# VNA.net
KiCad netlist of a schematic drawn in EAGLE
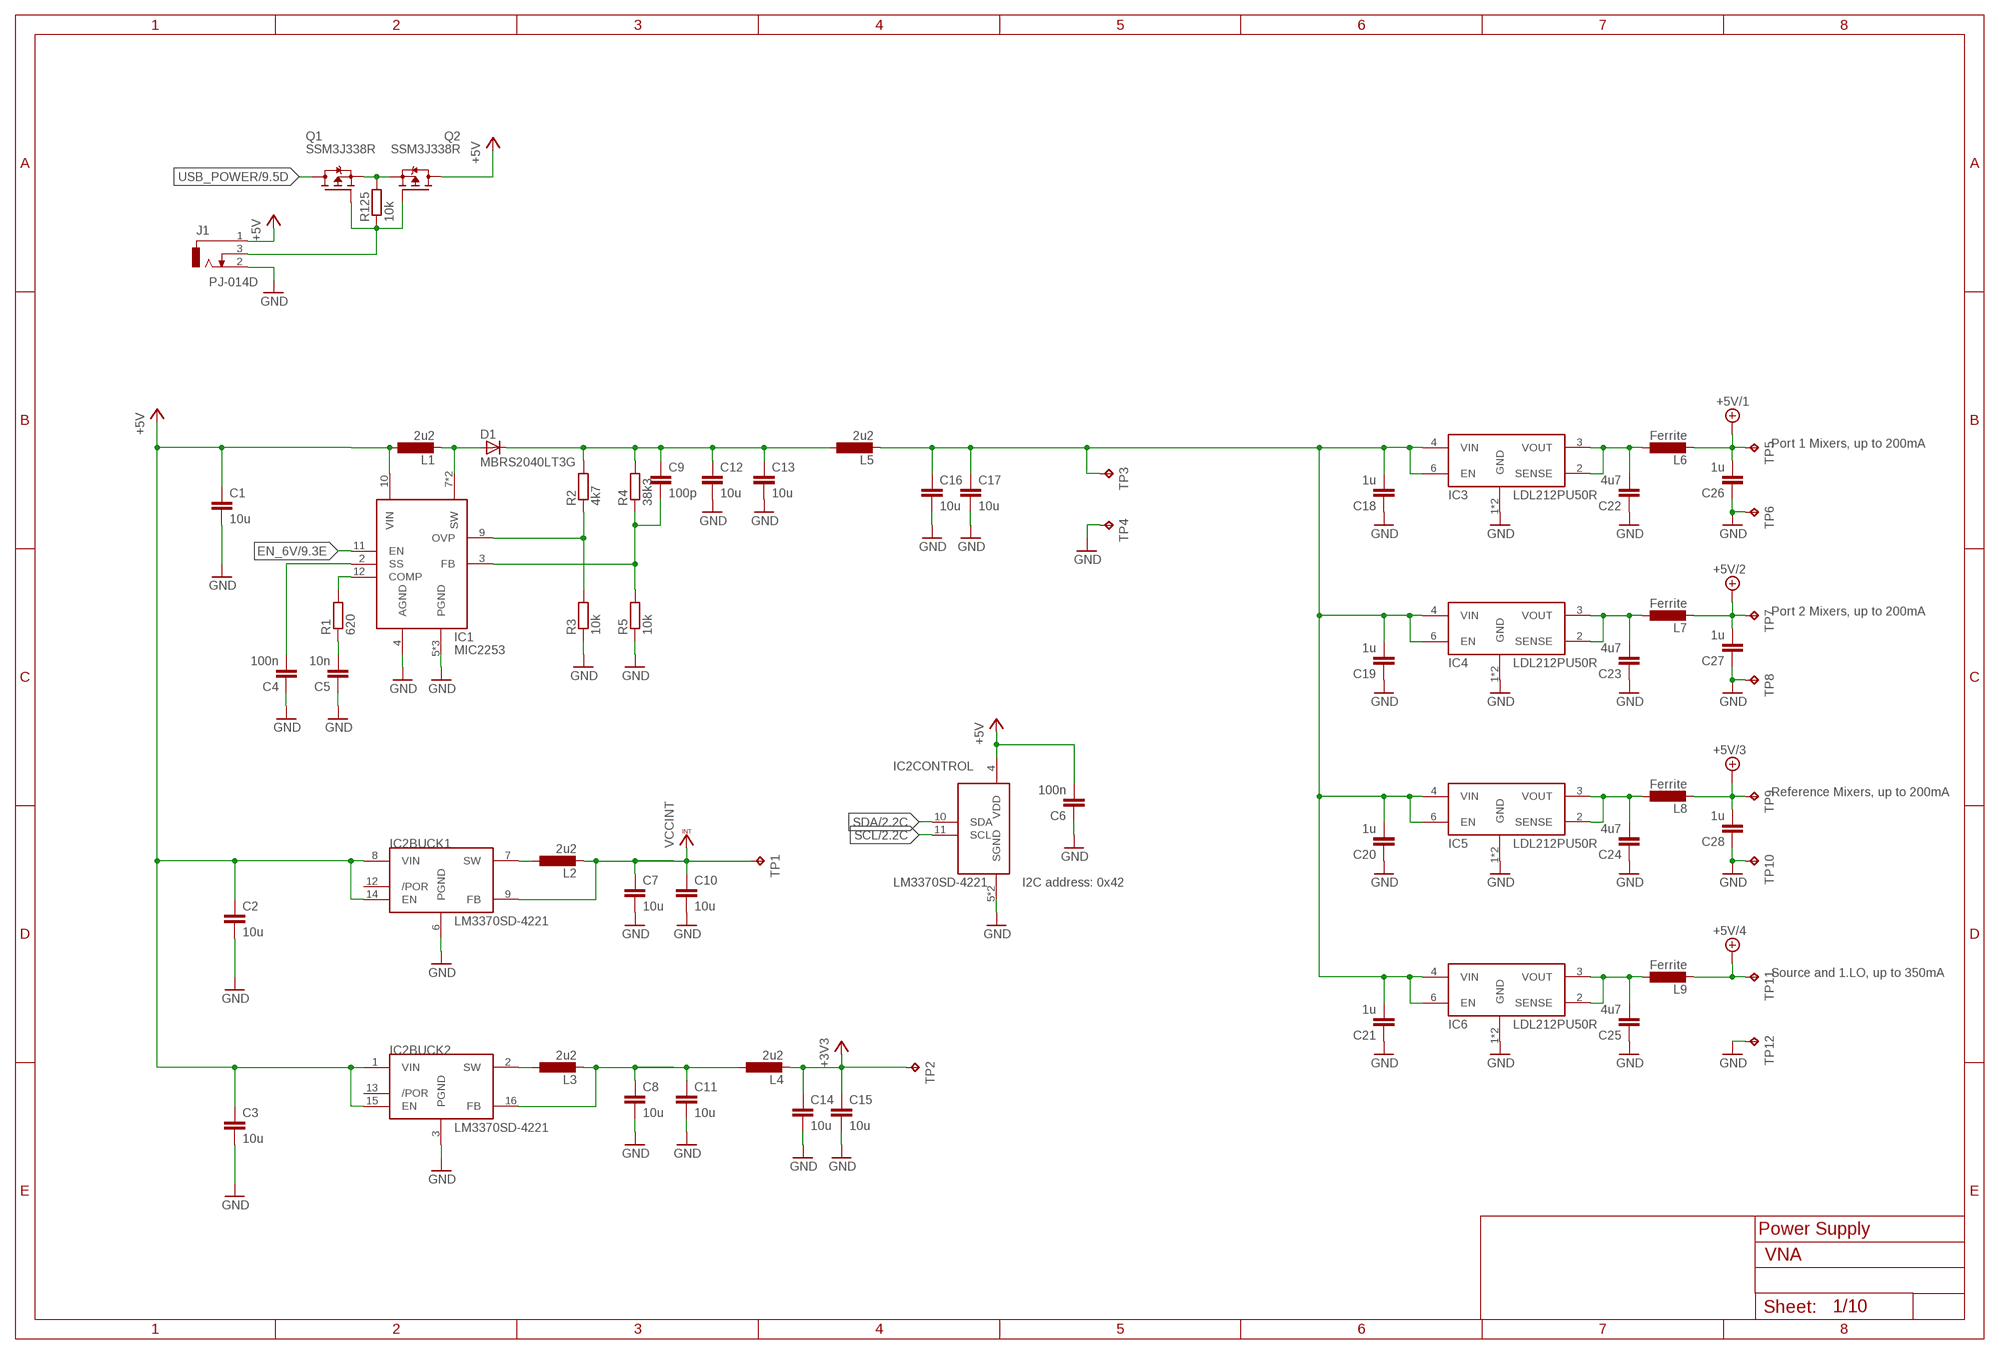
[diagram p0: schematic, sheet 1]
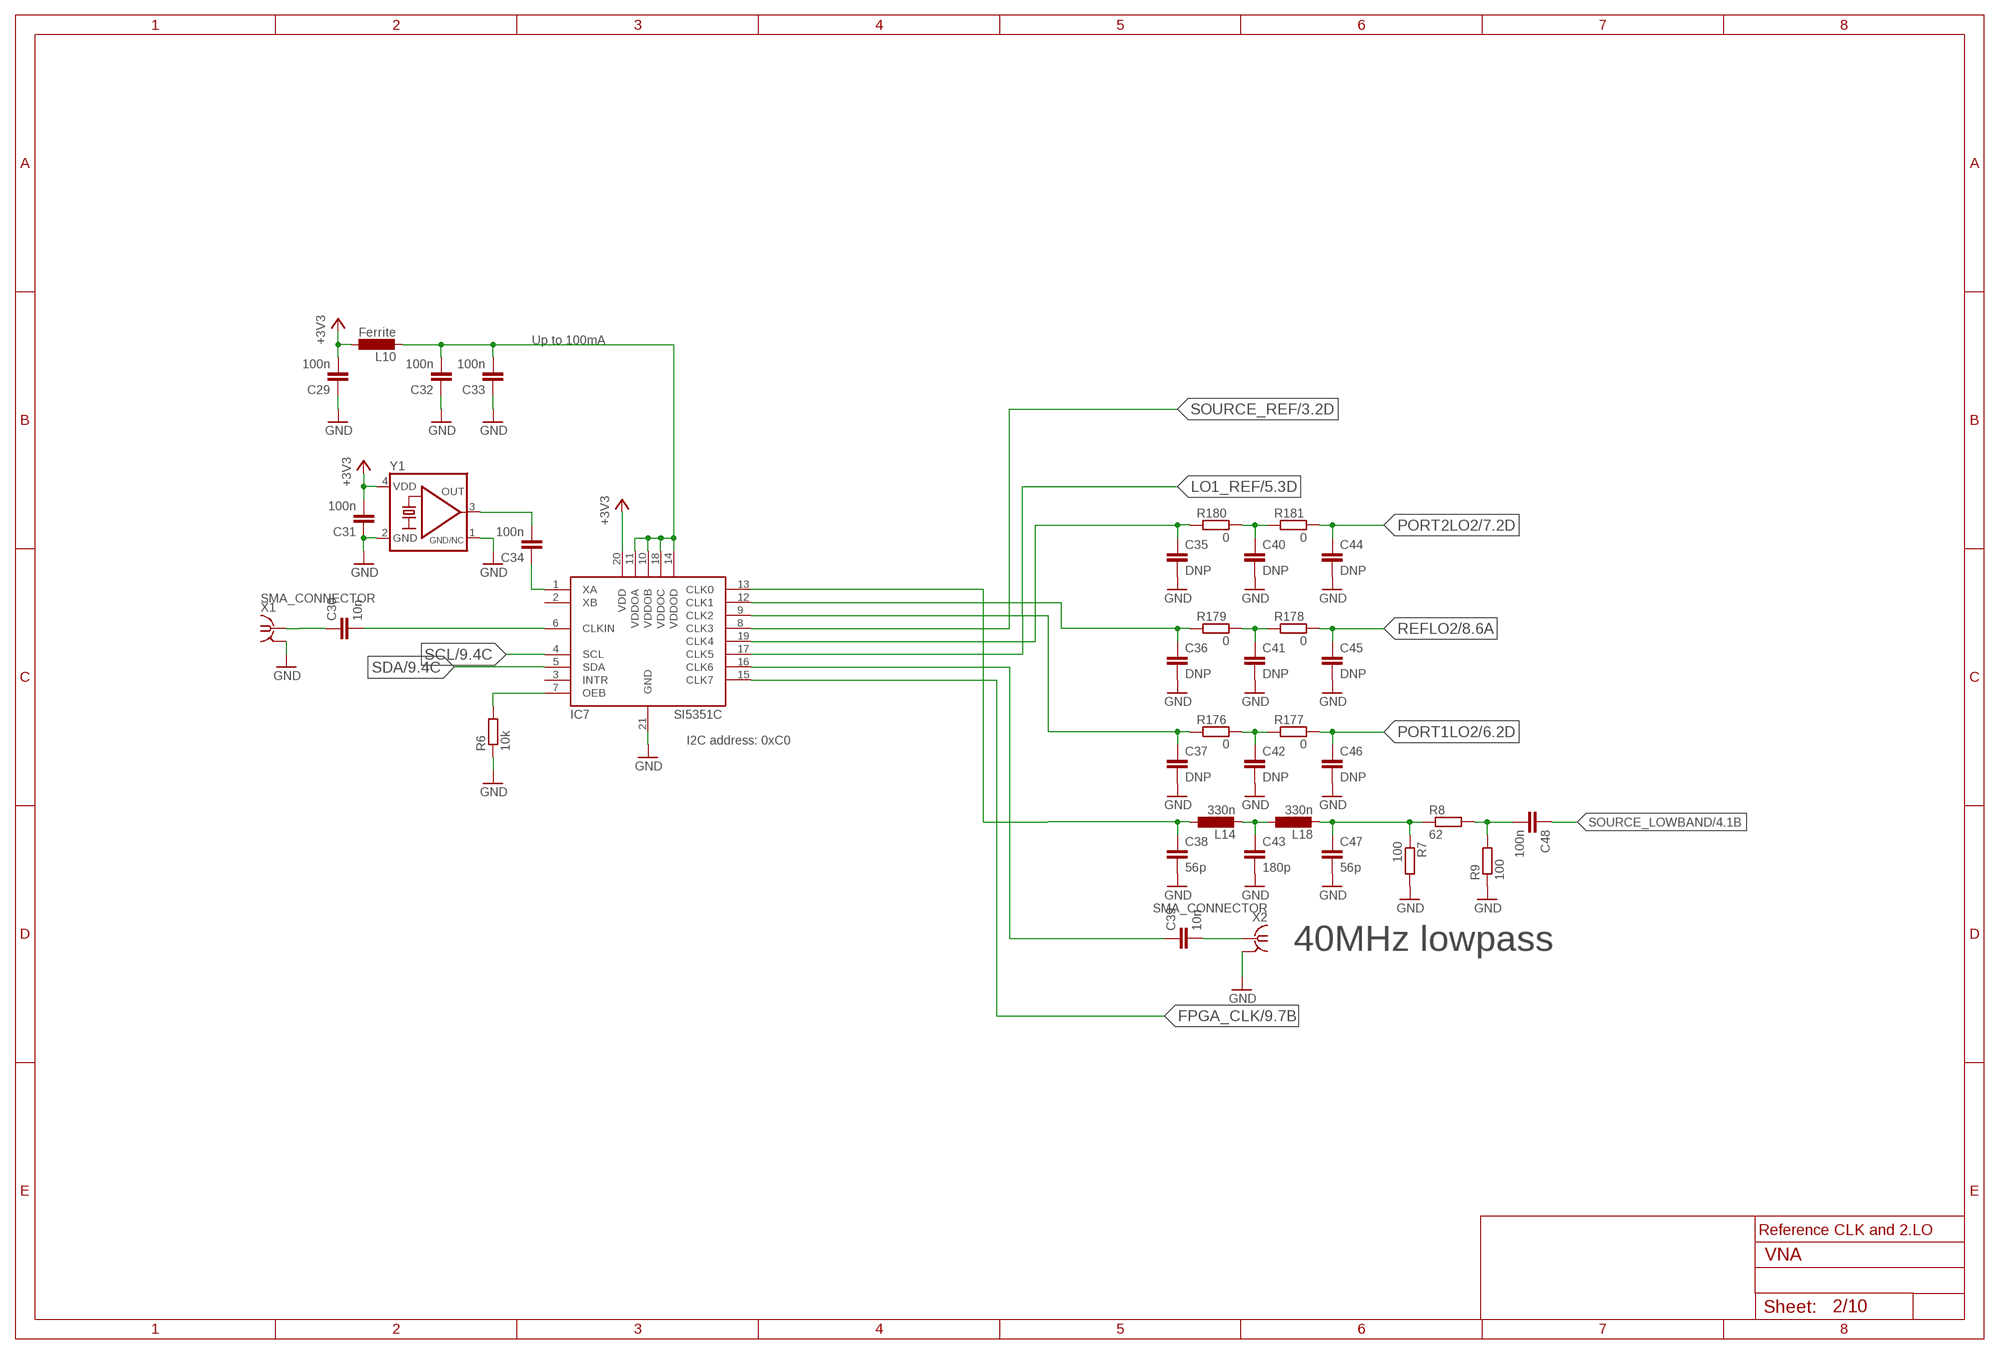
[diagram p1: schematic, sheet 2]
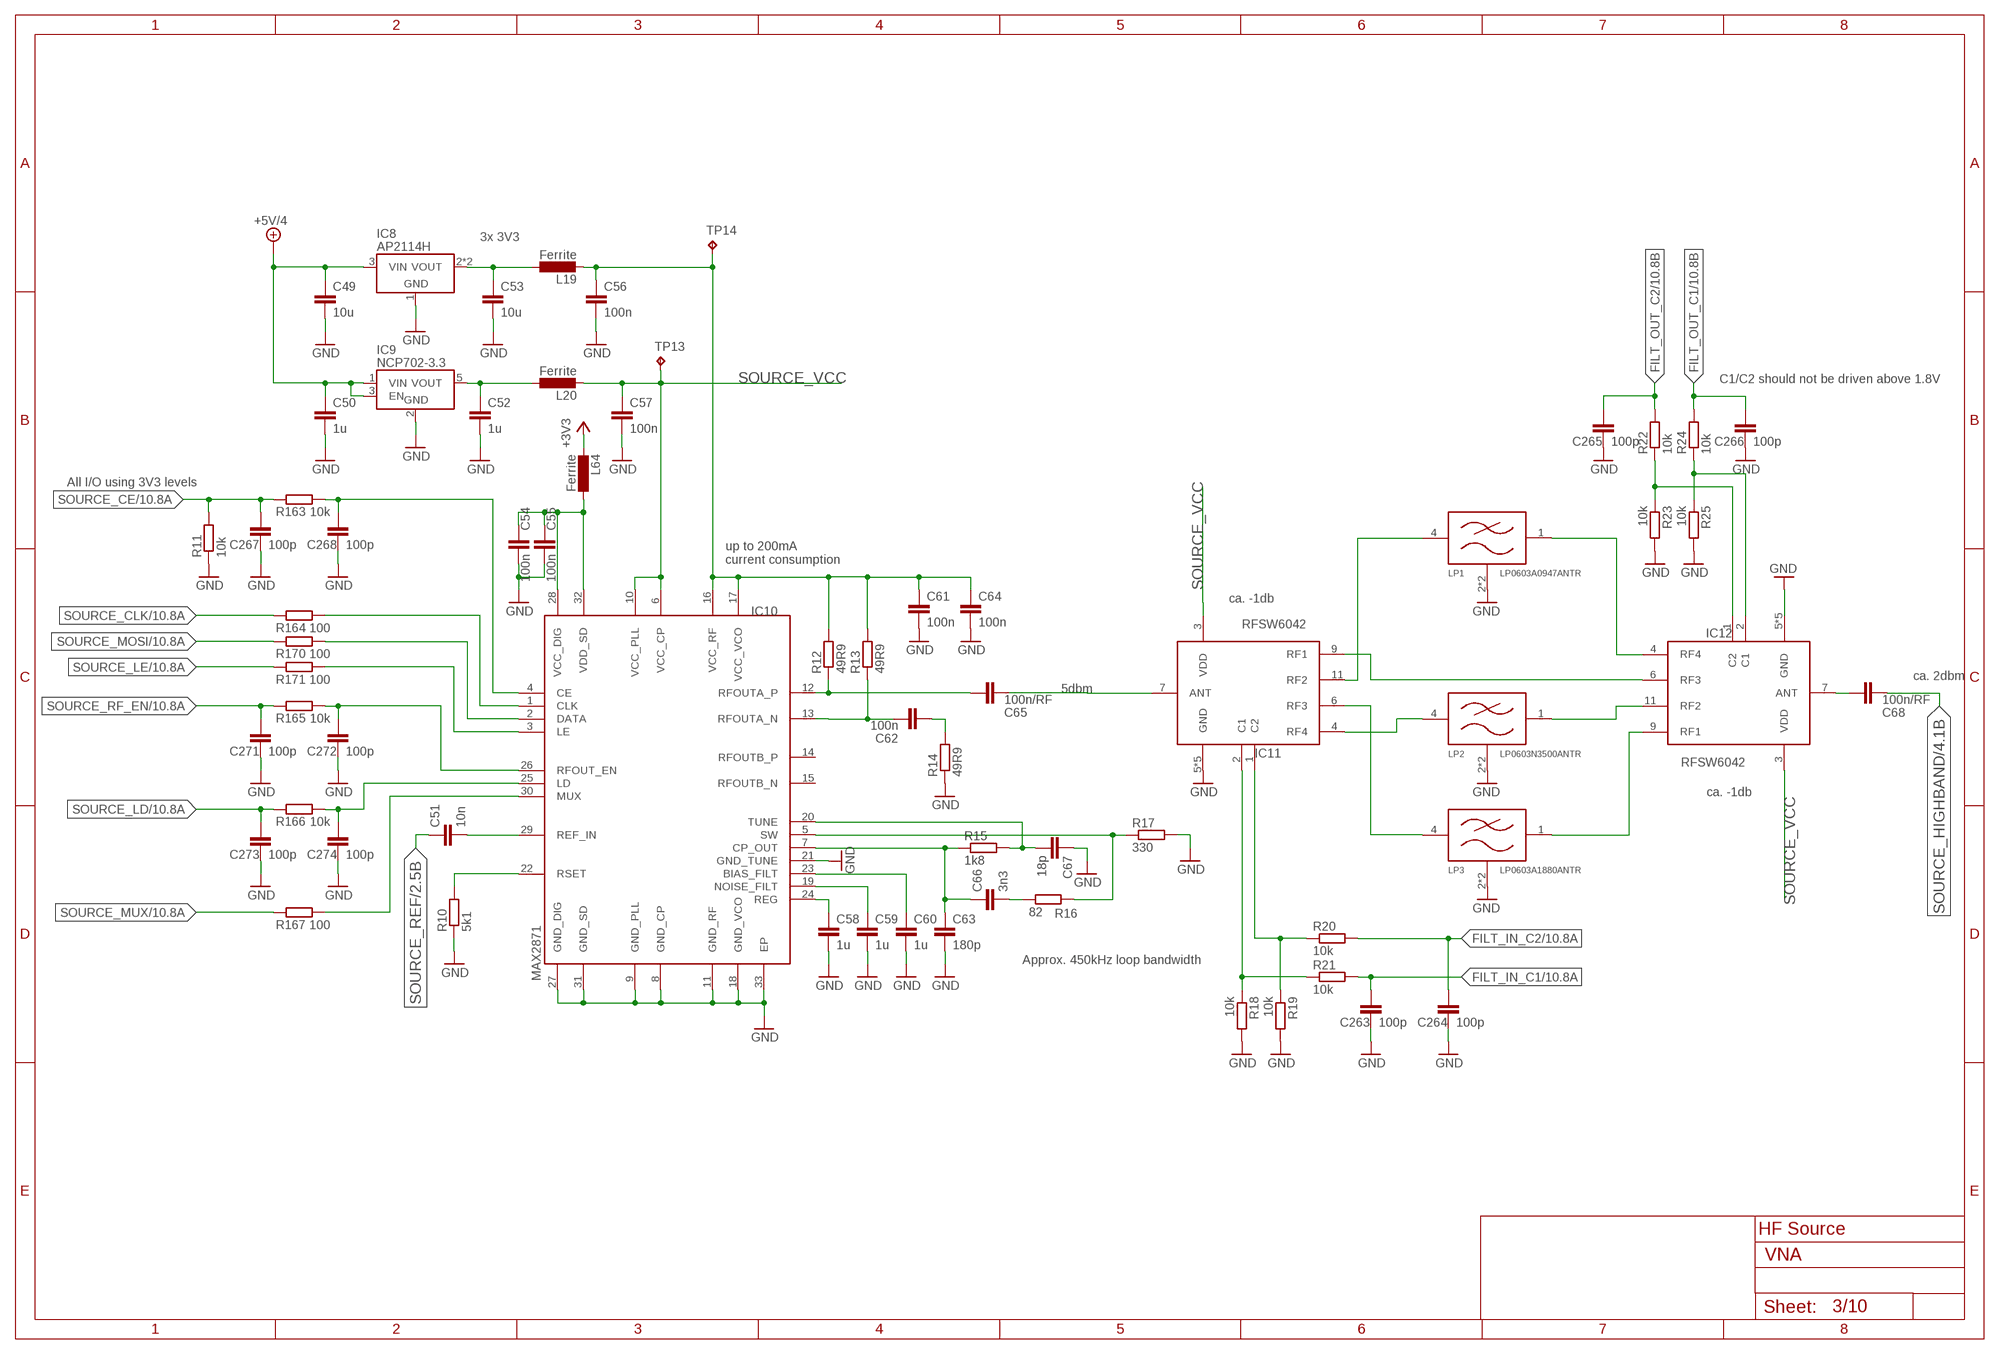
[diagram p2: schematic, sheet 3]
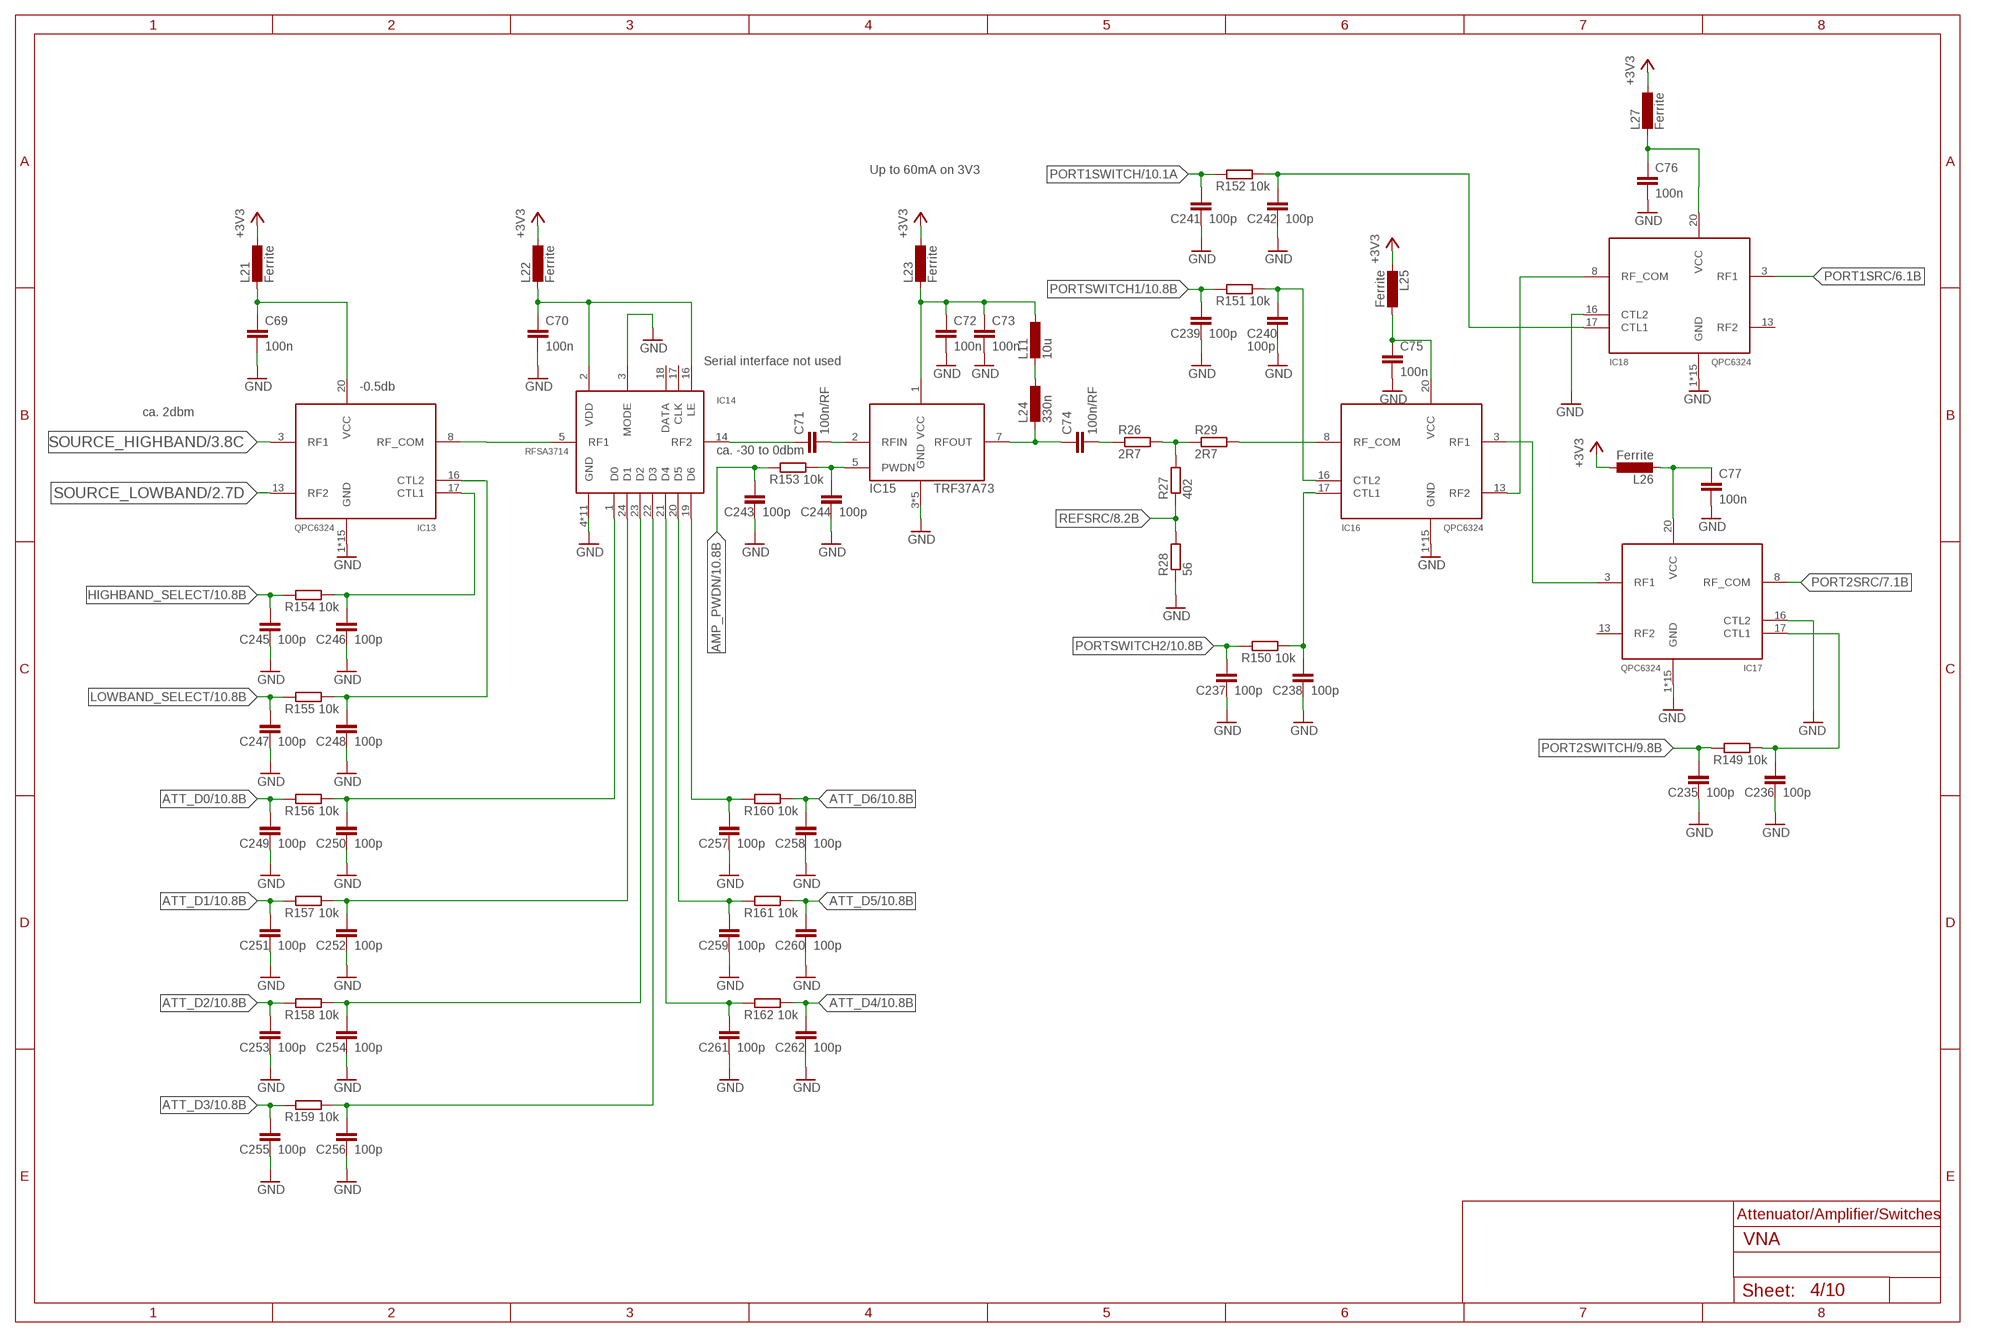
[diagram p3: schematic, sheet 4]
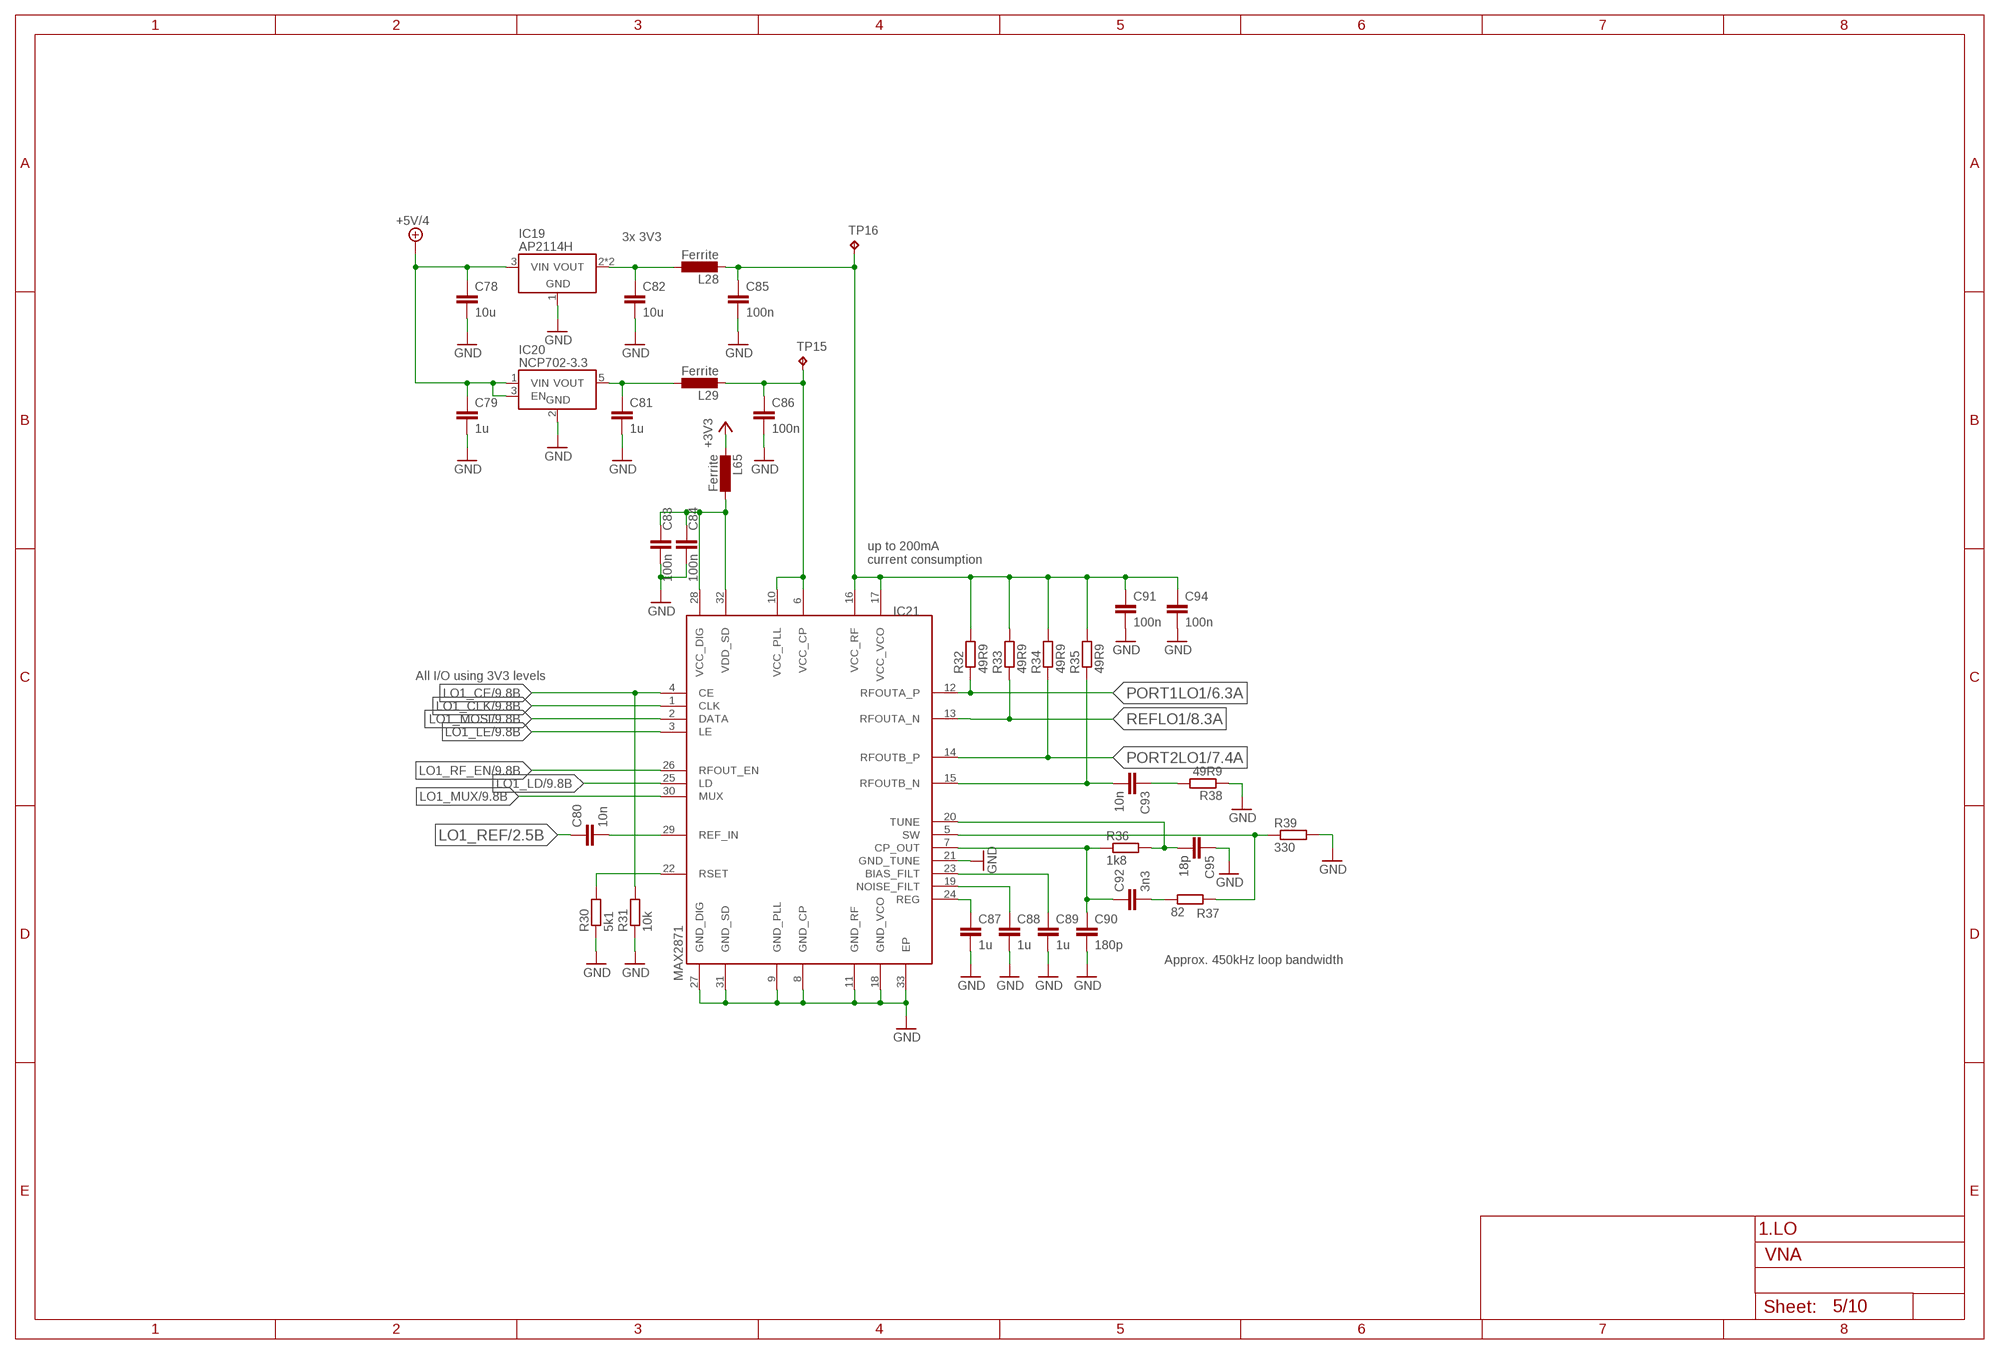
[diagram p4: schematic, sheet 5]
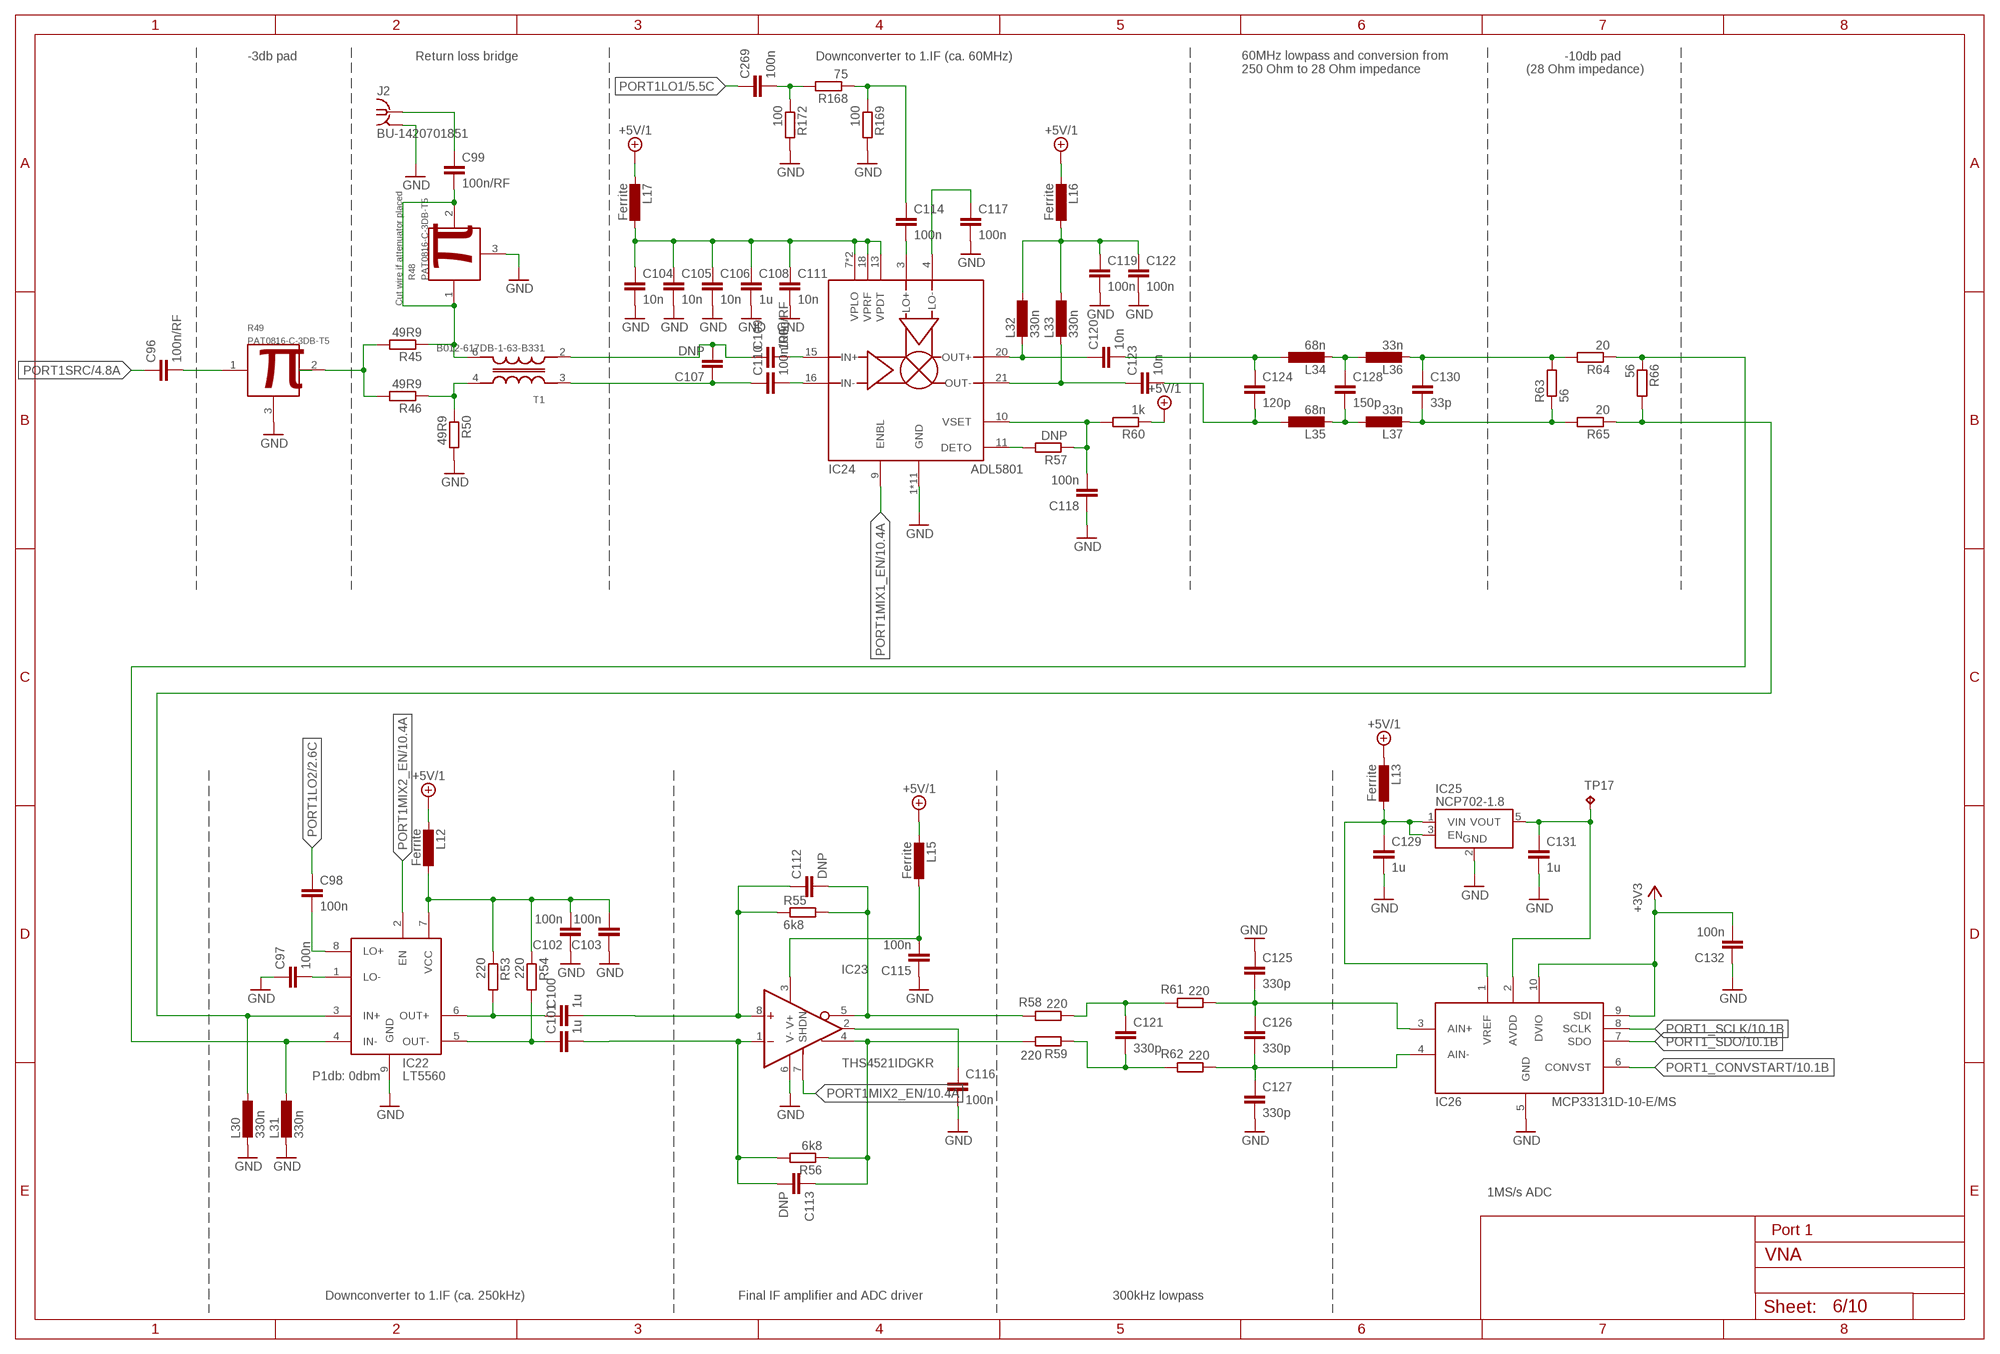
[diagram p5: schematic, sheet 6]
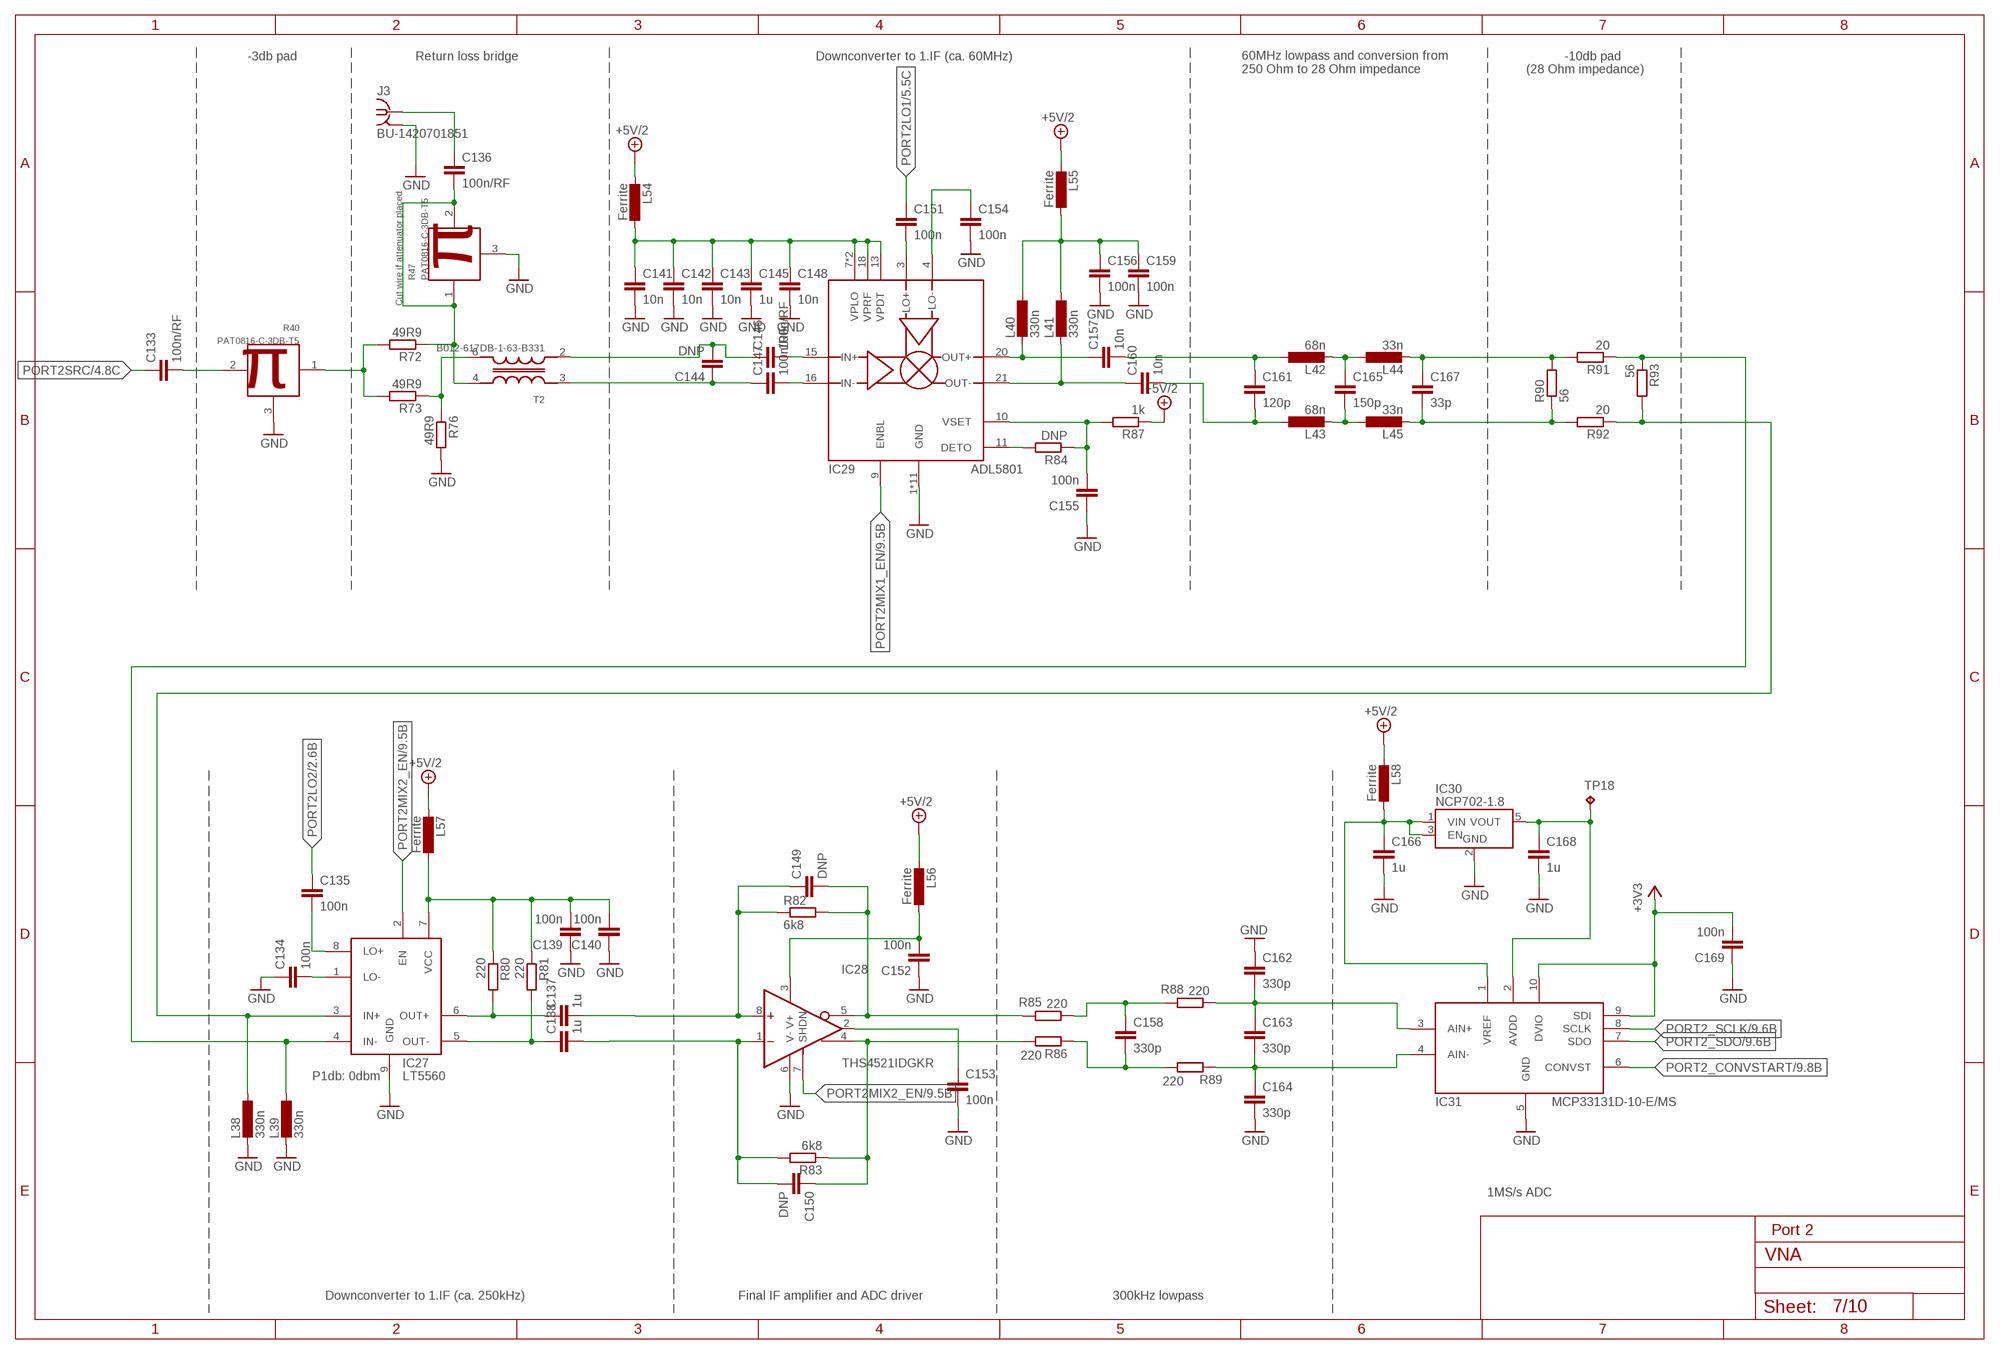
[diagram p6: schematic, sheet 7]
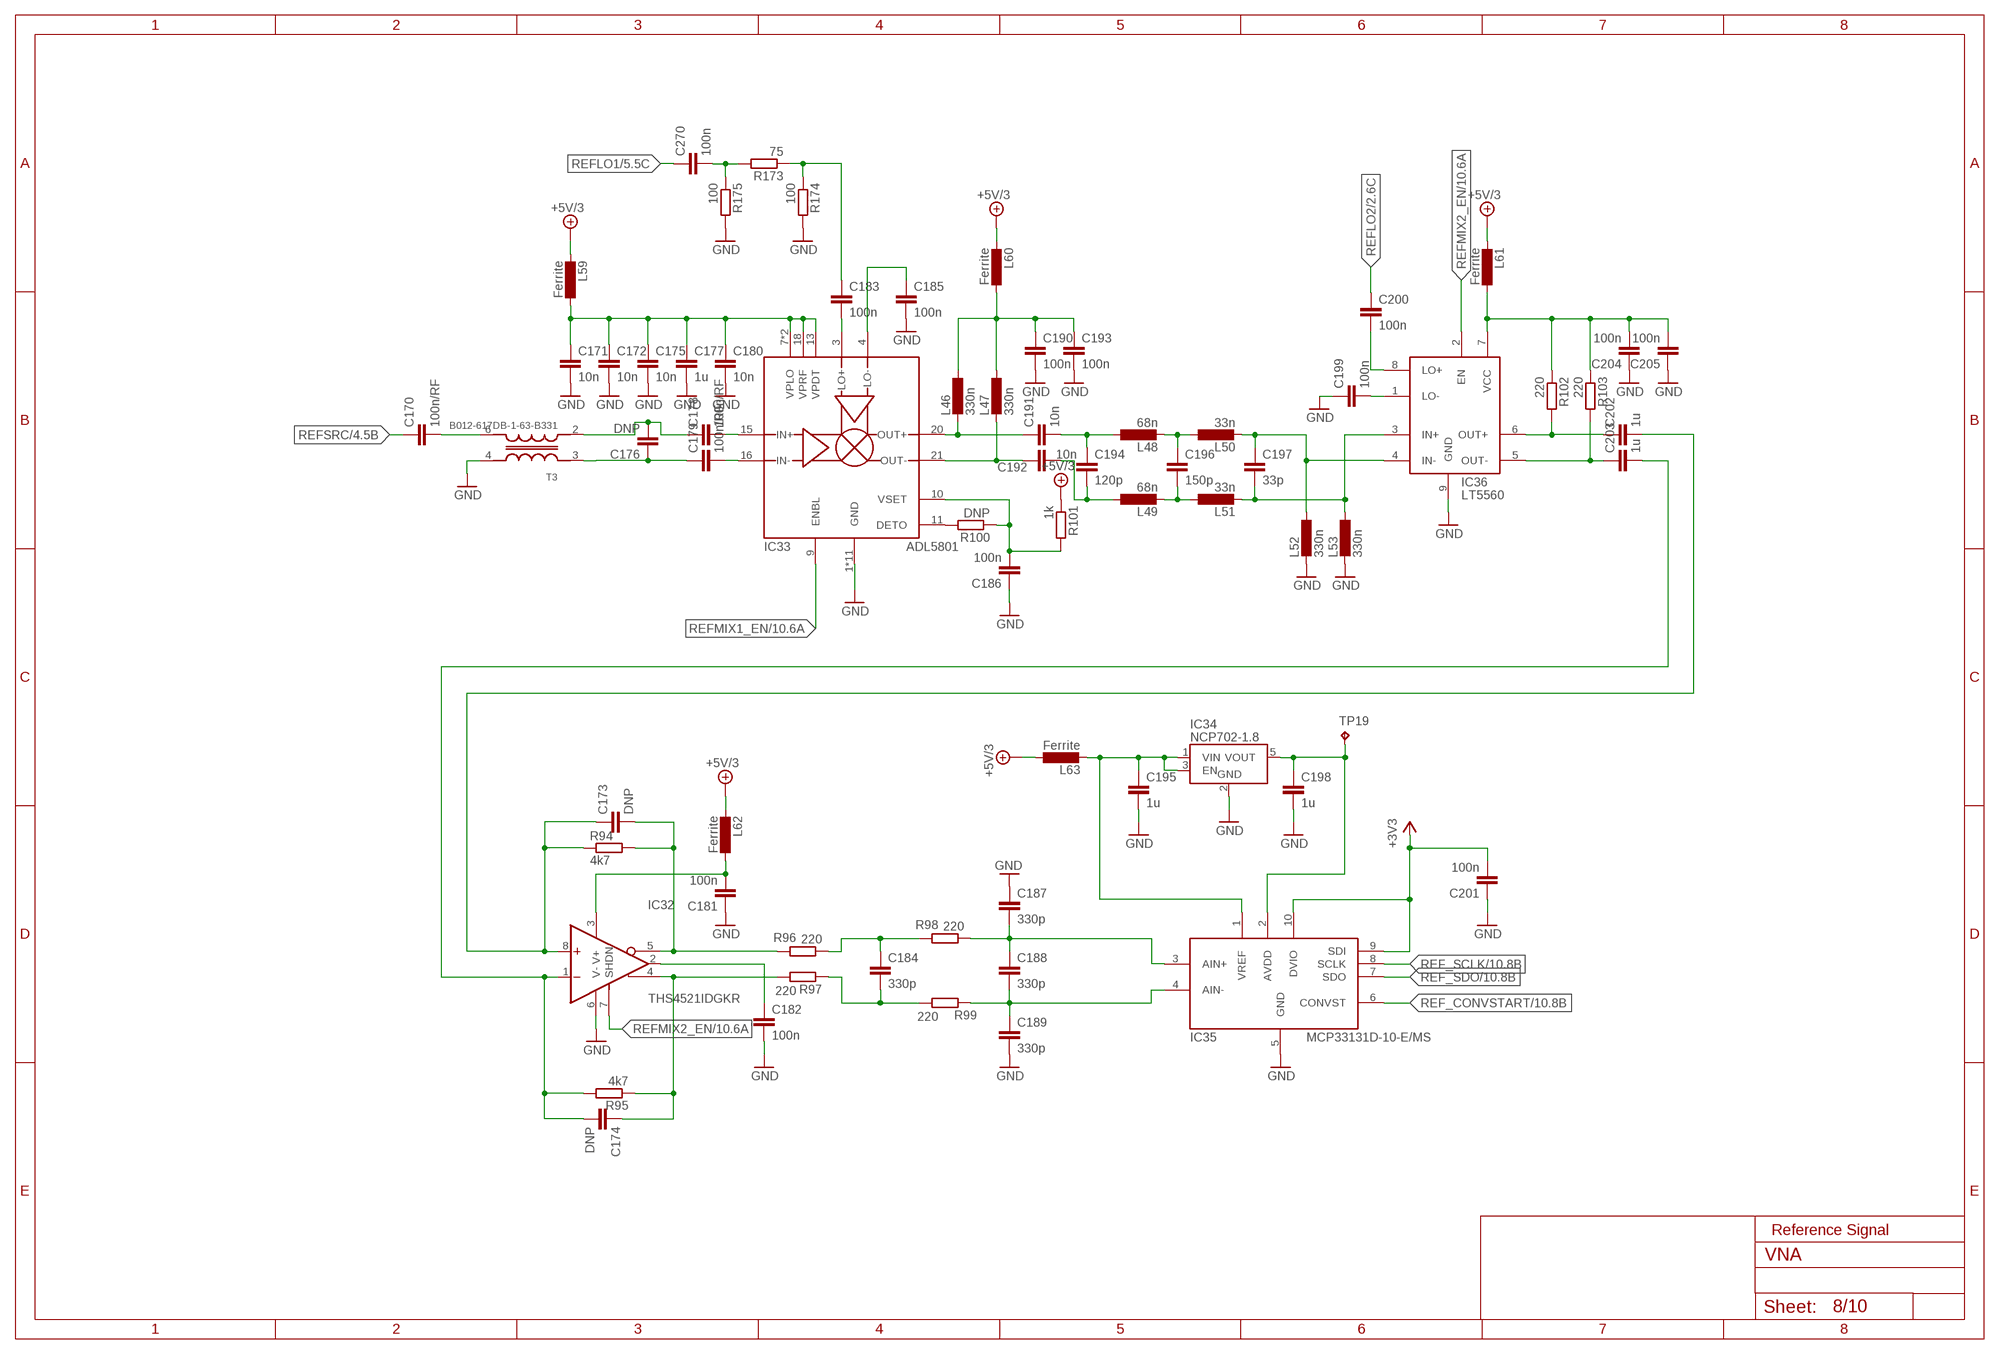
[diagram p7: schematic, sheet 8]
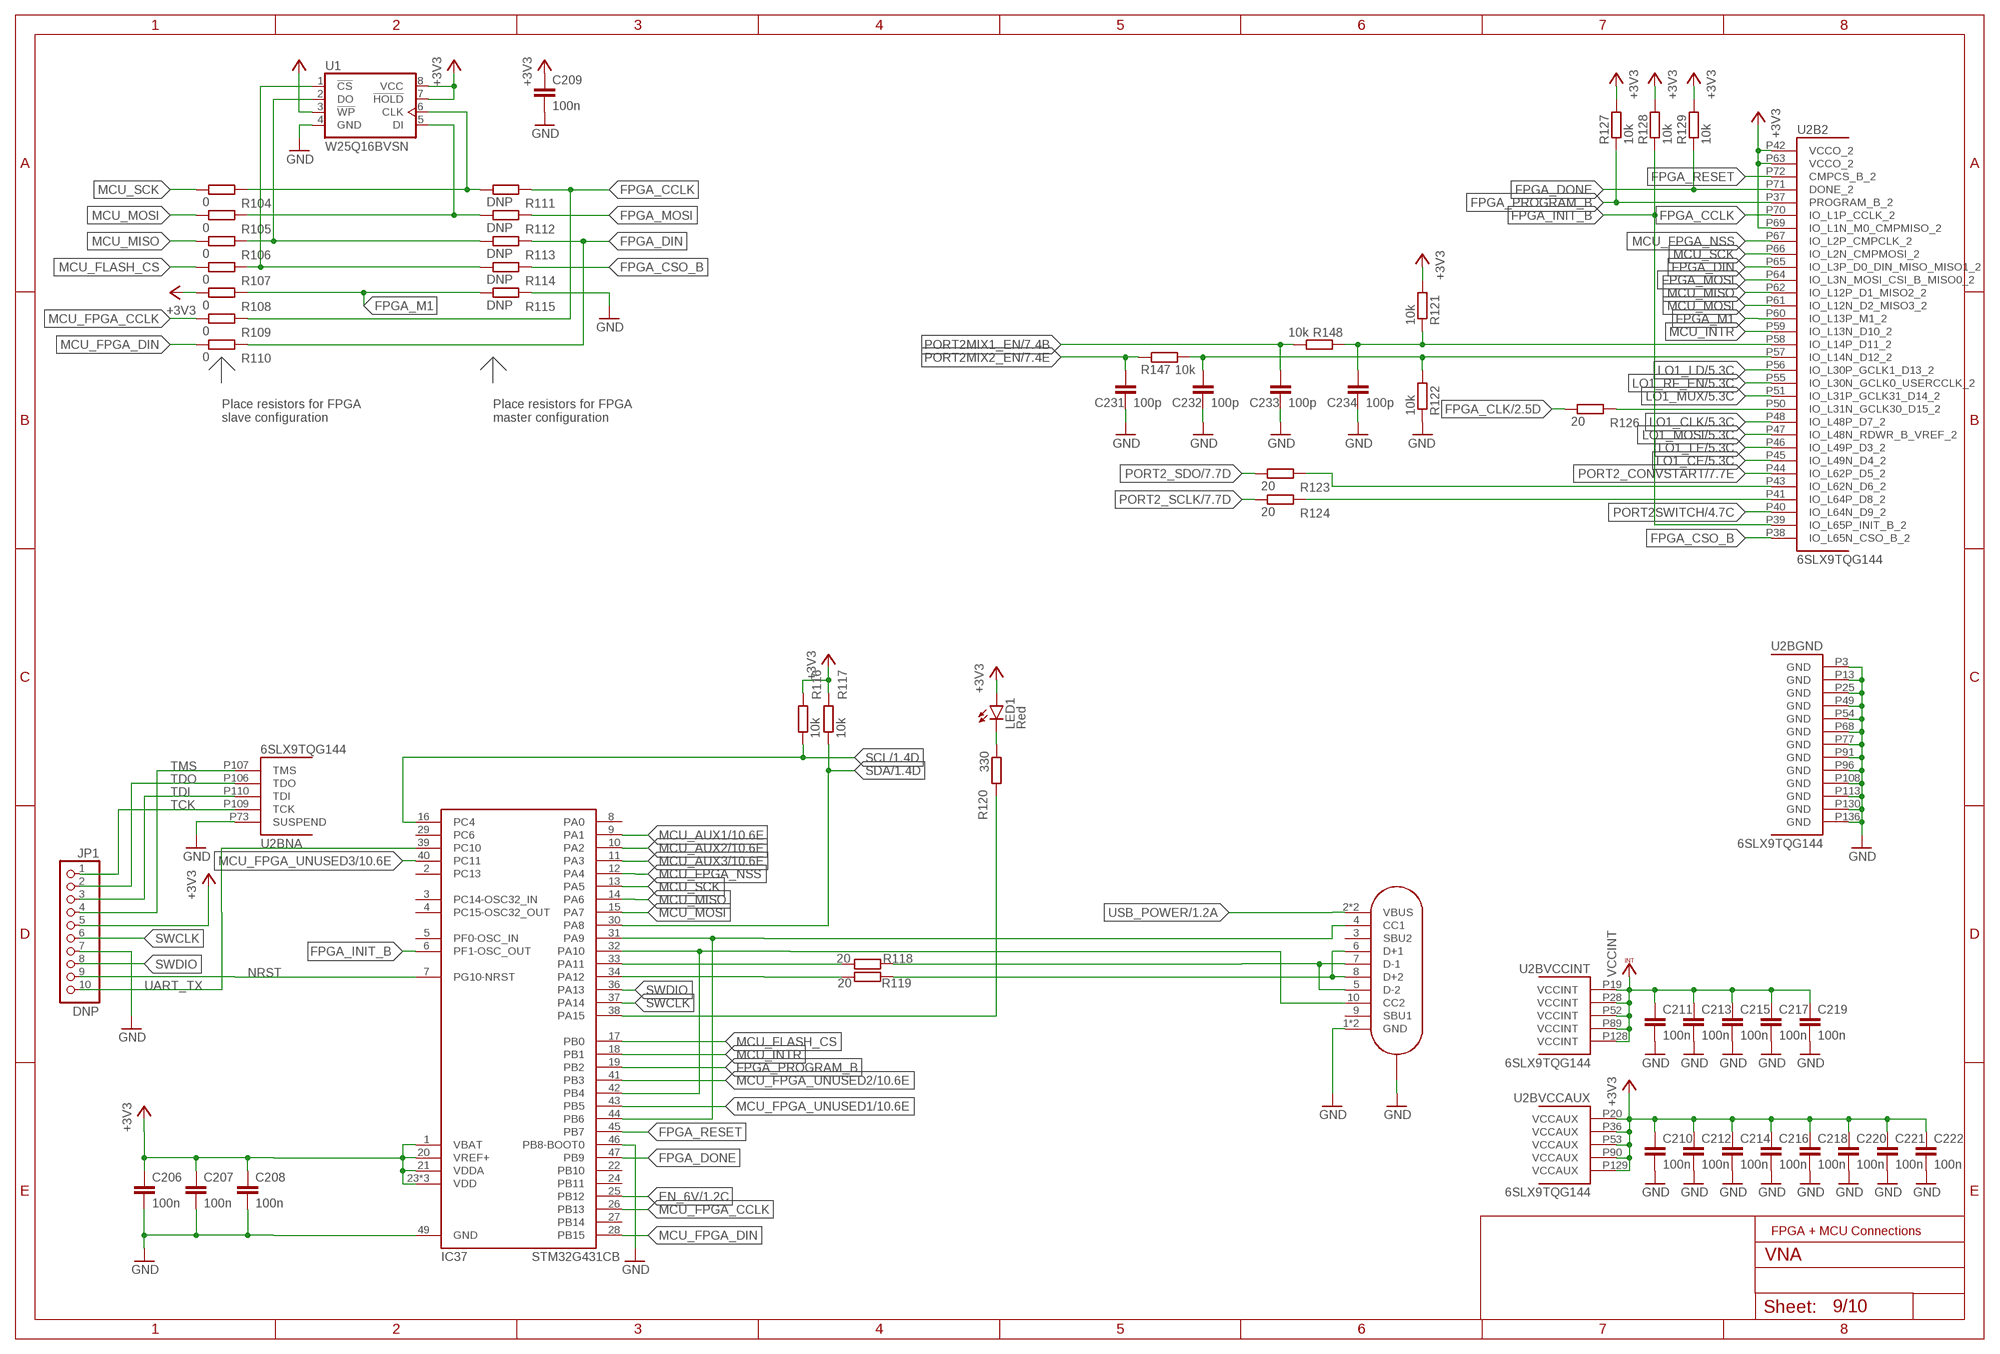
[diagram p8: schematic, sheet 9]
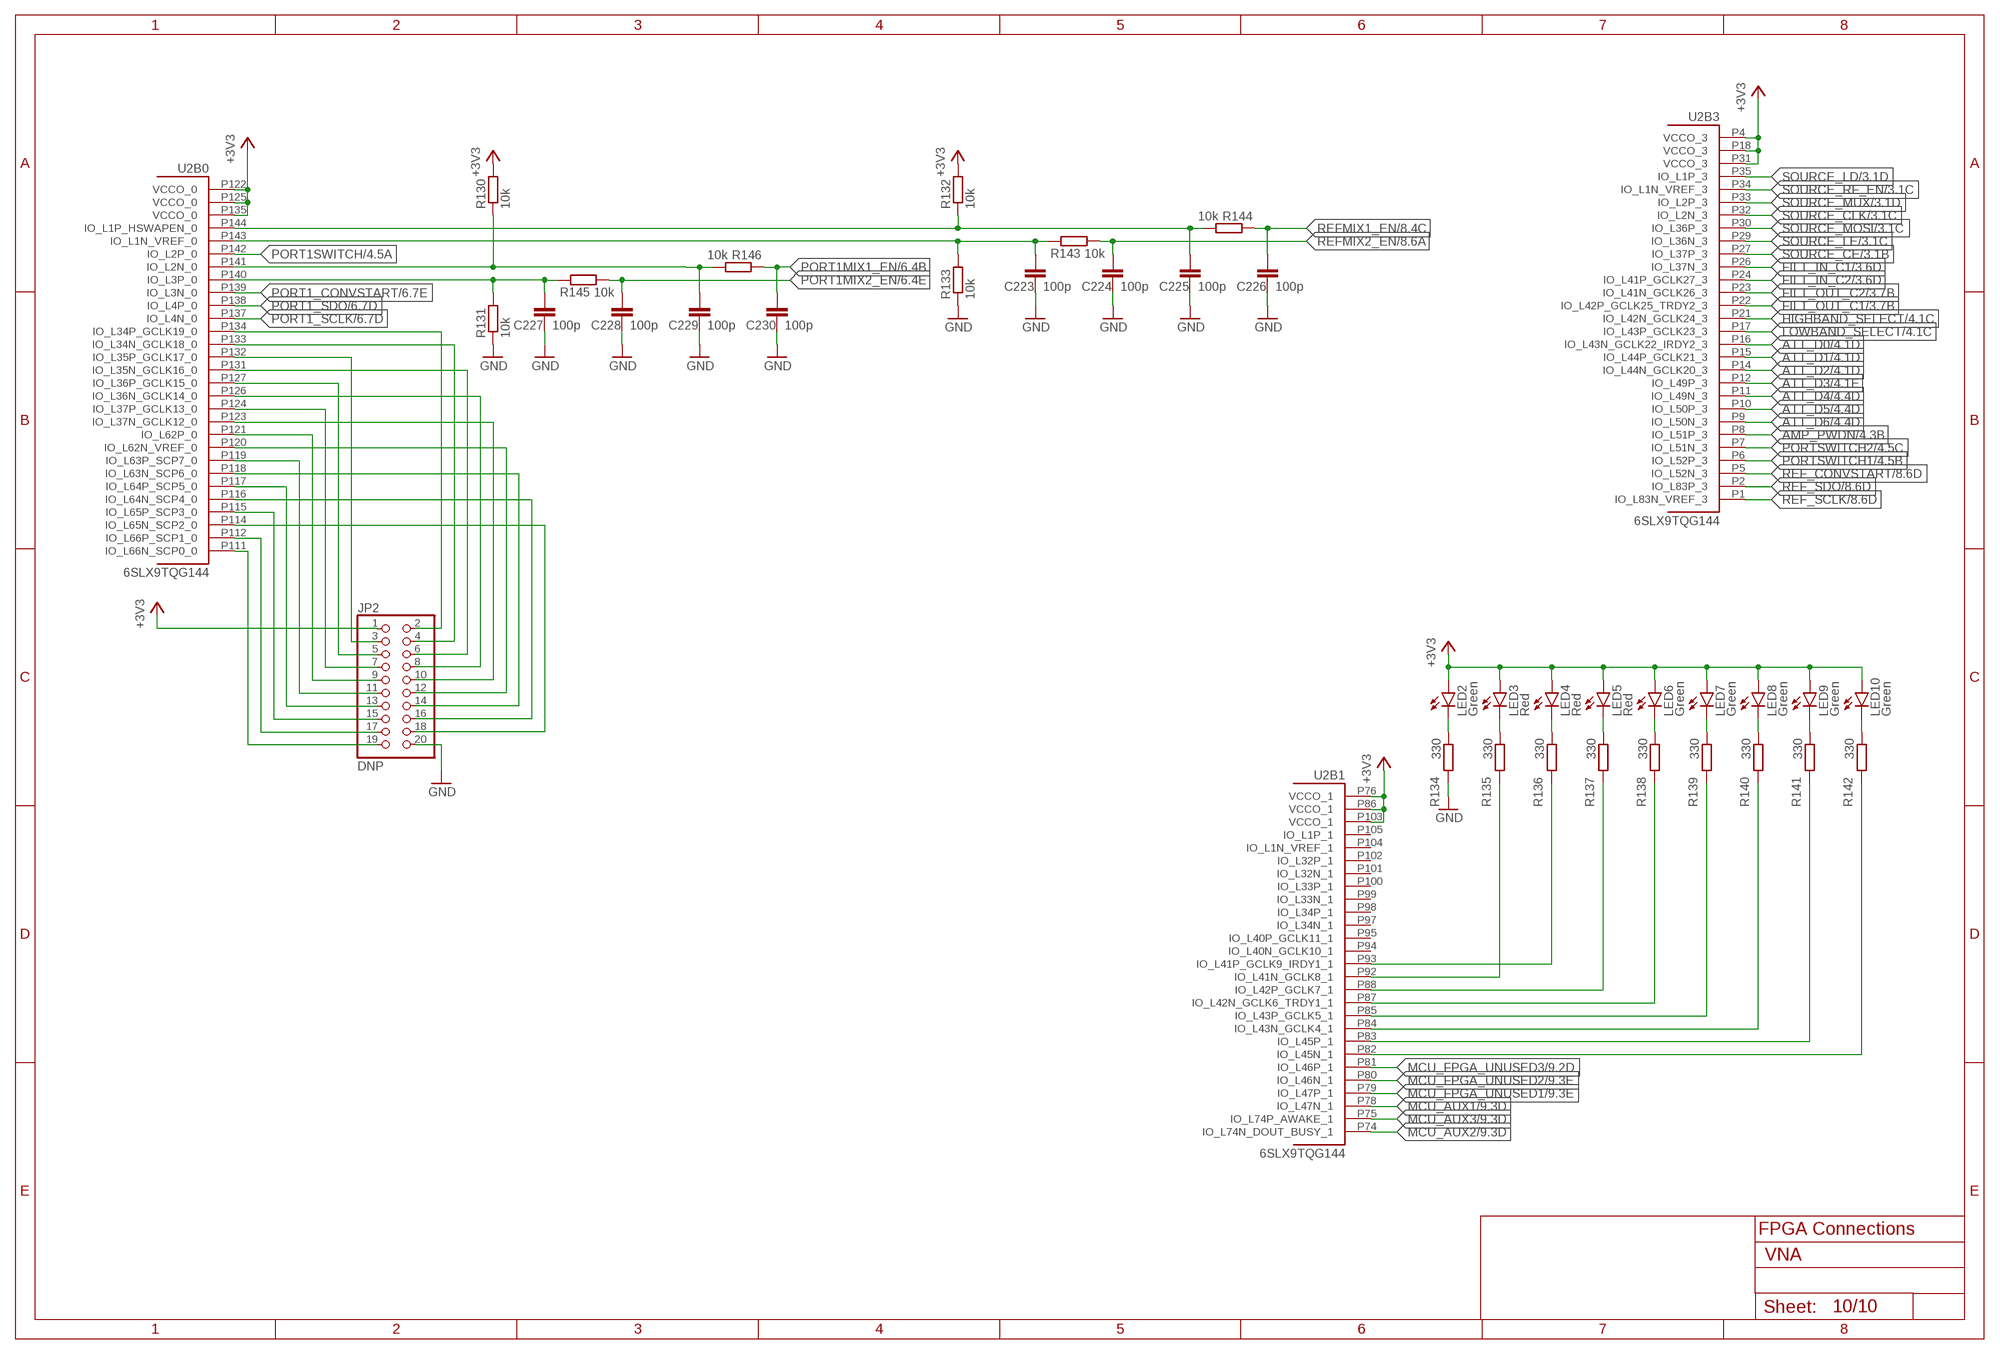
[diagram p9: schematic, sheet 10]

(export (version "E")
  (design (tool "Eeschema 10.0.6"))
  (components
    (comp (ref "C223")
      (value "100p")
      (footprint "eagle-import:C0402")
      (libsource (lib "eagle-import") (part "C-EU?{colon}2C0402"))
    )
    (comp (ref "C224")
      (value "100p")
      (footprint "eagle-import:C0402")
      (libsource (lib "eagle-import") (part "C-EU?{colon}2C0402"))
    )
    (comp (ref "C225")
      (value "100p")
      (footprint "eagle-import:C0402")
      (libsource (lib "eagle-import") (part "C-EU?{colon}2C0402"))
    )
    (comp (ref "C226")
      (value "100p")
      (footprint "eagle-import:C0402")
      (libsource (lib "eagle-import") (part "C-EU?{colon}2C0402"))
    )
    (comp (ref "C227")
      (value "100p")
      (footprint "eagle-import:C0402")
      (libsource (lib "eagle-import") (part "C-EU?{colon}2C0402"))
    )
    (comp (ref "C228")
      (value "100p")
      (footprint "eagle-import:C0402")
      (libsource (lib "eagle-import") (part "C-EU?{colon}2C0402"))
    )
    (comp (ref "C229")
      (value "100p")
      (footprint "eagle-import:C0402")
      (libsource (lib "eagle-import") (part "C-EU?{colon}2C0402"))
    )
    (comp (ref "C230")
      (value "100p")
      (footprint "eagle-import:C0402")
      (libsource (lib "eagle-import") (part "C-EU?{colon}2C0402"))
    )
    (comp (ref "JP2")
      (value "DNP")
      (footprint "eagle-import:2X10")
      (libsource (lib "eagle-import") (part "PINHD-2X10"))
    )
    (comp (ref "LED2")
      (value "Green")
      (footprint "eagle-import:CHIPLED_0603")
      (libsource (lib "eagle-import") (part "LEDCHIPLED_0603"))
    )
    (comp (ref "LED3")
      (value "Red")
      (footprint "eagle-import:CHIPLED_0603")
      (libsource (lib "eagle-import") (part "LEDCHIPLED_0603"))
    )
    (comp (ref "LED4")
      (value "Red")
      (footprint "eagle-import:CHIPLED_0603")
      (libsource (lib "eagle-import") (part "LEDCHIPLED_0603"))
    )
    (comp (ref "LED5")
      (value "Red")
      (footprint "eagle-import:CHIPLED_0603")
      (libsource (lib "eagle-import") (part "LEDCHIPLED_0603"))
    )
    (comp (ref "LED6")
      (value "Green")
      (footprint "eagle-import:CHIPLED_0603")
      (libsource (lib "eagle-import") (part "LEDCHIPLED_0603"))
    )
    (comp (ref "LED7")
      (value "Green")
      (footprint "eagle-import:CHIPLED_0603")
      (libsource (lib "eagle-import") (part "LEDCHIPLED_0603"))
    )
    (comp (ref "LED8")
      (value "Green")
      (footprint "eagle-import:CHIPLED_0603")
      (libsource (lib "eagle-import") (part "LEDCHIPLED_0603"))
    )
    (comp (ref "LED9")
      (value "Green")
      (footprint "eagle-import:CHIPLED_0603")
      (libsource (lib "eagle-import") (part "LEDCHIPLED_0603"))
    )
    (comp (ref "LED10")
      (value "Green")
      (footprint "eagle-import:CHIPLED_0603")
      (libsource (lib "eagle-import") (part "LEDCHIPLED_0603"))
    )
    (comp (ref "R130")
      (value "10k")
      (footprint "eagle-import:R0402")
      (libsource (lib "eagle-import") (part "R-EU_R0402"))
    )
    (comp (ref "R131")
      (value "10k")
      (footprint "eagle-import:R0402")
      (libsource (lib "eagle-import") (part "R-EU_R0402"))
    )
    (comp (ref "R132")
      (value "10k")
      (footprint "eagle-import:R0402")
      (libsource (lib "eagle-import") (part "R-EU_R0402"))
    )
    (comp (ref "R133")
      (value "10k")
      (footprint "eagle-import:R0402")
      (libsource (lib "eagle-import") (part "R-EU_R0402"))
    )
    (comp (ref "R134")
      (value "330")
      (footprint "eagle-import:R0402")
      (libsource (lib "eagle-import") (part "R-EU_R0402"))
    )
    (comp (ref "R135")
      (value "330")
      (footprint "eagle-import:R0402")
      (libsource (lib "eagle-import") (part "R-EU_R0402"))
    )
    (comp (ref "R136")
      (value "330")
      (footprint "eagle-import:R0402")
      (libsource (lib "eagle-import") (part "R-EU_R0402"))
    )
    (comp (ref "R137")
      (value "330")
      (footprint "eagle-import:R0402")
      (libsource (lib "eagle-import") (part "R-EU_R0402"))
    )
    (comp (ref "R138")
      (value "330")
      (footprint "eagle-import:R0402")
      (libsource (lib "eagle-import") (part "R-EU_R0402"))
    )
    (comp (ref "R139")
      (value "330")
      (footprint "eagle-import:R0402")
      (libsource (lib "eagle-import") (part "R-EU_R0402"))
    )
    (comp (ref "R140")
      (value "330")
      (footprint "eagle-import:R0402")
      (libsource (lib "eagle-import") (part "R-EU_R0402"))
    )
    (comp (ref "R141")
      (value "330")
      (footprint "eagle-import:R0402")
      (libsource (lib "eagle-import") (part "R-EU_R0402"))
    )
    (comp (ref "R142")
      (value "330")
      (footprint "eagle-import:R0402")
      (libsource (lib "eagle-import") (part "R-EU_R0402"))
    )
    (comp (ref "R143")
      (value "10k")
      (footprint "eagle-import:R0402")
      (libsource (lib "eagle-import") (part "R-EU_R0402"))
    )
    (comp (ref "R144")
      (value "10k")
      (footprint "eagle-import:R0402")
      (libsource (lib "eagle-import") (part "R-EU_R0402"))
    )
    (comp (ref "R145")
      (value "10k")
      (footprint "eagle-import:R0402")
      (libsource (lib "eagle-import") (part "R-EU_R0402"))
    )
    (comp (ref "R146")
      (value "10k")
      (footprint "eagle-import:R0402")
      (libsource (lib "eagle-import") (part "R-EU_R0402"))
    )
    (comp (ref "U2")
      (value "6SLX9TQG144")
      (footprint "eagle-import:TQ144")
      (libsource (lib "eagle-import") (part "6SLX9TQG144"))
    )
    (comp (ref "C170")
      (value "100n/RF")
      (footprint "eagle-import:C0402")
      (libsource (lib "eagle-import") (part "C-EU?{colon}2C0402"))
    )
    (comp (ref "C171")
      (value "10n")
      (footprint "eagle-import:C0402")
      (libsource (lib "eagle-import") (part "C-EU?{colon}2C0402"))
    )
    (comp (ref "C172")
      (value "10n")
      (footprint "eagle-import:C0402")
      (libsource (lib "eagle-import") (part "C-EU?{colon}2C0402"))
    )
    (comp (ref "C173")
      (value "DNP")
      (footprint "eagle-import:C0402")
      (libsource (lib "eagle-import") (part "C-EU?{colon}2C0402"))
    )
    (comp (ref "C174")
      (value "DNP")
      (footprint "eagle-import:C0402")
      (libsource (lib "eagle-import") (part "C-EU?{colon}2C0402"))
    )
    (comp (ref "C175")
      (value "10n")
      (footprint "eagle-import:C0402")
      (libsource (lib "eagle-import") (part "C-EU?{colon}2C0402"))
    )
    (comp (ref "C176")
      (value "DNP")
      (footprint "eagle-import:C0402")
      (libsource (lib "eagle-import") (part "C-EU?{colon}2C0402"))
    )
    (comp (ref "C177")
      (value "1u")
      (footprint "eagle-import:C0402")
      (libsource (lib "eagle-import") (part "C-EU?{colon}2C0402"))
    )
    (comp (ref "C178")
      (value "100n/RF")
      (footprint "eagle-import:C0402")
      (libsource (lib "eagle-import") (part "C-EU?{colon}2C0402"))
    )
    (comp (ref "C179")
      (value "100n/RF")
      (footprint "eagle-import:C0402")
      (libsource (lib "eagle-import") (part "C-EU?{colon}2C0402"))
    )
    (comp (ref "C180")
      (value "10n")
      (footprint "eagle-import:C0402")
      (libsource (lib "eagle-import") (part "C-EU?{colon}2C0402"))
    )
    (comp (ref "C181")
      (value "100n")
      (footprint "eagle-import:C0402")
      (libsource (lib "eagle-import") (part "C-EU?{colon}2C0402"))
    )
    (comp (ref "C182")
      (value "100n")
      (footprint "eagle-import:C0402")
      (libsource (lib "eagle-import") (part "C-EU?{colon}2C0402"))
    )
    (comp (ref "C183")
      (value "100n")
      (footprint "eagle-import:C0402")
      (libsource (lib "eagle-import") (part "C-EU?{colon}2C0402"))
    )
    (comp (ref "C184")
      (value "330p")
      (footprint "eagle-import:C0402")
      (libsource (lib "eagle-import") (part "C-EU?{colon}2C0402"))
    )
    (comp (ref "C185")
      (value "100n")
      (footprint "eagle-import:C0402")
      (libsource (lib "eagle-import") (part "C-EU?{colon}2C0402"))
    )
    (comp (ref "C186")
      (value "100n")
      (footprint "eagle-import:C0402")
      (libsource (lib "eagle-import") (part "C-EU?{colon}2C0402"))
    )
    (comp (ref "C187")
      (value "330p")
      (footprint "eagle-import:C0402")
      (libsource (lib "eagle-import") (part "C-EU?{colon}2C0402"))
    )
    (comp (ref "C188")
      (value "330p")
      (footprint "eagle-import:C0402")
      (libsource (lib "eagle-import") (part "C-EU?{colon}2C0402"))
    )
    (comp (ref "C189")
      (value "330p")
      (footprint "eagle-import:C0402")
      (libsource (lib "eagle-import") (part "C-EU?{colon}2C0402"))
    )
    (comp (ref "C190")
      (value "100n")
      (footprint "eagle-import:C0402")
      (libsource (lib "eagle-import") (part "C-EU?{colon}2C0402"))
    )
    (comp (ref "C191")
      (value "10n")
      (footprint "eagle-import:C0402")
      (libsource (lib "eagle-import") (part "C-EU?{colon}2C0402"))
    )
    (comp (ref "C192")
      (value "10n")
      (footprint "eagle-import:C0402")
      (libsource (lib "eagle-import") (part "C-EU?{colon}2C0402"))
    )
    (comp (ref "C193")
      (value "100n")
      (footprint "eagle-import:C0402")
      (libsource (lib "eagle-import") (part "C-EU?{colon}2C0402"))
    )
    (comp (ref "C194")
      (value "120p")
      (footprint "eagle-import:C0402")
      (libsource (lib "eagle-import") (part "C-EU?{colon}2C0402"))
    )
    (comp (ref "C195")
      (value "1u")
      (footprint "eagle-import:C0402")
      (libsource (lib "eagle-import") (part "C-EU?{colon}2C0402"))
    )
    (comp (ref "C196")
      (value "150p")
      (footprint "eagle-import:C0402")
      (libsource (lib "eagle-import") (part "C-EU?{colon}2C0402"))
    )
    (comp (ref "C197")
      (value "33p")
      (footprint "eagle-import:C0402")
      (libsource (lib "eagle-import") (part "C-EU?{colon}2C0402"))
    )
    (comp (ref "C198")
      (value "1u")
      (footprint "eagle-import:C0402")
      (libsource (lib "eagle-import") (part "C-EU?{colon}2C0402"))
    )
    (comp (ref "C199")
      (value "100n")
      (footprint "eagle-import:C0402")
      (libsource (lib "eagle-import") (part "C-EU?{colon}2C0402"))
    )
    (comp (ref "C200")
      (value "100n")
      (footprint "eagle-import:C0402")
      (libsource (lib "eagle-import") (part "C-EU?{colon}2C0402"))
    )
    (comp (ref "C201")
      (value "100n")
      (footprint "eagle-import:C0402")
      (libsource (lib "eagle-import") (part "C-EU?{colon}2C0402"))
    )
    (comp (ref "C202")
      (value "1u")
      (footprint "eagle-import:C0402")
      (libsource (lib "eagle-import") (part "C-EU?{colon}2C0402"))
    )
    (comp (ref "C203")
      (value "1u")
      (footprint "eagle-import:C0402")
      (libsource (lib "eagle-import") (part "C-EU?{colon}2C0402"))
    )
    (comp (ref "C204")
      (value "100n")
      (footprint "eagle-import:C0402")
      (libsource (lib "eagle-import") (part "C-EU?{colon}2C0402"))
    )
    (comp (ref "C205")
      (value "100n")
      (footprint "eagle-import:C0402")
      (libsource (lib "eagle-import") (part "C-EU?{colon}2C0402"))
    )
    (comp (ref "C270")
      (value "100n")
      (footprint "eagle-import:C0402")
      (libsource (lib "eagle-import") (part "C-EU?{colon}2C0402"))
    )
    (comp (ref "IC32")
      (value "THS4521IDGKR")
      (footprint "eagle-import:SOP65P490X110-8N")
      (libsource (lib "eagle-import") (part "THS4521IDGKR"))
    )
    (comp (ref "IC33")
      (value "ADL5801")
      (footprint "eagle-import:QFN50P400X400X100-25T250N")
      (libsource (lib "eagle-import") (part "ADL5801"))
    )
    (comp (ref "IC34")
      (value "NCP702-1.8")
      (footprint "eagle-import:SOT95P240X110-5")
      (libsource (lib "eagle-import") (part "NCP702"))
    )
    (comp (ref "IC35")
      (value "MCP33131D-10-E/MS")
      (footprint "eagle-import:SOP50P490X110-10N")
      (libsource (lib "eagle-import") (part "MCP33131D-10-E/MS"))
    )
    (comp (ref "IC36")
      (value "LT5560")
      (footprint "eagle-import:SON50P300X300X80-9T165X238")
      (libsource (lib "eagle-import") (part "LT5560"))
    )
    (comp (ref "L46")
      (value "330n")
      (footprint "eagle-import:L0402")
      (libsource (lib "eagle-import") (part "INDUCTOR0402"))
    )
    (comp (ref "L47")
      (value "330n")
      (footprint "eagle-import:L0402")
      (libsource (lib "eagle-import") (part "INDUCTOR0402"))
    )
    (comp (ref "L48")
      (value "68n")
      (footprint "eagle-import:L0402")
      (libsource (lib "eagle-import") (part "INDUCTOR0402"))
    )
    (comp (ref "L49")
      (value "68n")
      (footprint "eagle-import:L0402")
      (libsource (lib "eagle-import") (part "INDUCTOR0402"))
    )
    (comp (ref "L50")
      (value "33n")
      (footprint "eagle-import:L0402")
      (libsource (lib "eagle-import") (part "INDUCTOR0402"))
    )
    (comp (ref "L51")
      (value "33n")
      (footprint "eagle-import:L0402")
      (libsource (lib "eagle-import") (part "INDUCTOR0402"))
    )
    (comp (ref "L52")
      (value "330n")
      (footprint "eagle-import:L0402")
      (libsource (lib "eagle-import") (part "INDUCTOR0402"))
    )
    (comp (ref "L53")
      (value "330n")
      (footprint "eagle-import:L0402")
      (libsource (lib "eagle-import") (part "INDUCTOR0402"))
    )
    (comp (ref "L59")
      (value "Ferrite")
      (footprint "eagle-import:R0402")
      (libsource (lib "eagle-import") (part "FERRITE"))
    )
    (comp (ref "L60")
      (value "Ferrite")
      (footprint "eagle-import:R0402")
      (libsource (lib "eagle-import") (part "FERRITE"))
    )
    (comp (ref "L61")
      (value "Ferrite")
      (footprint "eagle-import:R0402")
      (libsource (lib "eagle-import") (part "FERRITE"))
    )
    (comp (ref "L62")
      (value "Ferrite")
      (footprint "eagle-import:R0402")
      (libsource (lib "eagle-import") (part "FERRITE"))
    )
    (comp (ref "L63")
      (value "Ferrite")
      (footprint "eagle-import:R0402")
      (libsource (lib "eagle-import") (part "FERRITE"))
    )
    (comp (ref "R94")
      (value "4k7")
      (footprint "eagle-import:R0402")
      (libsource (lib "eagle-import") (part "R-EU_R0402"))
    )
    (comp (ref "R95")
      (value "4k7")
      (footprint "eagle-import:R0402")
      (libsource (lib "eagle-import") (part "R-EU_R0402"))
    )
    (comp (ref "R96")
      (value "220")
      (footprint "eagle-import:R0402")
      (libsource (lib "eagle-import") (part "R-EU_R0402"))
    )
    (comp (ref "R97")
      (value "220")
      (footprint "eagle-import:R0402")
      (libsource (lib "eagle-import") (part "R-EU_R0402"))
    )
    (comp (ref "R98")
      (value "220")
      (footprint "eagle-import:R0402")
      (libsource (lib "eagle-import") (part "R-EU_R0402"))
    )
    (comp (ref "R99")
      (value "220")
      (footprint "eagle-import:R0402")
      (libsource (lib "eagle-import") (part "R-EU_R0402"))
    )
    (comp (ref "R100")
      (value "DNP")
      (footprint "eagle-import:R0402")
      (libsource (lib "eagle-import") (part "R-EU_R0402"))
    )
    (comp (ref "R101")
      (value "1k")
      (footprint "eagle-import:R0402")
      (libsource (lib "eagle-import") (part "R-EU_R0402"))
    )
    (comp (ref "R102")
      (value "220")
      (footprint "eagle-import:R0402")
      (libsource (lib "eagle-import") (part "R-EU_R0402"))
    )
    (comp (ref "R103")
      (value "220")
      (footprint "eagle-import:R0402")
      (libsource (lib "eagle-import") (part "R-EU_R0402"))
    )
    (comp (ref "R173")
      (value "75")
      (footprint "eagle-import:R0402")
      (libsource (lib "eagle-import") (part "R-EU_R0402"))
    )
    (comp (ref "R174")
      (value "100")
      (footprint "eagle-import:R0402")
      (libsource (lib "eagle-import") (part "R-EU_R0402"))
    )
    (comp (ref "R175")
      (value "100")
      (footprint "eagle-import:R0402")
      (libsource (lib "eagle-import") (part "R-EU_R0402"))
    )
    (comp (ref "T3")
      (value "B012-617DB-1-63-B331")
      (footprint "eagle-import:EASTEVER_BALUN")
      (libsource (lib "eagle-import") (part "B012-617DB-1-63-B331"))
    )
    (comp (ref "TP19")
      (value "TPB1,27")
      (footprint "eagle-import:B1,27")
      (libsource (lib "eagle-import") (part "TPB1,27"))
    )
    (comp (ref "C78")
      (value "10u")
      (footprint "eagle-import:C1206")
      (libsource (lib "eagle-import") (part "C-EUC1206"))
    )
    (comp (ref "C79")
      (value "1u")
      (footprint "eagle-import:C0603")
      (libsource (lib "eagle-import") (part "C-EU?{colon}1C0603"))
    )
    (comp (ref "C80")
      (value "10n")
      (footprint "eagle-import:C0402")
      (libsource (lib "eagle-import") (part "C-EU?{colon}2C0402"))
    )
    (comp (ref "C81")
      (value "1u")
      (footprint "eagle-import:C0603")
      (libsource (lib "eagle-import") (part "C-EU?{colon}1C0603"))
    )
    (comp (ref "C82")
      (value "10u")
      (footprint "eagle-import:C1206")
      (libsource (lib "eagle-import") (part "C-EUC1206"))
    )
    (comp (ref "C83")
      (value "100n")
      (footprint "eagle-import:C0402")
      (libsource (lib "eagle-import") (part "C-EU?{colon}2C0402"))
    )
    (comp (ref "C84")
      (value "100n")
      (footprint "eagle-import:C0402")
      (libsource (lib "eagle-import") (part "C-EU?{colon}2C0402"))
    )
    (comp (ref "C85")
      (value "100n")
      (footprint "eagle-import:C0402")
      (libsource (lib "eagle-import") (part "C-EU?{colon}2C0402"))
    )
    (comp (ref "C86")
      (value "100n")
      (footprint "eagle-import:C0402")
      (libsource (lib "eagle-import") (part "C-EU?{colon}2C0402"))
    )
    (comp (ref "C87")
      (value "1u")
      (footprint "eagle-import:C0402")
      (libsource (lib "eagle-import") (part "C-EU?{colon}2C0402"))
    )
    (comp (ref "C88")
      (value "1u")
      (footprint "eagle-import:C0402")
      (libsource (lib "eagle-import") (part "C-EU?{colon}2C0402"))
    )
    (comp (ref "C89")
      (value "1u")
      (footprint "eagle-import:C0402")
      (libsource (lib "eagle-import") (part "C-EU?{colon}2C0402"))
    )
    (comp (ref "C90")
      (value "180p")
      (footprint "eagle-import:C0402")
      (libsource (lib "eagle-import") (part "C-EU?{colon}2C0402"))
    )
    (comp (ref "C91")
      (value "100n")
      (footprint "eagle-import:C0402")
      (libsource (lib "eagle-import") (part "C-EU?{colon}2C0402"))
    )
    (comp (ref "C92")
      (value "3n3")
      (footprint "eagle-import:C0402")
      (libsource (lib "eagle-import") (part "C-EU?{colon}2C0402"))
    )
    (comp (ref "C93")
      (value "10n")
      (footprint "eagle-import:C0402")
      (libsource (lib "eagle-import") (part "C-EU?{colon}2C0402"))
    )
    (comp (ref "C94")
      (value "100n")
      (footprint "eagle-import:C0402")
      (libsource (lib "eagle-import") (part "C-EU?{colon}2C0402"))
    )
    (comp (ref "C95")
      (value "18p")
      (footprint "eagle-import:C0402")
      (libsource (lib "eagle-import") (part "C-EU?{colon}2C0402"))
    )
    (comp (ref "IC19")
      (value "AP2114H")
      (footprint "eagle-import:SOT230P700X180-4")
      (libsource (lib "eagle-import") (part "AP2114H"))
    )
    (comp (ref "IC20")
      (value "NCP702-3.3")
      (footprint "eagle-import:SOT95P240X110-5")
      (libsource (lib "eagle-import") (part "NCP702"))
    )
    (comp (ref "IC21")
      (value "MAX2871")
      (footprint "eagle-import:QFN50P500X500X80-33T310")
      (libsource (lib "eagle-import") (part "MAX2871"))
    )
    (comp (ref "L28")
      (value "Ferrite")
      (footprint "eagle-import:R0402")
      (libsource (lib "eagle-import") (part "FERRITE"))
    )
    (comp (ref "L29")
      (value "Ferrite")
      (footprint "eagle-import:R0402")
      (libsource (lib "eagle-import") (part "FERRITE"))
    )
    (comp (ref "L65")
      (value "Ferrite")
      (footprint "eagle-import:R0402")
      (libsource (lib "eagle-import") (part "FERRITE"))
    )
    (comp (ref "R30")
      (value "5k1")
      (footprint "eagle-import:R0402")
      (libsource (lib "eagle-import") (part "R-EU_R0402"))
    )
    (comp (ref "R31")
      (value "10k")
      (footprint "eagle-import:R0402")
      (libsource (lib "eagle-import") (part "R-EU_R0402"))
    )
    (comp (ref "R32")
      (value "49R9")
      (footprint "eagle-import:R0402")
      (libsource (lib "eagle-import") (part "R-EU_R0402"))
    )
    (comp (ref "R33")
      (value "49R9")
      (footprint "eagle-import:R0402")
      (libsource (lib "eagle-import") (part "R-EU_R0402"))
    )
    (comp (ref "R34")
      (value "49R9")
      (footprint "eagle-import:R0402")
      (libsource (lib "eagle-import") (part "R-EU_R0402"))
    )
    (comp (ref "R35")
      (value "49R9")
      (footprint "eagle-import:R0402")
      (libsource (lib "eagle-import") (part "R-EU_R0402"))
    )
    (comp (ref "R36")
      (value "1k8")
      (footprint "eagle-import:R0402")
      (libsource (lib "eagle-import") (part "R-EU_R0402"))
    )
    (comp (ref "R37")
      (value "82")
      (footprint "eagle-import:R0402")
      (libsource (lib "eagle-import") (part "R-EU_R0402"))
    )
    (comp (ref "R38")
      (value "49R9")
      (footprint "eagle-import:R0402")
      (libsource (lib "eagle-import") (part "R-EU_R0402"))
    )
    (comp (ref "R39")
      (value "330")
      (footprint "eagle-import:R0402")
      (libsource (lib "eagle-import") (part "R-EU_R0402"))
    )
    (comp (ref "TP15")
      (value "TPB1,27")
      (footprint "eagle-import:B1,27")
      (libsource (lib "eagle-import") (part "TPB1,27"))
    )
    (comp (ref "TP16")
      (value "TPB1,27")
      (footprint "eagle-import:B1,27")
      (libsource (lib "eagle-import") (part "TPB1,27"))
    )
    (comp (ref "C49")
      (value "10u")
      (footprint "eagle-import:C1206")
      (libsource (lib "eagle-import") (part "C-EUC1206"))
    )
    (comp (ref "C50")
      (value "1u")
      (footprint "eagle-import:C0603")
      (libsource (lib "eagle-import") (part "C-EU?{colon}1C0603"))
    )
    (comp (ref "C51")
      (value "10n")
      (footprint "eagle-import:C0402")
      (libsource (lib "eagle-import") (part "C-EU?{colon}2C0402"))
    )
    (comp (ref "C52")
      (value "1u")
      (footprint "eagle-import:C0603")
      (libsource (lib "eagle-import") (part "C-EU?{colon}1C0603"))
    )
    (comp (ref "C53")
      (value "10u")
      (footprint "eagle-import:C1206")
      (libsource (lib "eagle-import") (part "C-EUC1206"))
    )
    (comp (ref "C54")
      (value "100n")
      (footprint "eagle-import:C0402")
      (libsource (lib "eagle-import") (part "C-EU?{colon}2C0402"))
    )
    (comp (ref "C55")
      (value "100n")
      (footprint "eagle-import:C0402")
      (libsource (lib "eagle-import") (part "C-EU?{colon}2C0402"))
    )
    (comp (ref "C56")
      (value "100n")
      (footprint "eagle-import:C0402")
      (libsource (lib "eagle-import") (part "C-EU?{colon}2C0402"))
    )
    (comp (ref "C57")
      (value "100n")
      (footprint "eagle-import:C0402")
      (libsource (lib "eagle-import") (part "C-EU?{colon}2C0402"))
    )
    (comp (ref "C58")
      (value "1u")
      (footprint "eagle-import:C0402")
      (libsource (lib "eagle-import") (part "C-EU?{colon}2C0402"))
    )
    (comp (ref "C59")
      (value "1u")
      (footprint "eagle-import:C0402")
      (libsource (lib "eagle-import") (part "C-EU?{colon}2C0402"))
    )
    (comp (ref "C60")
      (value "1u")
      (footprint "eagle-import:C0402")
      (libsource (lib "eagle-import") (part "C-EU?{colon}2C0402"))
    )
    (comp (ref "C61")
      (value "100n")
      (footprint "eagle-import:C0402")
      (libsource (lib "eagle-import") (part "C-EU?{colon}2C0402"))
    )
    (comp (ref "C62")
      (value "100n")
      (footprint "eagle-import:C0402")
      (libsource (lib "eagle-import") (part "C-EU?{colon}2C0402"))
    )
    (comp (ref "C63")
      (value "180p")
      (footprint "eagle-import:C0402")
      (libsource (lib "eagle-import") (part "C-EU?{colon}2C0402"))
    )
    (comp (ref "C64")
      (value "100n")
      (footprint "eagle-import:C0402")
      (libsource (lib "eagle-import") (part "C-EU?{colon}2C0402"))
    )
    (comp (ref "C65")
      (value "100n/RF")
      (footprint "eagle-import:C0402")
      (libsource (lib "eagle-import") (part "C-EU?{colon}2C0402"))
    )
    (comp (ref "C66")
      (value "3n3")
      (footprint "eagle-import:C0402")
      (libsource (lib "eagle-import") (part "C-EU?{colon}2C0402"))
    )
    (comp (ref "C67")
      (value "18p")
      (footprint "eagle-import:C0402")
      (libsource (lib "eagle-import") (part "C-EU?{colon}2C0402"))
    )
    (comp (ref "C68")
      (value "100n/RF")
      (footprint "eagle-import:C0402")
      (libsource (lib "eagle-import") (part "C-EU?{colon}2C0402"))
    )
    (comp (ref "C263")
      (value "100p")
      (footprint "eagle-import:C0402")
      (libsource (lib "eagle-import") (part "C-EU?{colon}2C0402"))
    )
    (comp (ref "C264")
      (value "100p")
      (footprint "eagle-import:C0402")
      (libsource (lib "eagle-import") (part "C-EU?{colon}2C0402"))
    )
    (comp (ref "C265")
      (value "100p")
      (footprint "eagle-import:C0402")
      (libsource (lib "eagle-import") (part "C-EU?{colon}2C0402"))
    )
    (comp (ref "C266")
      (value "100p")
      (footprint "eagle-import:C0402")
      (libsource (lib "eagle-import") (part "C-EU?{colon}2C0402"))
    )
    (comp (ref "C267")
      (value "100p")
      (footprint "eagle-import:C0402")
      (libsource (lib "eagle-import") (part "C-EU?{colon}2C0402"))
    )
    (comp (ref "C268")
      (value "100p")
      (footprint "eagle-import:C0402")
      (libsource (lib "eagle-import") (part "C-EU?{colon}2C0402"))
    )
    (comp (ref "C271")
      (value "100p")
      (footprint "eagle-import:C0402")
      (libsource (lib "eagle-import") (part "C-EU?{colon}2C0402"))
    )
    (comp (ref "C272")
      (value "100p")
      (footprint "eagle-import:C0402")
      (libsource (lib "eagle-import") (part "C-EU?{colon}2C0402"))
    )
    (comp (ref "C273")
      (value "100p")
      (footprint "eagle-import:C0402")
      (libsource (lib "eagle-import") (part "C-EU?{colon}2C0402"))
    )
    (comp (ref "C274")
      (value "100p")
      (footprint "eagle-import:C0402")
      (libsource (lib "eagle-import") (part "C-EU?{colon}2C0402"))
    )
    (comp (ref "IC8")
      (value "AP2114H")
      (footprint "eagle-import:SOT230P700X180-4")
      (libsource (lib "eagle-import") (part "AP2114H"))
    )
    (comp (ref "IC9")
      (value "NCP702-3.3")
      (footprint "eagle-import:SOT95P240X110-5")
      (libsource (lib "eagle-import") (part "NCP702"))
    )
    (comp (ref "IC10")
      (value "MAX2871")
      (footprint "eagle-import:QFN50P500X500X80-33T310")
      (libsource (lib "eagle-import") (part "MAX2871"))
    )
    (comp (ref "IC11")
      (value "RFSW6042")
      (footprint "eagle-import:QFN40P180X180X55-13T76N")
      (libsource (lib "eagle-import") (part "RFSW6042"))
    )
    (comp (ref "IC12")
      (value "RFSW6042")
      (footprint "eagle-import:QFN40P180X180X55-13T76N")
      (libsource (lib "eagle-import") (part "RFSW6042"))
    )
    (comp (ref "L19")
      (value "Ferrite")
      (footprint "eagle-import:R0402")
      (libsource (lib "eagle-import") (part "FERRITE"))
    )
    (comp (ref "L20")
      (value "Ferrite")
      (footprint "eagle-import:R0402")
      (libsource (lib "eagle-import") (part "FERRITE"))
    )
    (comp (ref "L64")
      (value "Ferrite")
      (footprint "eagle-import:R0402")
      (libsource (lib "eagle-import") (part "FERRITE"))
    )
    (comp (ref "LP1")
      (value "LP0603A0947ANTR")
      (footprint "eagle-import:FILTRDFN160X84X70-4N")
      (libsource (lib "eagle-import") (part "LP0603A"))
    )
    (comp (ref "LP2")
      (value "LP0603N3500ANTR")
      (footprint "eagle-import:FILTRDFN160X84X70-4N")
      (libsource (lib "eagle-import") (part "LP0603A"))
    )
    (comp (ref "LP3")
      (value "LP0603A1880ANTR")
      (footprint "eagle-import:FILTRDFN160X84X70-4N")
      (libsource (lib "eagle-import") (part "LP0603A"))
    )
    (comp (ref "R10")
      (value "5k1")
      (footprint "eagle-import:R0402")
      (libsource (lib "eagle-import") (part "R-EU_R0402"))
    )
    (comp (ref "R11")
      (value "10k")
      (footprint "eagle-import:R0402")
      (libsource (lib "eagle-import") (part "R-EU_R0402"))
    )
    (comp (ref "R12")
      (value "49R9")
      (footprint "eagle-import:R0402")
      (libsource (lib "eagle-import") (part "R-EU_R0402"))
    )
    (comp (ref "R13")
      (value "49R9")
      (footprint "eagle-import:R0402")
      (libsource (lib "eagle-import") (part "R-EU_R0402"))
    )
    (comp (ref "R14")
      (value "49R9")
      (footprint "eagle-import:R0402")
      (libsource (lib "eagle-import") (part "R-EU_R0402"))
    )
    (comp (ref "R15")
      (value "1k8")
      (footprint "eagle-import:R0402")
      (libsource (lib "eagle-import") (part "R-EU_R0402"))
    )
    (comp (ref "R16")
      (value "82")
      (footprint "eagle-import:R0402")
      (libsource (lib "eagle-import") (part "R-EU_R0402"))
    )
    (comp (ref "R17")
      (value "330")
      (footprint "eagle-import:R0402")
      (libsource (lib "eagle-import") (part "R-EU_R0402"))
    )
    (comp (ref "R18")
      (value "10k")
      (footprint "eagle-import:R0402")
      (libsource (lib "eagle-import") (part "R-EU_R0402"))
    )
    (comp (ref "R19")
      (value "10k")
      (footprint "eagle-import:R0402")
      (libsource (lib "eagle-import") (part "R-EU_R0402"))
    )
    (comp (ref "R20")
      (value "10k")
      (footprint "eagle-import:R0402")
      (libsource (lib "eagle-import") (part "R-EU_R0402"))
    )
    (comp (ref "R21")
      (value "10k")
      (footprint "eagle-import:R0402")
      (libsource (lib "eagle-import") (part "R-EU_R0402"))
    )
    (comp (ref "R22")
      (value "10k")
      (footprint "eagle-import:R0402")
      (libsource (lib "eagle-import") (part "R-EU_R0402"))
    )
    (comp (ref "R23")
      (value "10k")
      (footprint "eagle-import:R0402")
      (libsource (lib "eagle-import") (part "R-EU_R0402"))
    )
    (comp (ref "R24")
      (value "10k")
      (footprint "eagle-import:R0402")
      (libsource (lib "eagle-import") (part "R-EU_R0402"))
    )
    (comp (ref "R25")
      (value "10k")
      (footprint "eagle-import:R0402")
      (libsource (lib "eagle-import") (part "R-EU_R0402"))
    )
    (comp (ref "R163")
      (value "10k")
      (footprint "eagle-import:R0402")
      (libsource (lib "eagle-import") (part "R-EU_R0402"))
    )
    (comp (ref "R164")
      (value "100")
      (footprint "eagle-import:R0402")
      (libsource (lib "eagle-import") (part "R-EU_R0402"))
    )
    (comp (ref "R165")
      (value "10k")
      (footprint "eagle-import:R0402")
      (libsource (lib "eagle-import") (part "R-EU_R0402"))
    )
    (comp (ref "R166")
      (value "10k")
      (footprint "eagle-import:R0402")
      (libsource (lib "eagle-import") (part "R-EU_R0402"))
    )
    (comp (ref "R167")
      (value "100")
      (footprint "eagle-import:R0402")
      (libsource (lib "eagle-import") (part "R-EU_R0402"))
    )
    (comp (ref "R170")
      (value "100")
      (footprint "eagle-import:R0402")
      (libsource (lib "eagle-import") (part "R-EU_R0402"))
    )
    (comp (ref "R171")
      (value "100")
      (footprint "eagle-import:R0402")
      (libsource (lib "eagle-import") (part "R-EU_R0402"))
    )
    (comp (ref "TP13")
      (value "TPB1,27")
      (footprint "eagle-import:B1,27")
      (libsource (lib "eagle-import") (part "TPB1,27"))
    )
    (comp (ref "TP14")
      (value "TPB1,27")
      (footprint "eagle-import:B1,27")
      (libsource (lib "eagle-import") (part "TPB1,27"))
    )
    (comp (ref "C96")
      (value "100n/RF")
      (footprint "eagle-import:C0402")
      (libsource (lib "eagle-import") (part "C-EU?{colon}2C0402"))
    )
    (comp (ref "C97")
      (value "100n")
      (footprint "eagle-import:C0402")
      (libsource (lib "eagle-import") (part "C-EU?{colon}2C0402"))
    )
    (comp (ref "C98")
      (value "100n")
      (footprint "eagle-import:C0402")
      (libsource (lib "eagle-import") (part "C-EU?{colon}2C0402"))
    )
    (comp (ref "C99")
      (value "100n/RF")
      (footprint "eagle-import:C0402")
      (libsource (lib "eagle-import") (part "C-EU?{colon}2C0402"))
    )
    (comp (ref "C100")
      (value "1u")
      (footprint "eagle-import:C0402")
      (libsource (lib "eagle-import") (part "C-EU?{colon}2C0402"))
    )
    (comp (ref "C101")
      (value "1u")
      (footprint "eagle-import:C0402")
      (libsource (lib "eagle-import") (part "C-EU?{colon}2C0402"))
    )
    (comp (ref "C102")
      (value "100n")
      (footprint "eagle-import:C0402")
      (libsource (lib "eagle-import") (part "C-EU?{colon}2C0402"))
    )
    (comp (ref "C103")
      (value "100n")
      (footprint "eagle-import:C0402")
      (libsource (lib "eagle-import") (part "C-EU?{colon}2C0402"))
    )
    (comp (ref "C104")
      (value "10n")
      (footprint "eagle-import:C0402")
      (libsource (lib "eagle-import") (part "C-EU?{colon}2C0402"))
    )
    (comp (ref "C105")
      (value "10n")
      (footprint "eagle-import:C0402")
      (libsource (lib "eagle-import") (part "C-EU?{colon}2C0402"))
    )
    (comp (ref "C106")
      (value "10n")
      (footprint "eagle-import:C0402")
      (libsource (lib "eagle-import") (part "C-EU?{colon}2C0402"))
    )
    (comp (ref "C107")
      (value "DNP")
      (footprint "eagle-import:C0402")
      (libsource (lib "eagle-import") (part "C-EU?{colon}2C0402"))
    )
    (comp (ref "C108")
      (value "1u")
      (footprint "eagle-import:C0402")
      (libsource (lib "eagle-import") (part "C-EU?{colon}2C0402"))
    )
    (comp (ref "C109")
      (value "100n/RF")
      (footprint "eagle-import:C0402")
      (libsource (lib "eagle-import") (part "C-EU?{colon}2C0402"))
    )
    (comp (ref "C110")
      (value "100n/RF")
      (footprint "eagle-import:C0402")
      (libsource (lib "eagle-import") (part "C-EU?{colon}2C0402"))
    )
    (comp (ref "C111")
      (value "10n")
      (footprint "eagle-import:C0402")
      (libsource (lib "eagle-import") (part "C-EU?{colon}2C0402"))
    )
    (comp (ref "C112")
      (value "DNP")
      (footprint "eagle-import:C0402")
      (libsource (lib "eagle-import") (part "C-EU?{colon}2C0402"))
    )
    (comp (ref "C113")
      (value "DNP")
      (footprint "eagle-import:C0402")
      (libsource (lib "eagle-import") (part "C-EU?{colon}2C0402"))
    )
    (comp (ref "C114")
      (value "100n")
      (footprint "eagle-import:C0402")
      (libsource (lib "eagle-import") (part "C-EU?{colon}2C0402"))
    )
    (comp (ref "C115")
      (value "100n")
      (footprint "eagle-import:C0402")
      (libsource (lib "eagle-import") (part "C-EU?{colon}2C0402"))
    )
    (comp (ref "C116")
      (value "100n")
      (footprint "eagle-import:C0402")
      (libsource (lib "eagle-import") (part "C-EU?{colon}2C0402"))
    )
    (comp (ref "C117")
      (value "100n")
      (footprint "eagle-import:C0402")
      (libsource (lib "eagle-import") (part "C-EU?{colon}2C0402"))
    )
    (comp (ref "C118")
      (value "100n")
      (footprint "eagle-import:C0402")
      (libsource (lib "eagle-import") (part "C-EU?{colon}2C0402"))
    )
    (comp (ref "C119")
      (value "100n")
      (footprint "eagle-import:C0402")
      (libsource (lib "eagle-import") (part "C-EU?{colon}2C0402"))
    )
    (comp (ref "C120")
      (value "10n")
      (footprint "eagle-import:C0402")
      (libsource (lib "eagle-import") (part "C-EU?{colon}2C0402"))
    )
    (comp (ref "C121")
      (value "330p")
      (footprint "eagle-import:C0402")
      (libsource (lib "eagle-import") (part "C-EU?{colon}2C0402"))
    )
    (comp (ref "C122")
      (value "100n")
      (footprint "eagle-import:C0402")
      (libsource (lib "eagle-import") (part "C-EU?{colon}2C0402"))
    )
    (comp (ref "C123")
      (value "10n")
      (footprint "eagle-import:C0402")
      (libsource (lib "eagle-import") (part "C-EU?{colon}2C0402"))
    )
    (comp (ref "C124")
      (value "120p")
      (footprint "eagle-import:C0402")
      (libsource (lib "eagle-import") (part "C-EU?{colon}2C0402"))
    )
    (comp (ref "C125")
      (value "330p")
      (footprint "eagle-import:C0402")
      (libsource (lib "eagle-import") (part "C-EU?{colon}2C0402"))
    )
    (comp (ref "C126")
      (value "330p")
      (footprint "eagle-import:C0402")
      (libsource (lib "eagle-import") (part "C-EU?{colon}2C0402"))
    )
    (comp (ref "C127")
      (value "330p")
      (footprint "eagle-import:C0402")
      (libsource (lib "eagle-import") (part "C-EU?{colon}2C0402"))
    )
    (comp (ref "C128")
      (value "150p")
      (footprint "eagle-import:C0402")
      (libsource (lib "eagle-import") (part "C-EU?{colon}2C0402"))
    )
    (comp (ref "C129")
      (value "1u")
      (footprint "eagle-import:C0402")
      (libsource (lib "eagle-import") (part "C-EU?{colon}2C0402"))
    )
    (comp (ref "C130")
      (value "33p")
      (footprint "eagle-import:C0402")
      (libsource (lib "eagle-import") (part "C-EU?{colon}2C0402"))
    )
    (comp (ref "C131")
      (value "1u")
      (footprint "eagle-import:C0402")
      (libsource (lib "eagle-import") (part "C-EU?{colon}2C0402"))
    )
    (comp (ref "C132")
      (value "100n")
      (footprint "eagle-import:C0402")
      (libsource (lib "eagle-import") (part "C-EU?{colon}2C0402"))
    )
    (comp (ref "C269")
      (value "100n")
      (footprint "eagle-import:C0402")
      (libsource (lib "eagle-import") (part "C-EU?{colon}2C0402"))
    )
    (comp (ref "IC22")
      (value "LT5560")
      (footprint "eagle-import:SON50P300X300X80-9T165X238")
      (libsource (lib "eagle-import") (part "LT5560"))
    )
    (comp (ref "IC23")
      (value "THS4521IDGKR")
      (footprint "eagle-import:SOP65P490X110-8N")
      (libsource (lib "eagle-import") (part "THS4521IDGKR"))
    )
    (comp (ref "IC24")
      (value "ADL5801")
      (footprint "eagle-import:QFN50P400X400X100-25T250N")
      (libsource (lib "eagle-import") (part "ADL5801"))
    )
    (comp (ref "IC25")
      (value "NCP702-1.8")
      (footprint "eagle-import:SOT95P240X110-5")
      (libsource (lib "eagle-import") (part "NCP702"))
    )
    (comp (ref "IC26")
      (value "MCP33131D-10-E/MS")
      (footprint "eagle-import:SOP50P490X110-10N")
      (libsource (lib "eagle-import") (part "MCP33131D-10-E/MS"))
    )
    (comp (ref "J2")
      (value "BU-1420701851")
      (footprint "eagle-import:BU-1420701851")
      (libsource (lib "eagle-import") (part "BU-1420701851"))
    )
    (comp (ref "L12")
      (value "Ferrite")
      (footprint "eagle-import:R0402")
      (libsource (lib "eagle-import") (part "FERRITE"))
    )
    (comp (ref "L13")
      (value "Ferrite")
      (footprint "eagle-import:R0402")
      (libsource (lib "eagle-import") (part "FERRITE"))
    )
    (comp (ref "L15")
      (value "Ferrite")
      (footprint "eagle-import:R0402")
      (libsource (lib "eagle-import") (part "FERRITE"))
    )
    (comp (ref "L16")
      (value "Ferrite")
      (footprint "eagle-import:R0402")
      (libsource (lib "eagle-import") (part "FERRITE"))
    )
    (comp (ref "L17")
      (value "Ferrite")
      (footprint "eagle-import:R0402")
      (libsource (lib "eagle-import") (part "FERRITE"))
    )
    (comp (ref "L30")
      (value "330n")
      (footprint "eagle-import:L0402")
      (libsource (lib "eagle-import") (part "INDUCTOR0402"))
    )
    (comp (ref "L31")
      (value "330n")
      (footprint "eagle-import:L0402")
      (libsource (lib "eagle-import") (part "INDUCTOR0402"))
    )
    (comp (ref "L32")
      (value "330n")
      (footprint "eagle-import:L0402")
      (libsource (lib "eagle-import") (part "INDUCTOR0402"))
    )
    (comp (ref "L33")
      (value "330n")
      (footprint "eagle-import:L0402")
      (libsource (lib "eagle-import") (part "INDUCTOR0402"))
    )
    (comp (ref "L34")
      (value "68n")
      (footprint "eagle-import:L0402")
      (libsource (lib "eagle-import") (part "INDUCTOR0402"))
    )
    (comp (ref "L35")
      (value "68n")
      (footprint "eagle-import:L0402")
      (libsource (lib "eagle-import") (part "INDUCTOR0402"))
    )
    (comp (ref "L36")
      (value "33n")
      (footprint "eagle-import:L0402")
      (libsource (lib "eagle-import") (part "INDUCTOR0402"))
    )
    (comp (ref "L37")
      (value "33n")
      (footprint "eagle-import:L0402")
      (libsource (lib "eagle-import") (part "INDUCTOR0402"))
    )
    (comp (ref "R45")
      (value "49R9")
      (footprint "eagle-import:R0402")
      (libsource (lib "eagle-import") (part "R-EU_R0402"))
    )
    (comp (ref "R46")
      (value "49R9")
      (footprint "eagle-import:R0402")
      (libsource (lib "eagle-import") (part "R-EU_R0402"))
    )
    (comp (ref "R48")
      (value "PAT0816-C-3DB-T5")
      (footprint "eagle-import:PAT0816")
      (libsource (lib "eagle-import") (part "PAT0816-C-3DB-T5"))
    )
    (comp (ref "R49")
      (value "PAT0816-C-3DB-T5")
      (footprint "eagle-import:PAT0816")
      (libsource (lib "eagle-import") (part "PAT0816-C-3DB-T5"))
    )
    (comp (ref "R50")
      (value "49R9")
      (footprint "eagle-import:R0402")
      (libsource (lib "eagle-import") (part "R-EU_R0402"))
    )
    (comp (ref "R53")
      (value "220")
      (footprint "eagle-import:R0402")
      (libsource (lib "eagle-import") (part "R-EU_R0402"))
    )
    (comp (ref "R54")
      (value "220")
      (footprint "eagle-import:R0402")
      (libsource (lib "eagle-import") (part "R-EU_R0402"))
    )
    (comp (ref "R55")
      (value "6k8")
      (footprint "eagle-import:R0402")
      (libsource (lib "eagle-import") (part "R-EU_R0402"))
    )
    (comp (ref "R56")
      (value "6k8")
      (footprint "eagle-import:R0402")
      (libsource (lib "eagle-import") (part "R-EU_R0402"))
    )
    (comp (ref "R57")
      (value "DNP")
      (footprint "eagle-import:R0402")
      (libsource (lib "eagle-import") (part "R-EU_R0402"))
    )
    (comp (ref "R58")
      (value "220")
      (footprint "eagle-import:R0402")
      (libsource (lib "eagle-import") (part "R-EU_R0402"))
    )
    (comp (ref "R59")
      (value "220")
      (footprint "eagle-import:R0402")
      (libsource (lib "eagle-import") (part "R-EU_R0402"))
    )
    (comp (ref "R60")
      (value "1k")
      (footprint "eagle-import:R0402")
      (libsource (lib "eagle-import") (part "R-EU_R0402"))
    )
    (comp (ref "R61")
      (value "220")
      (footprint "eagle-import:R0402")
      (libsource (lib "eagle-import") (part "R-EU_R0402"))
    )
    (comp (ref "R62")
      (value "220")
      (footprint "eagle-import:R0402")
      (libsource (lib "eagle-import") (part "R-EU_R0402"))
    )
    (comp (ref "R63")
      (value "56")
      (footprint "eagle-import:R0402")
      (libsource (lib "eagle-import") (part "R-EU_R0402"))
    )
    (comp (ref "R64")
      (value "20")
      (footprint "eagle-import:R0402")
      (libsource (lib "eagle-import") (part "R-EU_R0402"))
    )
    (comp (ref "R65")
      (value "20")
      (footprint "eagle-import:R0402")
      (libsource (lib "eagle-import") (part "R-EU_R0402"))
    )
    (comp (ref "R66")
      (value "56")
      (footprint "eagle-import:R0402")
      (libsource (lib "eagle-import") (part "R-EU_R0402"))
    )
    (comp (ref "R168")
      (value "75")
      (footprint "eagle-import:R0402")
      (libsource (lib "eagle-import") (part "R-EU_R0402"))
    )
    (comp (ref "R169")
      (value "100")
      (footprint "eagle-import:R0402")
      (libsource (lib "eagle-import") (part "R-EU_R0402"))
    )
    (comp (ref "R172")
      (value "100")
      (footprint "eagle-import:R0402")
      (libsource (lib "eagle-import") (part "R-EU_R0402"))
    )
    (comp (ref "T1")
      (value "B012-617DB-1-63-B331")
      (footprint "eagle-import:EASTEVER_BALUN")
      (libsource (lib "eagle-import") (part "B012-617DB-1-63-B331"))
    )
    (comp (ref "TP17")
      (value "TPB1,27")
      (footprint "eagle-import:B1,27")
      (libsource (lib "eagle-import") (part "TPB1,27"))
    )
    (comp (ref "C69")
      (value "100n")
      (footprint "eagle-import:C0402")
      (libsource (lib "eagle-import") (part "C-EU?{colon}2C0402"))
    )
    (comp (ref "C70")
      (value "100n")
      (footprint "eagle-import:C0402")
      (libsource (lib "eagle-import") (part "C-EU?{colon}2C0402"))
    )
    (comp (ref "C71")
      (value "100n/RF")
      (footprint "eagle-import:C0402")
      (libsource (lib "eagle-import") (part "C-EU?{colon}2C0402"))
    )
    (comp (ref "C72")
      (value "100n")
      (footprint "eagle-import:C0402")
      (libsource (lib "eagle-import") (part "C-EU?{colon}2C0402"))
    )
    (comp (ref "C73")
      (value "100n")
      (footprint "eagle-import:C0402")
      (libsource (lib "eagle-import") (part "C-EU?{colon}2C0402"))
    )
    (comp (ref "C74")
      (value "100n/RF")
      (footprint "eagle-import:C0402")
      (libsource (lib "eagle-import") (part "C-EU?{colon}2C0402"))
    )
    (comp (ref "C75")
      (value "100n")
      (footprint "eagle-import:C0402")
      (libsource (lib "eagle-import") (part "C-EU?{colon}2C0402"))
    )
    (comp (ref "C76")
      (value "100n")
      (footprint "eagle-import:C0402")
      (libsource (lib "eagle-import") (part "C-EU?{colon}2C0402"))
    )
    (comp (ref "C77")
      (value "100n")
      (footprint "eagle-import:C0402")
      (libsource (lib "eagle-import") (part "C-EU?{colon}2C0402"))
    )
    (comp (ref "C235")
      (value "100p")
      (footprint "eagle-import:C0402")
      (libsource (lib "eagle-import") (part "C-EU?{colon}2C0402"))
    )
    (comp (ref "C236")
      (value "100p")
      (footprint "eagle-import:C0402")
      (libsource (lib "eagle-import") (part "C-EU?{colon}2C0402"))
    )
    (comp (ref "C237")
      (value "100p")
      (footprint "eagle-import:C0402")
      (libsource (lib "eagle-import") (part "C-EU?{colon}2C0402"))
    )
    (comp (ref "C238")
      (value "100p")
      (footprint "eagle-import:C0402")
      (libsource (lib "eagle-import") (part "C-EU?{colon}2C0402"))
    )
    (comp (ref "C239")
      (value "100p")
      (footprint "eagle-import:C0402")
      (libsource (lib "eagle-import") (part "C-EU?{colon}2C0402"))
    )
    (comp (ref "C240")
      (value "100p")
      (footprint "eagle-import:C0402")
      (libsource (lib "eagle-import") (part "C-EU?{colon}2C0402"))
    )
    (comp (ref "C241")
      (value "100p")
      (footprint "eagle-import:C0402")
      (libsource (lib "eagle-import") (part "C-EU?{colon}2C0402"))
    )
    (comp (ref "C242")
      (value "100p")
      (footprint "eagle-import:C0402")
      (libsource (lib "eagle-import") (part "C-EU?{colon}2C0402"))
    )
    (comp (ref "C243")
      (value "100p")
      (footprint "eagle-import:C0402")
      (libsource (lib "eagle-import") (part "C-EU?{colon}2C0402"))
    )
    (comp (ref "C244")
      (value "100p")
      (footprint "eagle-import:C0402")
      (libsource (lib "eagle-import") (part "C-EU?{colon}2C0402"))
    )
    (comp (ref "C245")
      (value "100p")
      (footprint "eagle-import:C0402")
      (libsource (lib "eagle-import") (part "C-EU?{colon}2C0402"))
    )
    (comp (ref "C246")
      (value "100p")
      (footprint "eagle-import:C0402")
      (libsource (lib "eagle-import") (part "C-EU?{colon}2C0402"))
    )
    (comp (ref "C247")
      (value "100p")
      (footprint "eagle-import:C0402")
      (libsource (lib "eagle-import") (part "C-EU?{colon}2C0402"))
    )
    (comp (ref "C248")
      (value "100p")
      (footprint "eagle-import:C0402")
      (libsource (lib "eagle-import") (part "C-EU?{colon}2C0402"))
    )
    (comp (ref "C249")
      (value "100p")
      (footprint "eagle-import:C0402")
      (libsource (lib "eagle-import") (part "C-EU?{colon}2C0402"))
    )
    (comp (ref "C250")
      (value "100p")
      (footprint "eagle-import:C0402")
      (libsource (lib "eagle-import") (part "C-EU?{colon}2C0402"))
    )
    (comp (ref "C251")
      (value "100p")
      (footprint "eagle-import:C0402")
      (libsource (lib "eagle-import") (part "C-EU?{colon}2C0402"))
    )
    (comp (ref "C252")
      (value "100p")
      (footprint "eagle-import:C0402")
      (libsource (lib "eagle-import") (part "C-EU?{colon}2C0402"))
    )
    (comp (ref "C253")
      (value "100p")
      (footprint "eagle-import:C0402")
      (libsource (lib "eagle-import") (part "C-EU?{colon}2C0402"))
    )
    (comp (ref "C254")
      (value "100p")
      (footprint "eagle-import:C0402")
      (libsource (lib "eagle-import") (part "C-EU?{colon}2C0402"))
    )
    (comp (ref "C255")
      (value "100p")
      (footprint "eagle-import:C0402")
      (libsource (lib "eagle-import") (part "C-EU?{colon}2C0402"))
    )
    (comp (ref "C256")
      (value "100p")
      (footprint "eagle-import:C0402")
      (libsource (lib "eagle-import") (part "C-EU?{colon}2C0402"))
    )
    (comp (ref "C257")
      (value "100p")
      (footprint "eagle-import:C0402")
      (libsource (lib "eagle-import") (part "C-EU?{colon}2C0402"))
    )
    (comp (ref "C258")
      (value "100p")
      (footprint "eagle-import:C0402")
      (libsource (lib "eagle-import") (part "C-EU?{colon}2C0402"))
    )
    (comp (ref "C259")
      (value "100p")
      (footprint "eagle-import:C0402")
      (libsource (lib "eagle-import") (part "C-EU?{colon}2C0402"))
    )
    (comp (ref "C260")
      (value "100p")
      (footprint "eagle-import:C0402")
      (libsource (lib "eagle-import") (part "C-EU?{colon}2C0402"))
    )
    (comp (ref "C261")
      (value "100p")
      (footprint "eagle-import:C0402")
      (libsource (lib "eagle-import") (part "C-EU?{colon}2C0402"))
    )
    (comp (ref "C262")
      (value "100p")
      (footprint "eagle-import:C0402")
      (libsource (lib "eagle-import") (part "C-EU?{colon}2C0402"))
    )
    (comp (ref "IC13")
      (value "QPC6324")
      (footprint "eagle-import:QFN50P400X400X75-21T206")
      (libsource (lib "eagle-import") (part "QPC6324"))
    )
    (comp (ref "IC14")
      (value "RFSA3714")
      (footprint "eagle-import:QFN50P400X400X75-25T270")
      (libsource (lib "eagle-import") (part "RFSA3714"))
    )
    (comp (ref "IC15")
      (value "TRF37A73")
      (footprint "eagle-import:SON50P200X200X80-9T90X160N")
      (libsource (lib "eagle-import") (part "TRF37A73"))
    )
    (comp (ref "IC16")
      (value "QPC6324")
      (footprint "eagle-import:QFN50P400X400X75-21T206")
      (libsource (lib "eagle-import") (part "QPC6324"))
    )
    (comp (ref "IC17")
      (value "QPC6324")
      (footprint "eagle-import:QFN50P400X400X75-21T206")
      (libsource (lib "eagle-import") (part "QPC6324"))
    )
    (comp (ref "IC18")
      (value "QPC6324")
      (footprint "eagle-import:QFN50P400X400X75-21T206")
      (libsource (lib "eagle-import") (part "QPC6324"))
    )
    (comp (ref "L11")
      (value "10u")
      (footprint "eagle-import:INDC2012X100N")
      (libsource (lib "eagle-import") (part "INDUCTOR"))
    )
    (comp (ref "L21")
      (value "Ferrite")
      (footprint "eagle-import:R0402")
      (libsource (lib "eagle-import") (part "FERRITE"))
    )
    (comp (ref "L22")
      (value "Ferrite")
      (footprint "eagle-import:R0402")
      (libsource (lib "eagle-import") (part "FERRITE"))
    )
    (comp (ref "L23")
      (value "Ferrite")
      (footprint "eagle-import:R0402")
      (libsource (lib "eagle-import") (part "FERRITE"))
    )
    (comp (ref "L24")
      (value "330n")
      (footprint "eagle-import:L0402")
      (libsource (lib "eagle-import") (part "INDUCTOR0402"))
    )
    (comp (ref "L25")
      (value "Ferrite")
      (footprint "eagle-import:R0402")
      (libsource (lib "eagle-import") (part "FERRITE"))
    )
    (comp (ref "L26")
      (value "Ferrite")
      (footprint "eagle-import:R0402")
      (libsource (lib "eagle-import") (part "FERRITE"))
    )
    (comp (ref "L27")
      (value "Ferrite")
      (footprint "eagle-import:R0402")
      (libsource (lib "eagle-import") (part "FERRITE"))
    )
    (comp (ref "R26")
      (value "2R7")
      (footprint "eagle-import:R0402")
      (libsource (lib "eagle-import") (part "R-EU_R0402"))
    )
    (comp (ref "R27")
      (value "402")
      (footprint "eagle-import:R0402")
      (libsource (lib "eagle-import") (part "R-EU_R0402"))
    )
    (comp (ref "R28")
      (value "56")
      (footprint "eagle-import:R0402")
      (libsource (lib "eagle-import") (part "R-EU_R0402"))
    )
    (comp (ref "R29")
      (value "2R7")
      (footprint "eagle-import:R0402")
      (libsource (lib "eagle-import") (part "R-EU_R0402"))
    )
    (comp (ref "R149")
      (value "10k")
      (footprint "eagle-import:R0402")
      (libsource (lib "eagle-import") (part "R-EU_R0402"))
    )
    (comp (ref "R150")
      (value "10k")
      (footprint "eagle-import:R0402")
      (libsource (lib "eagle-import") (part "R-EU_R0402"))
    )
    (comp (ref "R151")
      (value "10k")
      (footprint "eagle-import:R0402")
      (libsource (lib "eagle-import") (part "R-EU_R0402"))
    )
    (comp (ref "R152")
      (value "10k")
      (footprint "eagle-import:R0402")
      (libsource (lib "eagle-import") (part "R-EU_R0402"))
    )
    (comp (ref "R153")
      (value "10k")
      (footprint "eagle-import:R0402")
      (libsource (lib "eagle-import") (part "R-EU_R0402"))
    )
    (comp (ref "R154")
      (value "10k")
      (footprint "eagle-import:R0402")
      (libsource (lib "eagle-import") (part "R-EU_R0402"))
    )
    (comp (ref "R155")
      (value "10k")
      (footprint "eagle-import:R0402")
      (libsource (lib "eagle-import") (part "R-EU_R0402"))
    )
    (comp (ref "R156")
      (value "10k")
      (footprint "eagle-import:R0402")
      (libsource (lib "eagle-import") (part "R-EU_R0402"))
    )
    (comp (ref "R157")
      (value "10k")
      (footprint "eagle-import:R0402")
      (libsource (lib "eagle-import") (part "R-EU_R0402"))
    )
    (comp (ref "R158")
      (value "10k")
      (footprint "eagle-import:R0402")
      (libsource (lib "eagle-import") (part "R-EU_R0402"))
    )
    (comp (ref "R159")
      (value "10k")
      (footprint "eagle-import:R0402")
      (libsource (lib "eagle-import") (part "R-EU_R0402"))
    )
    (comp (ref "R160")
      (value "10k")
      (footprint "eagle-import:R0402")
      (libsource (lib "eagle-import") (part "R-EU_R0402"))
    )
    (comp (ref "R161")
      (value "10k")
      (footprint "eagle-import:R0402")
      (libsource (lib "eagle-import") (part "R-EU_R0402"))
    )
    (comp (ref "R162")
      (value "10k")
      (footprint "eagle-import:R0402")
      (libsource (lib "eagle-import") (part "R-EU_R0402"))
    )
    (comp (ref "C29")
      (value "100n")
      (footprint "eagle-import:C0402")
      (libsource (lib "eagle-import") (part "C-EU?{colon}2C0402"))
    )
    (comp (ref "C30")
      (value "10n")
      (footprint "eagle-import:C0402")
      (libsource (lib "eagle-import") (part "C-EU?{colon}2C0402"))
    )
    (comp (ref "C31")
      (value "100n")
      (footprint "eagle-import:C0402")
      (libsource (lib "eagle-import") (part "C-EU?{colon}2C0402"))
    )
    (comp (ref "C32")
      (value "100n")
      (footprint "eagle-import:C0402")
      (libsource (lib "eagle-import") (part "C-EU?{colon}2C0402"))
    )
    (comp (ref "C33")
      (value "100n")
      (footprint "eagle-import:C0402")
      (libsource (lib "eagle-import") (part "C-EU?{colon}2C0402"))
    )
    (comp (ref "C34")
      (value "100n")
      (footprint "eagle-import:C0402")
      (libsource (lib "eagle-import") (part "C-EU?{colon}2C0402"))
    )
    (comp (ref "C35")
      (value "DNP")
      (footprint "eagle-import:C0402")
      (libsource (lib "eagle-import") (part "C-EU?{colon}2C0402"))
    )
    (comp (ref "C36")
      (value "DNP")
      (footprint "eagle-import:C0402")
      (libsource (lib "eagle-import") (part "C-EU?{colon}2C0402"))
    )
    (comp (ref "C37")
      (value "DNP")
      (footprint "eagle-import:C0402")
      (libsource (lib "eagle-import") (part "C-EU?{colon}2C0402"))
    )
    (comp (ref "C38")
      (value "56p")
      (footprint "eagle-import:C0402")
      (libsource (lib "eagle-import") (part "C-EU?{colon}2C0402"))
    )
    (comp (ref "C39")
      (value "10n")
      (footprint "eagle-import:C0402")
      (libsource (lib "eagle-import") (part "C-EU?{colon}2C0402"))
    )
    (comp (ref "C40")
      (value "DNP")
      (footprint "eagle-import:C0402")
      (libsource (lib "eagle-import") (part "C-EU?{colon}2C0402"))
    )
    (comp (ref "C41")
      (value "DNP")
      (footprint "eagle-import:C0402")
      (libsource (lib "eagle-import") (part "C-EU?{colon}2C0402"))
    )
    (comp (ref "C42")
      (value "DNP")
      (footprint "eagle-import:C0402")
      (libsource (lib "eagle-import") (part "C-EU?{colon}2C0402"))
    )
    (comp (ref "C43")
      (value "180p")
      (footprint "eagle-import:C0402")
      (libsource (lib "eagle-import") (part "C-EU?{colon}2C0402"))
    )
    (comp (ref "C44")
      (value "DNP")
      (footprint "eagle-import:C0402")
      (libsource (lib "eagle-import") (part "C-EU?{colon}2C0402"))
    )
    (comp (ref "C45")
      (value "DNP")
      (footprint "eagle-import:C0402")
      (libsource (lib "eagle-import") (part "C-EU?{colon}2C0402"))
    )
    (comp (ref "C46")
      (value "DNP")
      (footprint "eagle-import:C0402")
      (libsource (lib "eagle-import") (part "C-EU?{colon}2C0402"))
    )
    (comp (ref "C47")
      (value "56p")
      (footprint "eagle-import:C0402")
      (libsource (lib "eagle-import") (part "C-EU?{colon}2C0402"))
    )
    (comp (ref "C48")
      (value "100n")
      (footprint "eagle-import:C0402")
      (libsource (lib "eagle-import") (part "C-EU?{colon}2C0402"))
    )
    (comp (ref "IC7")
      (value "SI5351C")
      (footprint "eagle-import:QFN50P400X400X90-21T270N")
      (libsource (lib "eagle-import") (part "SI5351C"))
    )
    (comp (ref "L10")
      (value "Ferrite")
      (footprint "eagle-import:R0402")
      (libsource (lib "eagle-import") (part "FERRITE"))
    )
    (comp (ref "L14")
      (value "330n")
      (footprint "eagle-import:L0402")
      (libsource (lib "eagle-import") (part "INDUCTOR0402"))
    )
    (comp (ref "L18")
      (value "330n")
      (footprint "eagle-import:L0402")
      (libsource (lib "eagle-import") (part "INDUCTOR0402"))
    )
    (comp (ref "R6")
      (value "10k")
      (footprint "eagle-import:R0402")
      (libsource (lib "eagle-import") (part "R-EU_R0402"))
    )
    (comp (ref "R7")
      (value "100")
      (footprint "eagle-import:R0402")
      (libsource (lib "eagle-import") (part "R-EU_R0402"))
    )
    (comp (ref "R8")
      (value "62")
      (footprint "eagle-import:R0402")
      (libsource (lib "eagle-import") (part "R-EU_R0402"))
    )
    (comp (ref "R9")
      (value "100")
      (footprint "eagle-import:R0402")
      (libsource (lib "eagle-import") (part "R-EU_R0402"))
    )
    (comp (ref "R176")
      (value "0")
      (footprint "eagle-import:R0402")
      (libsource (lib "eagle-import") (part "R-EU_R0402"))
    )
    (comp (ref "R177")
      (value "0")
      (footprint "eagle-import:R0402")
      (libsource (lib "eagle-import") (part "R-EU_R0402"))
    )
    (comp (ref "R178")
      (value "0")
      (footprint "eagle-import:R0402")
      (libsource (lib "eagle-import") (part "R-EU_R0402"))
    )
    (comp (ref "R179")
      (value "0")
      (footprint "eagle-import:R0402")
      (libsource (lib "eagle-import") (part "R-EU_R0402"))
    )
    (comp (ref "R180")
      (value "0")
      (footprint "eagle-import:R0402")
      (libsource (lib "eagle-import") (part "R-EU_R0402"))
    )
    (comp (ref "R181")
      (value "0")
      (footprint "eagle-import:R0402")
      (libsource (lib "eagle-import") (part "R-EU_R0402"))
    )
    (comp (ref "X1")
      (value "SMA_CONNECTOR")
      (footprint "eagle-import:J502-ND-142-0711-821_826")
      (libsource (lib "eagle-import") (part "SMA_CONNECTOR"))
    )
    (comp (ref "X2")
      (value "SMA_CONNECTOR")
      (footprint "eagle-import:J502-ND-142-0711-821_826")
      (libsource (lib "eagle-import") (part "SMA_CONNECTOR"))
    )
    (comp (ref "Y1")
      (value "DSB221SDN/26MHz")
      (footprint "eagle-import:2.5X2.0_KXO-86-TCXO")
      (libsource (lib "eagle-import") (part "KXO-TCXO-CMOS-86"))
    )
    (comp (ref "C133")
      (value "100n/RF")
      (footprint "eagle-import:C0402")
      (libsource (lib "eagle-import") (part "C-EU?{colon}2C0402"))
    )
    (comp (ref "C134")
      (value "100n")
      (footprint "eagle-import:C0402")
      (libsource (lib "eagle-import") (part "C-EU?{colon}2C0402"))
    )
    (comp (ref "C135")
      (value "100n")
      (footprint "eagle-import:C0402")
      (libsource (lib "eagle-import") (part "C-EU?{colon}2C0402"))
    )
    (comp (ref "C136")
      (value "100n/RF")
      (footprint "eagle-import:C0402")
      (libsource (lib "eagle-import") (part "C-EU?{colon}2C0402"))
    )
    (comp (ref "C137")
      (value "1u")
      (footprint "eagle-import:C0402")
      (libsource (lib "eagle-import") (part "C-EU?{colon}2C0402"))
    )
    (comp (ref "C138")
      (value "1u")
      (footprint "eagle-import:C0402")
      (libsource (lib "eagle-import") (part "C-EU?{colon}2C0402"))
    )
    (comp (ref "C139")
      (value "100n")
      (footprint "eagle-import:C0402")
      (libsource (lib "eagle-import") (part "C-EU?{colon}2C0402"))
    )
    (comp (ref "C140")
      (value "100n")
      (footprint "eagle-import:C0402")
      (libsource (lib "eagle-import") (part "C-EU?{colon}2C0402"))
    )
    (comp (ref "C141")
      (value "10n")
      (footprint "eagle-import:C0402")
      (libsource (lib "eagle-import") (part "C-EU?{colon}2C0402"))
    )
    (comp (ref "C142")
      (value "10n")
      (footprint "eagle-import:C0402")
      (libsource (lib "eagle-import") (part "C-EU?{colon}2C0402"))
    )
    (comp (ref "C143")
      (value "10n")
      (footprint "eagle-import:C0402")
      (libsource (lib "eagle-import") (part "C-EU?{colon}2C0402"))
    )
    (comp (ref "C144")
      (value "DNP")
      (footprint "eagle-import:C0402")
      (libsource (lib "eagle-import") (part "C-EU?{colon}2C0402"))
    )
    (comp (ref "C145")
      (value "1u")
      (footprint "eagle-import:C0402")
      (libsource (lib "eagle-import") (part "C-EU?{colon}2C0402"))
    )
    (comp (ref "C146")
      (value "100n/RF")
      (footprint "eagle-import:C0402")
      (libsource (lib "eagle-import") (part "C-EU?{colon}2C0402"))
    )
    (comp (ref "C147")
      (value "100n/RF")
      (footprint "eagle-import:C0402")
      (libsource (lib "eagle-import") (part "C-EU?{colon}2C0402"))
    )
    (comp (ref "C148")
      (value "10n")
      (footprint "eagle-import:C0402")
      (libsource (lib "eagle-import") (part "C-EU?{colon}2C0402"))
    )
    (comp (ref "C149")
      (value "DNP")
      (footprint "eagle-import:C0402")
      (libsource (lib "eagle-import") (part "C-EU?{colon}2C0402"))
    )
    (comp (ref "C150")
      (value "DNP")
      (footprint "eagle-import:C0402")
      (libsource (lib "eagle-import") (part "C-EU?{colon}2C0402"))
    )
    (comp (ref "C151")
      (value "100n")
      (footprint "eagle-import:C0402")
      (libsource (lib "eagle-import") (part "C-EU?{colon}2C0402"))
    )
    (comp (ref "C152")
      (value "100n")
      (footprint "eagle-import:C0402")
      (libsource (lib "eagle-import") (part "C-EU?{colon}2C0402"))
    )
    (comp (ref "C153")
      (value "100n")
      (footprint "eagle-import:C0402")
      (libsource (lib "eagle-import") (part "C-EU?{colon}2C0402"))
    )
    (comp (ref "C154")
      (value "100n")
      (footprint "eagle-import:C0402")
      (libsource (lib "eagle-import") (part "C-EU?{colon}2C0402"))
    )
    (comp (ref "C155")
      (value "100n")
      (footprint "eagle-import:C0402")
      (libsource (lib "eagle-import") (part "C-EU?{colon}2C0402"))
    )
    (comp (ref "C156")
      (value "100n")
      (footprint "eagle-import:C0402")
      (libsource (lib "eagle-import") (part "C-EU?{colon}2C0402"))
    )
    (comp (ref "C157")
      (value "10n")
      (footprint "eagle-import:C0402")
      (libsource (lib "eagle-import") (part "C-EU?{colon}2C0402"))
    )
    (comp (ref "C158")
      (value "330p")
      (footprint "eagle-import:C0402")
      (libsource (lib "eagle-import") (part "C-EU?{colon}2C0402"))
    )
    (comp (ref "C159")
      (value "100n")
      (footprint "eagle-import:C0402")
      (libsource (lib "eagle-import") (part "C-EU?{colon}2C0402"))
    )
    (comp (ref "C160")
      (value "10n")
      (footprint "eagle-import:C0402")
      (libsource (lib "eagle-import") (part "C-EU?{colon}2C0402"))
    )
    (comp (ref "C161")
      (value "120p")
      (footprint "eagle-import:C0402")
      (libsource (lib "eagle-import") (part "C-EU?{colon}2C0402"))
    )
    (comp (ref "C162")
      (value "330p")
      (footprint "eagle-import:C0402")
      (libsource (lib "eagle-import") (part "C-EU?{colon}2C0402"))
    )
    (comp (ref "C163")
      (value "330p")
      (footprint "eagle-import:C0402")
      (libsource (lib "eagle-import") (part "C-EU?{colon}2C0402"))
    )
    (comp (ref "C164")
      (value "330p")
      (footprint "eagle-import:C0402")
      (libsource (lib "eagle-import") (part "C-EU?{colon}2C0402"))
    )
    (comp (ref "C165")
      (value "150p")
      (footprint "eagle-import:C0402")
      (libsource (lib "eagle-import") (part "C-EU?{colon}2C0402"))
    )
    (comp (ref "C166")
      (value "1u")
      (footprint "eagle-import:C0402")
      (libsource (lib "eagle-import") (part "C-EU?{colon}2C0402"))
    )
    (comp (ref "C167")
      (value "33p")
      (footprint "eagle-import:C0402")
      (libsource (lib "eagle-import") (part "C-EU?{colon}2C0402"))
    )
    (comp (ref "C168")
      (value "1u")
      (footprint "eagle-import:C0402")
      (libsource (lib "eagle-import") (part "C-EU?{colon}2C0402"))
    )
    (comp (ref "C169")
      (value "100n")
      (footprint "eagle-import:C0402")
      (libsource (lib "eagle-import") (part "C-EU?{colon}2C0402"))
    )
    (comp (ref "IC27")
      (value "LT5560")
      (footprint "eagle-import:SON50P300X300X80-9T165X238")
      (libsource (lib "eagle-import") (part "LT5560"))
    )
    (comp (ref "IC28")
      (value "THS4521IDGKR")
      (footprint "eagle-import:SOP65P490X110-8N")
      (libsource (lib "eagle-import") (part "THS4521IDGKR"))
    )
    (comp (ref "IC29")
      (value "ADL5801")
      (footprint "eagle-import:QFN50P400X400X100-25T250N")
      (libsource (lib "eagle-import") (part "ADL5801"))
    )
    (comp (ref "IC30")
      (value "NCP702-1.8")
      (footprint "eagle-import:SOT95P240X110-5")
      (libsource (lib "eagle-import") (part "NCP702"))
    )
    (comp (ref "IC31")
      (value "MCP33131D-10-E/MS")
      (footprint "eagle-import:SOP50P490X110-10N")
      (libsource (lib "eagle-import") (part "MCP33131D-10-E/MS"))
    )
    (comp (ref "J3")
      (value "BU-1420701851")
      (footprint "eagle-import:BU-1420701851")
      (libsource (lib "eagle-import") (part "BU-1420701851"))
    )
    (comp (ref "L38")
      (value "330n")
      (footprint "eagle-import:L0402")
      (libsource (lib "eagle-import") (part "INDUCTOR0402"))
    )
    (comp (ref "L39")
      (value "330n")
      (footprint "eagle-import:L0402")
      (libsource (lib "eagle-import") (part "INDUCTOR0402"))
    )
    (comp (ref "L40")
      (value "330n")
      (footprint "eagle-import:L0402")
      (libsource (lib "eagle-import") (part "INDUCTOR0402"))
    )
    (comp (ref "L41")
      (value "330n")
      (footprint "eagle-import:L0402")
      (libsource (lib "eagle-import") (part "INDUCTOR0402"))
    )
    (comp (ref "L42")
      (value "68n")
      (footprint "eagle-import:L0402")
      (libsource (lib "eagle-import") (part "INDUCTOR0402"))
    )
    (comp (ref "L43")
      (value "68n")
      (footprint "eagle-import:L0402")
      (libsource (lib "eagle-import") (part "INDUCTOR0402"))
    )
    (comp (ref "L44")
      (value "33n")
      (footprint "eagle-import:L0402")
      (libsource (lib "eagle-import") (part "INDUCTOR0402"))
    )
    (comp (ref "L45")
      (value "33n")
      (footprint "eagle-import:L0402")
      (libsource (lib "eagle-import") (part "INDUCTOR0402"))
    )
    (comp (ref "L54")
      (value "Ferrite")
      (footprint "eagle-import:R0402")
      (libsource (lib "eagle-import") (part "FERRITE"))
    )
    (comp (ref "L55")
      (value "Ferrite")
      (footprint "eagle-import:R0402")
      (libsource (lib "eagle-import") (part "FERRITE"))
    )
    (comp (ref "L56")
      (value "Ferrite")
      (footprint "eagle-import:R0402")
      (libsource (lib "eagle-import") (part "FERRITE"))
    )
    (comp (ref "L57")
      (value "Ferrite")
      (footprint "eagle-import:R0402")
      (libsource (lib "eagle-import") (part "FERRITE"))
    )
    (comp (ref "L58")
      (value "Ferrite")
      (footprint "eagle-import:R0402")
      (libsource (lib "eagle-import") (part "FERRITE"))
    )
    (comp (ref "R40")
      (value "PAT0816-C-3DB-T5")
      (footprint "eagle-import:PAT0816")
      (libsource (lib "eagle-import") (part "PAT0816-C-3DB-T5"))
    )
    (comp (ref "R47")
      (value "PAT0816-C-3DB-T5")
      (footprint "eagle-import:PAT0816")
      (libsource (lib "eagle-import") (part "PAT0816-C-3DB-T5"))
    )
    (comp (ref "R72")
      (value "49R9")
      (footprint "eagle-import:R0402")
      (libsource (lib "eagle-import") (part "R-EU_R0402"))
    )
    (comp (ref "R73")
      (value "49R9")
      (footprint "eagle-import:R0402")
      (libsource (lib "eagle-import") (part "R-EU_R0402"))
    )
    (comp (ref "R76")
      (value "49R9")
      (footprint "eagle-import:R0402")
      (libsource (lib "eagle-import") (part "R-EU_R0402"))
    )
    (comp (ref "R80")
      (value "220")
      (footprint "eagle-import:R0402")
      (libsource (lib "eagle-import") (part "R-EU_R0402"))
    )
    (comp (ref "R81")
      (value "220")
      (footprint "eagle-import:R0402")
      (libsource (lib "eagle-import") (part "R-EU_R0402"))
    )
    (comp (ref "R82")
      (value "6k8")
      (footprint "eagle-import:R0402")
      (libsource (lib "eagle-import") (part "R-EU_R0402"))
    )
    (comp (ref "R83")
      (value "6k8")
      (footprint "eagle-import:R0402")
      (libsource (lib "eagle-import") (part "R-EU_R0402"))
    )
    (comp (ref "R84")
      (value "DNP")
      (footprint "eagle-import:R0402")
      (libsource (lib "eagle-import") (part "R-EU_R0402"))
    )
    (comp (ref "R85")
      (value "220")
      (footprint "eagle-import:R0402")
      (libsource (lib "eagle-import") (part "R-EU_R0402"))
    )
    (comp (ref "R86")
      (value "220")
      (footprint "eagle-import:R0402")
      (libsource (lib "eagle-import") (part "R-EU_R0402"))
    )
    (comp (ref "R87")
      (value "1k")
      (footprint "eagle-import:R0402")
      (libsource (lib "eagle-import") (part "R-EU_R0402"))
    )
    (comp (ref "R88")
      (value "220")
      (footprint "eagle-import:R0402")
      (libsource (lib "eagle-import") (part "R-EU_R0402"))
    )
    (comp (ref "R89")
      (value "220")
      (footprint "eagle-import:R0402")
      (libsource (lib "eagle-import") (part "R-EU_R0402"))
    )
    (comp (ref "R90")
      (value "56")
      (footprint "eagle-import:R0402")
      (libsource (lib "eagle-import") (part "R-EU_R0402"))
    )
    (comp (ref "R91")
      (value "20")
      (footprint "eagle-import:R0402")
      (libsource (lib "eagle-import") (part "R-EU_R0402"))
    )
    (comp (ref "R92")
      (value "20")
      (footprint "eagle-import:R0402")
      (libsource (lib "eagle-import") (part "R-EU_R0402"))
    )
    (comp (ref "R93")
      (value "56")
      (footprint "eagle-import:R0402")
      (libsource (lib "eagle-import") (part "R-EU_R0402"))
    )
    (comp (ref "T2")
      (value "B012-617DB-1-63-B331")
      (footprint "eagle-import:EASTEVER_BALUN")
      (libsource (lib "eagle-import") (part "B012-617DB-1-63-B331"))
    )
    (comp (ref "TP18")
      (value "TPB1,27")
      (footprint "eagle-import:B1,27")
      (libsource (lib "eagle-import") (part "TPB1,27"))
    )
    (comp (ref "C206")
      (value "100n")
      (footprint "eagle-import:C0402")
      (libsource (lib "eagle-import") (part "C-EU?{colon}2C0402"))
    )
    (comp (ref "C207")
      (value "100n")
      (footprint "eagle-import:C0402")
      (libsource (lib "eagle-import") (part "C-EU?{colon}2C0402"))
    )
    (comp (ref "C208")
      (value "100n")
      (footprint "eagle-import:C0402")
      (libsource (lib "eagle-import") (part "C-EU?{colon}2C0402"))
    )
    (comp (ref "C209")
      (value "100n")
      (footprint "eagle-import:C0402")
      (libsource (lib "eagle-import") (part "C-EU?{colon}2C0402"))
    )
    (comp (ref "C210")
      (value "100n")
      (footprint "eagle-import:C0402")
      (libsource (lib "eagle-import") (part "C-EU?{colon}2C0402"))
    )
    (comp (ref "C211")
      (value "100n")
      (footprint "eagle-import:C0402")
      (libsource (lib "eagle-import") (part "C-EU?{colon}2C0402"))
    )
    (comp (ref "C212")
      (value "100n")
      (footprint "eagle-import:C0402")
      (libsource (lib "eagle-import") (part "C-EU?{colon}2C0402"))
    )
    (comp (ref "C213")
      (value "100n")
      (footprint "eagle-import:C0402")
      (libsource (lib "eagle-import") (part "C-EU?{colon}2C0402"))
    )
    (comp (ref "C214")
      (value "100n")
      (footprint "eagle-import:C0402")
      (libsource (lib "eagle-import") (part "C-EU?{colon}2C0402"))
    )
    (comp (ref "C215")
      (value "100n")
      (footprint "eagle-import:C0402")
      (libsource (lib "eagle-import") (part "C-EU?{colon}2C0402"))
    )
    (comp (ref "C216")
      (value "100n")
      (footprint "eagle-import:C0402")
      (libsource (lib "eagle-import") (part "C-EU?{colon}2C0402"))
    )
    (comp (ref "C217")
      (value "100n")
      (footprint "eagle-import:C0402")
      (libsource (lib "eagle-import") (part "C-EU?{colon}2C0402"))
    )
    (comp (ref "C218")
      (value "100n")
      (footprint "eagle-import:C0402")
      (libsource (lib "eagle-import") (part "C-EU?{colon}2C0402"))
    )
    (comp (ref "C219")
      (value "100n")
      (footprint "eagle-import:C0402")
      (libsource (lib "eagle-import") (part "C-EU?{colon}2C0402"))
    )
    (comp (ref "C220")
      (value "100n")
      (footprint "eagle-import:C0402")
      (libsource (lib "eagle-import") (part "C-EU?{colon}2C0402"))
    )
    (comp (ref "C221")
      (value "100n")
      (footprint "eagle-import:C0402")
      (libsource (lib "eagle-import") (part "C-EU?{colon}2C0402"))
    )
    (comp (ref "C222")
      (value "100n")
      (footprint "eagle-import:C0402")
      (libsource (lib "eagle-import") (part "C-EU?{colon}2C0402"))
    )
    (comp (ref "C231")
      (value "100p")
      (footprint "eagle-import:C0402")
      (libsource (lib "eagle-import") (part "C-EU?{colon}2C0402"))
    )
    (comp (ref "C232")
      (value "100p")
      (footprint "eagle-import:C0402")
      (libsource (lib "eagle-import") (part "C-EU?{colon}2C0402"))
    )
    (comp (ref "C233")
      (value "100p")
      (footprint "eagle-import:C0402")
      (libsource (lib "eagle-import") (part "C-EU?{colon}2C0402"))
    )
    (comp (ref "C234")
      (value "100p")
      (footprint "eagle-import:C0402")
      (libsource (lib "eagle-import") (part "C-EU?{colon}2C0402"))
    )
    (comp (ref "IC37")
      (value "STM32G431CB")
      (footprint "eagle-import:QFN50P700X700X60-49T560N")
      (libsource (lib "eagle-import") (part "STM32G431CB"))
    )
    (comp (ref "J4")
      (value "TYPE-C16P(073)")
      (footprint "eagle-import:TYPE-C16P")
      (libsource (lib "eagle-import") (part "TYPE-C16P(073)"))
    )
    (comp (ref "JP1")
      (value "DNP")
      (footprint "eagle-import:1X10_90")
      (libsource (lib "eagle-import") (part "PINHD-1X10/90"))
    )
    (comp (ref "LED1")
      (value "Red")
      (footprint "eagle-import:CHIPLED_0603")
      (libsource (lib "eagle-import") (part "LEDCHIPLED_0603"))
    )
    (comp (ref "R104")
      (value "0")
      (footprint "eagle-import:R0402")
      (libsource (lib "eagle-import") (part "R-EU_R0402"))
    )
    (comp (ref "R105")
      (value "0")
      (footprint "eagle-import:R0402")
      (libsource (lib "eagle-import") (part "R-EU_R0402"))
    )
    (comp (ref "R106")
      (value "0")
      (footprint "eagle-import:R0402")
      (libsource (lib "eagle-import") (part "R-EU_R0402"))
    )
    (comp (ref "R107")
      (value "0")
      (footprint "eagle-import:R0402")
      (libsource (lib "eagle-import") (part "R-EU_R0402"))
    )
    (comp (ref "R108")
      (value "0")
      (footprint "eagle-import:R0402")
      (libsource (lib "eagle-import") (part "R-EU_R0402"))
    )
    (comp (ref "R109")
      (value "0")
      (footprint "eagle-import:R0402")
      (libsource (lib "eagle-import") (part "R-EU_R0402"))
    )
    (comp (ref "R110")
      (value "0")
      (footprint "eagle-import:R0402")
      (libsource (lib "eagle-import") (part "R-EU_R0402"))
    )
    (comp (ref "R111")
      (value "DNP")
      (footprint "eagle-import:R0402")
      (libsource (lib "eagle-import") (part "R-EU_R0402"))
    )
    (comp (ref "R112")
      (value "DNP")
      (footprint "eagle-import:R0402")
      (libsource (lib "eagle-import") (part "R-EU_R0402"))
    )
    (comp (ref "R113")
      (value "DNP")
      (footprint "eagle-import:R0402")
      (libsource (lib "eagle-import") (part "R-EU_R0402"))
    )
    (comp (ref "R114")
      (value "DNP")
      (footprint "eagle-import:R0402")
      (libsource (lib "eagle-import") (part "R-EU_R0402"))
    )
    (comp (ref "R115")
      (value "DNP")
      (footprint "eagle-import:R0402")
      (libsource (lib "eagle-import") (part "R-EU_R0402"))
    )
    (comp (ref "R116")
      (value "10k")
      (footprint "eagle-import:R0402")
      (libsource (lib "eagle-import") (part "R-EU_R0402"))
    )
    (comp (ref "R117")
      (value "10k")
      (footprint "eagle-import:R0402")
      (libsource (lib "eagle-import") (part "R-EU_R0402"))
    )
    (comp (ref "R118")
      (value "20")
      (footprint "eagle-import:R0402")
      (libsource (lib "eagle-import") (part "R-EU_R0402"))
    )
    (comp (ref "R119")
      (value "20")
      (footprint "eagle-import:R0402")
      (libsource (lib "eagle-import") (part "R-EU_R0402"))
    )
    (comp (ref "R120")
      (value "330")
      (footprint "eagle-import:R0402")
      (libsource (lib "eagle-import") (part "R-EU_R0402"))
    )
    (comp (ref "R121")
      (value "10k")
      (footprint "eagle-import:R0402")
      (libsource (lib "eagle-import") (part "R-EU_R0402"))
    )
    (comp (ref "R122")
      (value "10k")
      (footprint "eagle-import:R0402")
      (libsource (lib "eagle-import") (part "R-EU_R0402"))
    )
    (comp (ref "R123")
      (value "20")
      (footprint "eagle-import:R0402")
      (libsource (lib "eagle-import") (part "R-EU_R0402"))
    )
    (comp (ref "R124")
      (value "20")
      (footprint "eagle-import:R0402")
      (libsource (lib "eagle-import") (part "R-EU_R0402"))
    )
    (comp (ref "R126")
      (value "20")
      (footprint "eagle-import:R0402")
      (libsource (lib "eagle-import") (part "R-EU_R0402"))
    )
    (comp (ref "R127")
      (value "10k")
      (footprint "eagle-import:R0402")
      (libsource (lib "eagle-import") (part "R-EU_R0402"))
    )
    (comp (ref "R128")
      (value "10k")
      (footprint "eagle-import:R0402")
      (libsource (lib "eagle-import") (part "R-EU_R0402"))
    )
    (comp (ref "R129")
      (value "10k")
      (footprint "eagle-import:R0402")
      (libsource (lib "eagle-import") (part "R-EU_R0402"))
    )
    (comp (ref "R147")
      (value "10k")
      (footprint "eagle-import:R0402")
      (libsource (lib "eagle-import") (part "R-EU_R0402"))
    )
    (comp (ref "R148")
      (value "10k")
      (footprint "eagle-import:R0402")
      (libsource (lib "eagle-import") (part "R-EU_R0402"))
    )
    (comp (ref "U1")
      (value "W25Q16BVSN")
      (footprint "eagle-import:SO08")
      (libsource (lib "eagle-import") (part "W25Q16BVSN"))
    )
    (comp (ref "C1")
      (value "10u")
      (footprint "eagle-import:C1206")
      (libsource (lib "eagle-import") (part "C-EUC1206"))
    )
    (comp (ref "C2")
      (value "10u")
      (footprint "eagle-import:C1206")
      (libsource (lib "eagle-import") (part "C-EUC1206"))
    )
    (comp (ref "C3")
      (value "10u")
      (footprint "eagle-import:C1206")
      (libsource (lib "eagle-import") (part "C-EUC1206"))
    )
    (comp (ref "C4")
      (value "100n")
      (footprint "eagle-import:C0402")
      (libsource (lib "eagle-import") (part "C-EU?{colon}2C0402"))
    )
    (comp (ref "C5")
      (value "10n")
      (footprint "eagle-import:C0402")
      (libsource (lib "eagle-import") (part "C-EU?{colon}2C0402"))
    )
    (comp (ref "C6")
      (value "100n")
      (footprint "eagle-import:C0402")
      (libsource (lib "eagle-import") (part "C-EU?{colon}2C0402"))
    )
    (comp (ref "C7")
      (value "10u")
      (footprint "eagle-import:C1206")
      (libsource (lib "eagle-import") (part "C-EUC1206"))
    )
    (comp (ref "C8")
      (value "10u")
      (footprint "eagle-import:C1206")
      (libsource (lib "eagle-import") (part "C-EUC1206"))
    )
    (comp (ref "C9")
      (value "100p")
      (footprint "eagle-import:C0402")
      (libsource (lib "eagle-import") (part "C-EU?{colon}2C0402"))
    )
    (comp (ref "C10")
      (value "10u")
      (footprint "eagle-import:C1206")
      (libsource (lib "eagle-import") (part "C-EUC1206"))
    )
    (comp (ref "C11")
      (value "10u")
      (footprint "eagle-import:C1206")
      (libsource (lib "eagle-import") (part "C-EUC1206"))
    )
    (comp (ref "C12")
      (value "10u")
      (footprint "eagle-import:C1206")
      (libsource (lib "eagle-import") (part "C-EUC1206"))
    )
    (comp (ref "C13")
      (value "10u")
      (footprint "eagle-import:C1206")
      (libsource (lib "eagle-import") (part "C-EUC1206"))
    )
    (comp (ref "C14")
      (value "10u")
      (footprint "eagle-import:C1206")
      (libsource (lib "eagle-import") (part "C-EUC1206"))
    )
    (comp (ref "C15")
      (value "10u")
      (footprint "eagle-import:C1206")
      (libsource (lib "eagle-import") (part "C-EUC1206"))
    )
    (comp (ref "C16")
      (value "10u")
      (footprint "eagle-import:C1206")
      (libsource (lib "eagle-import") (part "C-EUC1206"))
    )
    (comp (ref "C17")
      (value "10u")
      (footprint "eagle-import:C1206")
      (libsource (lib "eagle-import") (part "C-EUC1206"))
    )
    (comp (ref "C18")
      (value "1u")
      (footprint "eagle-import:C0603")
      (libsource (lib "eagle-import") (part "C-EU?{colon}1C0603"))
    )
    (comp (ref "C19")
      (value "1u")
      (footprint "eagle-import:C0603")
      (libsource (lib "eagle-import") (part "C-EU?{colon}1C0603"))
    )
    (comp (ref "C20")
      (value "1u")
      (footprint "eagle-import:C0603")
      (libsource (lib "eagle-import") (part "C-EU?{colon}1C0603"))
    )
    (comp (ref "C21")
      (value "1u")
      (footprint "eagle-import:C0603")
      (libsource (lib "eagle-import") (part "C-EU?{colon}1C0603"))
    )
    (comp (ref "C22")
      (value "4u7")
      (footprint "eagle-import:C0603")
      (libsource (lib "eagle-import") (part "C-EU?{colon}1C0603"))
    )
    (comp (ref "C23")
      (value "4u7")
      (footprint "eagle-import:C0603")
      (libsource (lib "eagle-import") (part "C-EU?{colon}1C0603"))
    )
    (comp (ref "C24")
      (value "4u7")
      (footprint "eagle-import:C0603")
      (libsource (lib "eagle-import") (part "C-EU?{colon}1C0603"))
    )
    (comp (ref "C25")
      (value "4u7")
      (footprint "eagle-import:C0603")
      (libsource (lib "eagle-import") (part "C-EU?{colon}1C0603"))
    )
    (comp (ref "C26")
      (value "1u")
      (footprint "eagle-import:C0603")
      (libsource (lib "eagle-import") (part "C-EU?{colon}1C0603"))
    )
    (comp (ref "C27")
      (value "1u")
      (footprint "eagle-import:C0603")
      (libsource (lib "eagle-import") (part "C-EU?{colon}1C0603"))
    )
    (comp (ref "C28")
      (value "1u")
      (footprint "eagle-import:C0603")
      (libsource (lib "eagle-import") (part "C-EU?{colon}1C0603"))
    )
    (comp (ref "D1")
      (value "MBRS2040LT3G")
      (footprint "eagle-import:SMB")
      (libsource (lib "eagle-import") (part "D-SMB"))
    )
    (comp (ref "IC1")
      (value "MIC2253")
      (footprint "eagle-import:SON50P300X300X90-13T170X240N")
      (libsource (lib "eagle-import") (part "MIC2253"))
    )
    (comp (ref "IC2")
      (value "LM3370SD-4221")
      (footprint "eagle-import:SON50P400X500X80-17T260X400N")
      (libsource (lib "eagle-import") (part "LM3370"))
    )
    (comp (ref "IC3")
      (value "LDL212PU50R")
      (footprint "eagle-import:SON95P300X300X100-7T170X240N")
      (libsource (lib "eagle-import") (part "LDL212PU50R"))
    )
    (comp (ref "IC4")
      (value "LDL212PU50R")
      (footprint "eagle-import:SON95P300X300X100-7T170X240N")
      (libsource (lib "eagle-import") (part "LDL212PU50R"))
    )
    (comp (ref "IC5")
      (value "LDL212PU50R")
      (footprint "eagle-import:SON95P300X300X100-7T170X240N")
      (libsource (lib "eagle-import") (part "LDL212PU50R"))
    )
    (comp (ref "IC6")
      (value "LDL212PU50R")
      (footprint "eagle-import:SON95P300X300X100-7T170X240N")
      (libsource (lib "eagle-import") (part "LDL212PU50R"))
    )
    (comp (ref "J1")
      (value "PJ-014D")
      (footprint "eagle-import:PJ-014D")
      (libsource (lib "eagle-import") (part "PJ-014D"))
    )
    (comp (ref "L1")
      (value "2u2")
      (footprint "eagle-import:SRN5040")
      (libsource (lib "eagle-import") (part "SRN5040"))
    )
    (comp (ref "L2")
      (value "2u2")
      (footprint "eagle-import:SRN5040")
      (libsource (lib "eagle-import") (part "SRN5040"))
    )
    (comp (ref "L3")
      (value "2u2")
      (footprint "eagle-import:SRN5040")
      (libsource (lib "eagle-import") (part "SRN5040"))
    )
    (comp (ref "L4")
      (value "2u2")
      (footprint "eagle-import:SRN5040")
      (libsource (lib "eagle-import") (part "SRN5040"))
    )
    (comp (ref "L5")
      (value "2u2")
      (footprint "eagle-import:SRN5040")
      (libsource (lib "eagle-import") (part "SRN5040"))
    )
    (comp (ref "L6")
      (value "Ferrite")
      (footprint "eagle-import:R0402")
      (libsource (lib "eagle-import") (part "FERRITE"))
    )
    (comp (ref "L7")
      (value "Ferrite")
      (footprint "eagle-import:R0402")
      (libsource (lib "eagle-import") (part "FERRITE"))
    )
    (comp (ref "L8")
      (value "Ferrite")
      (footprint "eagle-import:R0402")
      (libsource (lib "eagle-import") (part "FERRITE"))
    )
    (comp (ref "L9")
      (value "Ferrite")
      (footprint "eagle-import:R0402")
      (libsource (lib "eagle-import") (part "FERRITE"))
    )
    (comp (ref "Q1")
      (value "SSM3J338R")
      (footprint "eagle-import:SOTFL95P240X80-3N")
      (libsource (lib "eagle-import") (part "SSM3J338R"))
    )
    (comp (ref "Q2")
      (value "SSM3J338R")
      (footprint "eagle-import:SOTFL95P240X80-3N")
      (libsource (lib "eagle-import") (part "SSM3J338R"))
    )
    (comp (ref "R1")
      (value "620")
      (footprint "eagle-import:R0402")
      (libsource (lib "eagle-import") (part "R-EU_R0402"))
    )
    (comp (ref "R2")
      (value "4k7")
      (footprint "eagle-import:R0402")
      (libsource (lib "eagle-import") (part "R-EU_R0402"))
    )
    (comp (ref "R3")
      (value "10k")
      (footprint "eagle-import:R0402")
      (libsource (lib "eagle-import") (part "R-EU_R0402"))
    )
    (comp (ref "R4")
      (value "38k3")
      (footprint "eagle-import:R0402")
      (libsource (lib "eagle-import") (part "R-EU_R0402"))
    )
    (comp (ref "R5")
      (value "10k")
      (footprint "eagle-import:R0402")
      (libsource (lib "eagle-import") (part "R-EU_R0402"))
    )
    (comp (ref "R125")
      (value "10k")
      (footprint "eagle-import:R0402")
      (libsource (lib "eagle-import") (part "R-EU_R0402"))
    )
    (comp (ref "TP1")
      (value "TPB1,27")
      (footprint "eagle-import:B1,27")
      (libsource (lib "eagle-import") (part "TPB1,27"))
    )
    (comp (ref "TP2")
      (value "TPB1,27")
      (footprint "eagle-import:B1,27")
      (libsource (lib "eagle-import") (part "TPB1,27"))
    )
    (comp (ref "TP3")
      (value "TPB1,27")
      (footprint "eagle-import:B1,27")
      (libsource (lib "eagle-import") (part "TPB1,27"))
    )
    (comp (ref "TP4")
      (value "TPB1,27")
      (footprint "eagle-import:B1,27")
      (libsource (lib "eagle-import") (part "TPB1,27"))
    )
    (comp (ref "TP5")
      (value "TPB1,27")
      (footprint "eagle-import:B1,27")
      (libsource (lib "eagle-import") (part "TPB1,27"))
    )
    (comp (ref "TP6")
      (value "TPB1,27")
      (footprint "eagle-import:B1,27")
      (libsource (lib "eagle-import") (part "TPB1,27"))
    )
    (comp (ref "TP7")
      (value "TPB1,27")
      (footprint "eagle-import:B1,27")
      (libsource (lib "eagle-import") (part "TPB1,27"))
    )
    (comp (ref "TP8")
      (value "TPB1,27")
      (footprint "eagle-import:B1,27")
      (libsource (lib "eagle-import") (part "TPB1,27"))
    )
    (comp (ref "TP9")
      (value "TPB1,27")
      (footprint "eagle-import:B1,27")
      (libsource (lib "eagle-import") (part "TPB1,27"))
    )
    (comp (ref "TP10")
      (value "TPB1,27")
      (footprint "eagle-import:B1,27")
      (libsource (lib "eagle-import") (part "TPB1,27"))
    )
    (comp (ref "TP11")
      (value "TPB1,27")
      (footprint "eagle-import:B1,27")
      (libsource (lib "eagle-import") (part "TPB1,27"))
    )
    (comp (ref "TP12")
      (value "TPB1,27")
      (footprint "eagle-import:B1,27")
      (libsource (lib "eagle-import") (part "TPB1,27"))
    )
  )
  (nets
    (net (code "1") (name "+3V3") (class "Default")
      (node (ref "C132") (pin "2") (pinfunction "2_2") (pintype "passive"))
      (node (ref "C14") (pin "1") (pinfunction "1_1") (pintype "passive"))
      (node (ref "C15") (pin "1") (pinfunction "1_1") (pintype "passive"))
      (node (ref "C169") (pin "2") (pinfunction "2_2") (pintype "passive"))
      (node (ref "C201") (pin "2") (pinfunction "2_2") (pintype "passive"))
      (node (ref "C206") (pin "1") (pinfunction "1_1") (pintype "passive"))
      (node (ref "C207") (pin "1") (pinfunction "1_1") (pintype "passive"))
      (node (ref "C208") (pin "1") (pinfunction "1_1") (pintype "passive"))
      (node (ref "C209") (pin "1") (pinfunction "1_1") (pintype "passive"))
      (node (ref "C210") (pin "1") (pinfunction "1_1") (pintype "passive"))
      (node (ref "C212") (pin "1") (pinfunction "1_1") (pintype "passive"))
      (node (ref "C214") (pin "1") (pinfunction "1_1") (pintype "passive"))
      (node (ref "C216") (pin "1") (pinfunction "1_1") (pintype "passive"))
      (node (ref "C218") (pin "1") (pinfunction "1_1") (pintype "passive"))
      (node (ref "C220") (pin "1") (pinfunction "1_1") (pintype "passive"))
      (node (ref "C221") (pin "1") (pinfunction "1_1") (pintype "passive"))
      (node (ref "C222") (pin "1") (pinfunction "1_1") (pintype "passive"))
      (node (ref "C29") (pin "2") (pinfunction "2_2") (pintype "passive"))
      (node (ref "C31") (pin "2") (pinfunction "2_2") (pintype "passive"))
      (node (ref "IC26") (pin "10") (pinfunction "DVIO_10") (pintype "bidirectional"))
      (node (ref "IC26") (pin "9") (pinfunction "SDI_9") (pintype "bidirectional"))
      (node (ref "IC31") (pin "10") (pinfunction "DVIO_10") (pintype "bidirectional"))
      (node (ref "IC31") (pin "9") (pinfunction "SDI_9") (pintype "bidirectional"))
      (node (ref "IC35") (pin "10") (pinfunction "DVIO_10") (pintype "bidirectional"))
      (node (ref "IC35") (pin "9") (pinfunction "SDI_9") (pintype "bidirectional"))
      (node (ref "IC37") (pin "1") (pinfunction "VBAT_1") (pintype "bidirectional"))
      (node (ref "IC37") (pin "20") (pinfunction "VREF+_20") (pintype "bidirectional"))
      (node (ref "IC37") (pin "21") (pinfunction "VDDA_21") (pintype "bidirectional"))
      (node (ref "IC37") (pin "23") (pinfunction "VDD_23") (pintype "bidirectional"))
      (node (ref "IC37") (pin "35") (pinfunction "VDD_35") (pintype "bidirectional"))
      (node (ref "IC37") (pin "48") (pinfunction "VDD_48") (pintype "bidirectional"))
      (node (ref "IC7") (pin "20") (pinfunction "VDD_20") (pintype "bidirectional"))
      (node (ref "JP1") (pin "5") (pinfunction "5_5") (pintype "passive"))
      (node (ref "JP2") (pin "1") (pinfunction "1_1") (pintype "passive"))
      (node (ref "L10") (pin "1") (pinfunction "1_1") (pintype "passive"))
      (node (ref "L21") (pin "1") (pinfunction "1_1") (pintype "passive"))
      (node (ref "L22") (pin "1") (pinfunction "1_1") (pintype "passive"))
      (node (ref "L23") (pin "1") (pinfunction "1_1") (pintype "passive"))
      (node (ref "L25") (pin "2") (pinfunction "2_2") (pintype "passive"))
      (node (ref "L26") (pin "1") (pinfunction "1_1") (pintype "passive"))
      (node (ref "L27") (pin "1") (pinfunction "1_1") (pintype "passive"))
      (node (ref "L4") (pin "P$2") (pinfunction "2_P$2") (pintype "passive"))
      (node (ref "L64") (pin "2") (pinfunction "2_2") (pintype "passive"))
      (node (ref "L65") (pin "2") (pinfunction "2_2") (pintype "passive"))
      (node (ref "LED1") (pin "A") (pinfunction "A_A") (pintype "passive"))
      (node (ref "LED10") (pin "A") (pinfunction "A_A") (pintype "passive"))
      (node (ref "LED2") (pin "A") (pinfunction "A_A") (pintype "passive"))
      (node (ref "LED3") (pin "A") (pinfunction "A_A") (pintype "passive"))
      (node (ref "LED4") (pin "A") (pinfunction "A_A") (pintype "passive"))
      (node (ref "LED5") (pin "A") (pinfunction "A_A") (pintype "passive"))
      (node (ref "LED6") (pin "A") (pinfunction "A_A") (pintype "passive"))
      (node (ref "LED7") (pin "A") (pinfunction "A_A") (pintype "passive"))
      (node (ref "LED8") (pin "A") (pinfunction "A_A") (pintype "passive"))
      (node (ref "LED9") (pin "A") (pinfunction "A_A") (pintype "passive"))
      (node (ref "R108") (pin "1") (pinfunction "1_1") (pintype "passive"))
      (node (ref "R116") (pin "2") (pinfunction "2_2") (pintype "passive"))
      (node (ref "R117") (pin "2") (pinfunction "2_2") (pintype "passive"))
      (node (ref "R121") (pin "2") (pinfunction "2_2") (pintype "passive"))
      (node (ref "R127") (pin "2") (pinfunction "2_2") (pintype "passive"))
      (node (ref "R128") (pin "2") (pinfunction "2_2") (pintype "passive"))
      (node (ref "R129") (pin "2") (pinfunction "2_2") (pintype "passive"))
      (node (ref "R130") (pin "2") (pinfunction "2_2") (pintype "passive"))
      (node (ref "R132") (pin "2") (pinfunction "2_2") (pintype "passive"))
      (node (ref "TP2") (pin "TP") (pinfunction "TP_TP") (pintype "input"))
      (node (ref "U1") (pin "3") (pinfunction "~{WP}_3") (pintype "input"))
      (node (ref "U1") (pin "7") (pinfunction "~{HOLD}_7") (pintype "input"))
      (node (ref "U1") (pin "8") (pinfunction "VCC_8") (pintype "power_in"))
      (node (ref "U2") (pin "P103") (pinfunction "VCCO_1_P103") (pintype "input"))
      (node (ref "U2") (pin "P122") (pinfunction "VCCO_0_P122") (pintype "input"))
      (node (ref "U2") (pin "P125") (pinfunction "VCCO_0_P125") (pintype "input"))
      (node (ref "U2") (pin "P129") (pinfunction "VCCAUX_P129") (pintype "input"))
      (node (ref "U2") (pin "P135") (pinfunction "VCCO_0_P135") (pintype "input"))
      (node (ref "U2") (pin "P18") (pinfunction "VCCO_3_P18") (pintype "input"))
      (node (ref "U2") (pin "P20") (pinfunction "VCCAUX_P20") (pintype "input"))
      (node (ref "U2") (pin "P31") (pinfunction "VCCO_3_P31") (pintype "input"))
      (node (ref "U2") (pin "P36") (pinfunction "VCCAUX_P36") (pintype "input"))
      (node (ref "U2") (pin "P4") (pinfunction "VCCO_3_P4") (pintype "input"))
      (node (ref "U2") (pin "P42") (pinfunction "VCCO_2_P42") (pintype "input"))
      (node (ref "U2") (pin "P53") (pinfunction "VCCAUX_P53") (pintype "input"))
      (node (ref "U2") (pin "P63") (pinfunction "VCCO_2_P63") (pintype "input"))
      (node (ref "U2") (pin "P69") (pinfunction "IO_L1N_M0_CMPMISO_2_P69") (pintype "bidirectional"))
      (node (ref "U2") (pin "P76") (pinfunction "VCCO_1_P76") (pintype "input"))
      (node (ref "U2") (pin "P86") (pinfunction "VCCO_1_P86") (pintype "input"))
      (node (ref "U2") (pin "P90") (pinfunction "VCCAUX_P90") (pintype "input"))
      (node (ref "Y1") (pin "4") (pinfunction "VDD_4") (pintype "power_in"))
    )
    (net (code "2") (name "+5V") (class "Default")
      (node (ref "C1") (pin "1") (pinfunction "1_1") (pintype "passive"))
      (node (ref "C2") (pin "1") (pinfunction "1_1") (pintype "passive"))
      (node (ref "C3") (pin "1") (pinfunction "1_1") (pintype "passive"))
      (node (ref "C6") (pin "2") (pinfunction "2_2") (pintype "passive"))
      (node (ref "IC1") (pin "10") (pinfunction "VIN_10") (pintype "bidirectional"))
      (node (ref "IC2") (pin "1") (pinfunction "VIN_1") (pintype "bidirectional"))
      (node (ref "IC2") (pin "14") (pinfunction "EN_14") (pintype "bidirectional"))
      (node (ref "IC2") (pin "15") (pinfunction "EN_15") (pintype "bidirectional"))
      (node (ref "IC2") (pin "4") (pinfunction "VDD_4") (pintype "bidirectional"))
      (node (ref "IC2") (pin "8") (pinfunction "VIN_8") (pintype "bidirectional"))
      (node (ref "J1") (pin "1") (pinfunction "1_1") (pintype "passive"))
      (node (ref "L1") (pin "P$1") (pinfunction "1_P$1") (pintype "passive"))
      (node (ref "Q2") (pin "3") (pinfunction "D_3") (pintype "passive"))
    )
    (net (code "3") (name "+5V{slash}1") (class "Default")
      (node (ref "C26") (pin "2") (pinfunction "2_2") (pintype "passive"))
      (node (ref "L12") (pin "2") (pinfunction "2_2") (pintype "passive"))
      (node (ref "L13") (pin "2") (pinfunction "2_2") (pintype "passive"))
      (node (ref "L15") (pin "2") (pinfunction "2_2") (pintype "passive"))
      (node (ref "L16") (pin "2") (pinfunction "2_2") (pintype "passive"))
      (node (ref "L17") (pin "2") (pinfunction "2_2") (pintype "passive"))
      (node (ref "L6") (pin "2") (pinfunction "2_2") (pintype "passive"))
      (node (ref "R60") (pin "1") (pinfunction "1_1") (pintype "passive"))
      (node (ref "TP5") (pin "TP") (pinfunction "TP_TP") (pintype "input"))
    )
    (net (code "4") (name "+5V{slash}2") (class "Default")
      (node (ref "C27") (pin "2") (pinfunction "2_2") (pintype "passive"))
      (node (ref "L54") (pin "2") (pinfunction "2_2") (pintype "passive"))
      (node (ref "L55") (pin "2") (pinfunction "2_2") (pintype "passive"))
      (node (ref "L56") (pin "2") (pinfunction "2_2") (pintype "passive"))
      (node (ref "L57") (pin "2") (pinfunction "2_2") (pintype "passive"))
      (node (ref "L58") (pin "2") (pinfunction "2_2") (pintype "passive"))
      (node (ref "L7") (pin "2") (pinfunction "2_2") (pintype "passive"))
      (node (ref "R87") (pin "1") (pinfunction "1_1") (pintype "passive"))
      (node (ref "TP7") (pin "TP") (pinfunction "TP_TP") (pintype "input"))
    )
    (net (code "5") (name "+5V{slash}3") (class "Default")
      (node (ref "C28") (pin "2") (pinfunction "2_2") (pintype "passive"))
      (node (ref "L59") (pin "2") (pinfunction "2_2") (pintype "passive"))
      (node (ref "L60") (pin "2") (pinfunction "2_2") (pintype "passive"))
      (node (ref "L61") (pin "2") (pinfunction "2_2") (pintype "passive"))
      (node (ref "L62") (pin "2") (pinfunction "2_2") (pintype "passive"))
      (node (ref "L63") (pin "1") (pinfunction "1_1") (pintype "passive"))
      (node (ref "L8") (pin "2") (pinfunction "2_2") (pintype "passive"))
      (node (ref "R101") (pin "1") (pinfunction "1_1") (pintype "passive"))
      (node (ref "TP9") (pin "TP") (pinfunction "TP_TP") (pintype "input"))
    )
    (net (code "6") (name "+5V{slash}4") (class "Default")
      (node (ref "C49") (pin "1") (pinfunction "1_1") (pintype "passive"))
      (node (ref "C50") (pin "1") (pinfunction "1_1") (pintype "passive"))
      (node (ref "C78") (pin "1") (pinfunction "1_1") (pintype "passive"))
      (node (ref "C79") (pin "1") (pinfunction "1_1") (pintype "passive"))
      (node (ref "IC19") (pin "3") (pinfunction "VIN_3") (pintype "power_in"))
      (node (ref "IC20") (pin "1") (pinfunction "VIN_1") (pintype "power_in"))
      (node (ref "IC20") (pin "3") (pinfunction "EN_3") (pintype "input"))
      (node (ref "IC8") (pin "3") (pinfunction "VIN_3") (pintype "power_in"))
      (node (ref "IC9") (pin "1") (pinfunction "VIN_1") (pintype "power_in"))
      (node (ref "IC9") (pin "3") (pinfunction "EN_3") (pintype "input"))
      (node (ref "L9") (pin "2") (pinfunction "2_2") (pintype "passive"))
      (node (ref "TP11") (pin "TP") (pinfunction "TP_TP") (pintype "input"))
    )
    (net (code "7") (name "AMP_PWDN") (class "Default")
      (node (ref "C243") (pin "1") (pinfunction "1_1") (pintype "passive"))
      (node (ref "R153") (pin "2") (pinfunction "2_2") (pintype "passive"))
      (node (ref "U2") (pin "P8") (pinfunction "IO_L51P_3_P8") (pintype "bidirectional"))
    )
    (net (code "8") (name "ATT_D0") (class "Default")
      (node (ref "C249") (pin "1") (pinfunction "1_1") (pintype "passive"))
      (node (ref "R156") (pin "2") (pinfunction "2_2") (pintype "passive"))
      (node (ref "U2") (pin "P16") (pinfunction "IO_L43N_GCLK22_IRDY2_3_P16") (pintype "bidirectional"))
    )
    (net (code "9") (name "ATT_D1") (class "Default")
      (node (ref "C251") (pin "1") (pinfunction "1_1") (pintype "passive"))
      (node (ref "R157") (pin "2") (pinfunction "2_2") (pintype "passive"))
      (node (ref "U2") (pin "P15") (pinfunction "IO_L44P_GCLK21_3_P15") (pintype "bidirectional"))
    )
    (net (code "10") (name "ATT_D2") (class "Default")
      (node (ref "C253") (pin "1") (pinfunction "1_1") (pintype "passive"))
      (node (ref "R158") (pin "2") (pinfunction "2_2") (pintype "passive"))
      (node (ref "U2") (pin "P14") (pinfunction "IO_L44N_GCLK20_3_P14") (pintype "bidirectional"))
    )
    (net (code "11") (name "ATT_D3") (class "Default")
      (node (ref "C255") (pin "1") (pinfunction "1_1") (pintype "passive"))
      (node (ref "R159") (pin "2") (pinfunction "2_2") (pintype "passive"))
      (node (ref "U2") (pin "P12") (pinfunction "IO_L49P_3_P12") (pintype "bidirectional"))
    )
    (net (code "12") (name "ATT_D4") (class "Default")
      (node (ref "C262") (pin "1") (pinfunction "1_1") (pintype "passive"))
      (node (ref "R162") (pin "1") (pinfunction "1_1") (pintype "passive"))
      (node (ref "U2") (pin "P11") (pinfunction "IO_L49N_3_P11") (pintype "bidirectional"))
    )
    (net (code "13") (name "ATT_D5") (class "Default")
      (node (ref "C260") (pin "1") (pinfunction "1_1") (pintype "passive"))
      (node (ref "R161") (pin "1") (pinfunction "1_1") (pintype "passive"))
      (node (ref "U2") (pin "P10") (pinfunction "IO_L50P_3_P10") (pintype "bidirectional"))
    )
    (net (code "14") (name "ATT_D6") (class "Default")
      (node (ref "C258") (pin "1") (pinfunction "1_1") (pintype "passive"))
      (node (ref "R160") (pin "1") (pinfunction "1_1") (pintype "passive"))
      (node (ref "U2") (pin "P9") (pinfunction "IO_L50N_3_P9") (pintype "bidirectional"))
    )
    (net (code "15") (name "EN_6V") (class "Default")
      (node (ref "IC1") (pin "11") (pinfunction "EN_11") (pintype "bidirectional"))
      (node (ref "IC37") (pin "25") (pinfunction "PB12_25") (pintype "bidirectional"))
    )
    (net (code "16") (name "FILT_IN_C1") (class "Default")
      (node (ref "C263") (pin "1") (pinfunction "1_1") (pintype "passive"))
      (node (ref "R21") (pin "2") (pinfunction "2_2") (pintype "passive"))
      (node (ref "U2") (pin "P26") (pinfunction "IO_L37N_3_P26") (pintype "bidirectional"))
    )
    (net (code "17") (name "FILT_IN_C2") (class "Default")
      (node (ref "C264") (pin "1") (pinfunction "1_1") (pintype "passive"))
      (node (ref "R20") (pin "2") (pinfunction "2_2") (pintype "passive"))
      (node (ref "U2") (pin "P24") (pinfunction "IO_L41P_GCLK27_3_P24") (pintype "bidirectional"))
    )
    (net (code "18") (name "FILT_OUT_C1") (class "Default")
      (node (ref "C266") (pin "1") (pinfunction "1_1") (pintype "passive"))
      (node (ref "R24") (pin "2") (pinfunction "2_2") (pintype "passive"))
      (node (ref "U2") (pin "P22") (pinfunction "IO_L42P_GCLK25_TRDY2_3_P22") (pintype "bidirectional"))
    )
    (net (code "19") (name "FILT_OUT_C2") (class "Default")
      (node (ref "C265") (pin "1") (pinfunction "1_1") (pintype "passive"))
      (node (ref "R22") (pin "2") (pinfunction "2_2") (pintype "passive"))
      (node (ref "U2") (pin "P23") (pinfunction "IO_L41N_GCLK26_3_P23") (pintype "bidirectional"))
    )
    (net (code "20") (name "FPGA_CCLK") (class "Default")
      (node (ref "R109") (pin "2") (pinfunction "2_2") (pintype "passive"))
      (node (ref "R111") (pin "2") (pinfunction "2_2") (pintype "passive"))
      (node (ref "U2") (pin "P70") (pinfunction "IO_L1P_CCLK_2_P70") (pintype "bidirectional"))
    )
    (net (code "21") (name "FPGA_CLK") (class "Default")
      (node (ref "IC7") (pin "15") (pinfunction "CLK7_15") (pintype "bidirectional"))
      (node (ref "R126") (pin "1") (pinfunction "1_1") (pintype "passive"))
    )
    (net (code "22") (name "FPGA_CSO_B") (class "Default")
      (node (ref "R114") (pin "2") (pinfunction "2_2") (pintype "passive"))
      (node (ref "U2") (pin "P38") (pinfunction "IO_L65N_CSO_B_2_P38") (pintype "bidirectional"))
    )
    (net (code "23") (name "FPGA_DIN") (class "Default")
      (node (ref "R110") (pin "2") (pinfunction "2_2") (pintype "passive"))
      (node (ref "R113") (pin "2") (pinfunction "2_2") (pintype "passive"))
      (node (ref "U2") (pin "P65") (pinfunction "IO_L3P_D0_DIN_MISO_MISO1_2_P65") (pintype "bidirectional"))
    )
    (net (code "24") (name "FPGA_DONE") (class "Default")
      (node (ref "IC37") (pin "47") (pinfunction "PB9_47") (pintype "bidirectional"))
      (node (ref "R129") (pin "1") (pinfunction "1_1") (pintype "passive"))
      (node (ref "U2") (pin "P71") (pinfunction "DONE_2_P71") (pintype "bidirectional"))
    )
    (net (code "25") (name "FPGA_INIT_B") (class "Default")
      (node (ref "IC37") (pin "6") (pinfunction "PF1-OSC_OUT_6") (pintype "bidirectional"))
      (node (ref "R128") (pin "1") (pinfunction "1_1") (pintype "passive"))
      (node (ref "U2") (pin "P39") (pinfunction "IO_L65P_INIT_B_2_P39") (pintype "bidirectional"))
    )
    (net (code "26") (name "FPGA_M1") (class "Default")
      (node (ref "R108") (pin "2") (pinfunction "2_2") (pintype "passive"))
      (node (ref "R115") (pin "1") (pinfunction "1_1") (pintype "passive"))
      (node (ref "U2") (pin "P60") (pinfunction "IO_L13P_M1_2_P60") (pintype "bidirectional"))
    )
    (net (code "27") (name "FPGA_MOSI") (class "Default")
      (node (ref "R112") (pin "2") (pinfunction "2_2") (pintype "passive"))
      (node (ref "U2") (pin "P64") (pinfunction "IO_L3N_MOSI_CSI_B_MISO0_2_P64") (pintype "bidirectional"))
    )
    (net (code "28") (name "FPGA_PROGRAM_B") (class "Default")
      (node (ref "IC37") (pin "19") (pinfunction "PB2_19") (pintype "bidirectional"))
      (node (ref "R127") (pin "1") (pinfunction "1_1") (pintype "passive"))
      (node (ref "U2") (pin "P37") (pinfunction "PROGRAM_B_2_P37") (pintype "input"))
    )
    (net (code "29") (name "FPGA_RESET") (class "Default")
      (node (ref "IC37") (pin "45") (pinfunction "PB7_45") (pintype "bidirectional"))
      (node (ref "U2") (pin "P72") (pinfunction "CMPCS_B_2_P72") (pintype "bidirectional"))
    )
    (net (code "30") (name "GND") (class "Default")
      (node (ref "C1") (pin "2") (pinfunction "2_2") (pintype "passive"))
      (node (ref "C10") (pin "2") (pinfunction "2_2") (pintype "passive"))
      (node (ref "C102") (pin "1") (pinfunction "1_1") (pintype "passive"))
      (node (ref "C103") (pin "1") (pinfunction "1_1") (pintype "passive"))
      (node (ref "C104") (pin "2") (pinfunction "2_2") (pintype "passive"))
      (node (ref "C105") (pin "2") (pinfunction "2_2") (pintype "passive"))
      (node (ref "C106") (pin "2") (pinfunction "2_2") (pintype "passive"))
      (node (ref "C108") (pin "2") (pinfunction "2_2") (pintype "passive"))
      (node (ref "C11") (pin "2") (pinfunction "2_2") (pintype "passive"))
      (node (ref "C111") (pin "2") (pinfunction "2_2") (pintype "passive"))
      (node (ref "C115") (pin "1") (pinfunction "1_1") (pintype "passive"))
      (node (ref "C116") (pin "2") (pinfunction "2_2") (pintype "passive"))
      (node (ref "C117") (pin "2") (pinfunction "2_2") (pintype "passive"))
      (node (ref "C118") (pin "1") (pinfunction "1_1") (pintype "passive"))
      (node (ref "C119") (pin "2") (pinfunction "2_2") (pintype "passive"))
      (node (ref "C12") (pin "2") (pinfunction "2_2") (pintype "passive"))
      (node (ref "C122") (pin "2") (pinfunction "2_2") (pintype "passive"))
      (node (ref "C125") (pin "1") (pinfunction "1_1") (pintype "passive"))
      (node (ref "C127") (pin "2") (pinfunction "2_2") (pintype "passive"))
      (node (ref "C129") (pin "2") (pinfunction "2_2") (pintype "passive"))
      (node (ref "C13") (pin "2") (pinfunction "2_2") (pintype "passive"))
      (node (ref "C131") (pin "2") (pinfunction "2_2") (pintype "passive"))
      (node (ref "C132") (pin "1") (pinfunction "1_1") (pintype "passive"))
      (node (ref "C134") (pin "1") (pinfunction "1_1") (pintype "passive"))
      (node (ref "C139") (pin "1") (pinfunction "1_1") (pintype "passive"))
      (node (ref "C14") (pin "2") (pinfunction "2_2") (pintype "passive"))
      (node (ref "C140") (pin "1") (pinfunction "1_1") (pintype "passive"))
      (node (ref "C141") (pin "2") (pinfunction "2_2") (pintype "passive"))
      (node (ref "C142") (pin "2") (pinfunction "2_2") (pintype "passive"))
      (node (ref "C143") (pin "2") (pinfunction "2_2") (pintype "passive"))
      (node (ref "C145") (pin "2") (pinfunction "2_2") (pintype "passive"))
      (node (ref "C148") (pin "2") (pinfunction "2_2") (pintype "passive"))
      (node (ref "C15") (pin "2") (pinfunction "2_2") (pintype "passive"))
      (node (ref "C152") (pin "1") (pinfunction "1_1") (pintype "passive"))
      (node (ref "C153") (pin "2") (pinfunction "2_2") (pintype "passive"))
      (node (ref "C154") (pin "2") (pinfunction "2_2") (pintype "passive"))
      (node (ref "C155") (pin "1") (pinfunction "1_1") (pintype "passive"))
      (node (ref "C156") (pin "2") (pinfunction "2_2") (pintype "passive"))
      (node (ref "C159") (pin "2") (pinfunction "2_2") (pintype "passive"))
      (node (ref "C16") (pin "2") (pinfunction "2_2") (pintype "passive"))
      (node (ref "C162") (pin "1") (pinfunction "1_1") (pintype "passive"))
      (node (ref "C164") (pin "2") (pinfunction "2_2") (pintype "passive"))
      (node (ref "C166") (pin "2") (pinfunction "2_2") (pintype "passive"))
      (node (ref "C168") (pin "2") (pinfunction "2_2") (pintype "passive"))
      (node (ref "C169") (pin "1") (pinfunction "1_1") (pintype "passive"))
      (node (ref "C17") (pin "2") (pinfunction "2_2") (pintype "passive"))
      (node (ref "C171") (pin "2") (pinfunction "2_2") (pintype "passive"))
      (node (ref "C172") (pin "2") (pinfunction "2_2") (pintype "passive"))
      (node (ref "C175") (pin "2") (pinfunction "2_2") (pintype "passive"))
      (node (ref "C177") (pin "2") (pinfunction "2_2") (pintype "passive"))
      (node (ref "C18") (pin "1") (pinfunction "1_1") (pintype "passive"))
      (node (ref "C180") (pin "2") (pinfunction "2_2") (pintype "passive"))
      (node (ref "C181") (pin "1") (pinfunction "1_1") (pintype "passive"))
      (node (ref "C182") (pin "2") (pinfunction "2_2") (pintype "passive"))
      (node (ref "C185") (pin "2") (pinfunction "2_2") (pintype "passive"))
      (node (ref "C186") (pin "1") (pinfunction "1_1") (pintype "passive"))
      (node (ref "C187") (pin "1") (pinfunction "1_1") (pintype "passive"))
      (node (ref "C189") (pin "2") (pinfunction "2_2") (pintype "passive"))
      (node (ref "C19") (pin "1") (pinfunction "1_1") (pintype "passive"))
      (node (ref "C190") (pin "2") (pinfunction "2_2") (pintype "passive"))
      (node (ref "C193") (pin "2") (pinfunction "2_2") (pintype "passive"))
      (node (ref "C195") (pin "2") (pinfunction "2_2") (pintype "passive"))
      (node (ref "C198") (pin "2") (pinfunction "2_2") (pintype "passive"))
      (node (ref "C199") (pin "1") (pinfunction "1_1") (pintype "passive"))
      (node (ref "C2") (pin "2") (pinfunction "2_2") (pintype "passive"))
      (node (ref "C20") (pin "1") (pinfunction "1_1") (pintype "passive"))
      (node (ref "C201") (pin "1") (pinfunction "1_1") (pintype "passive"))
      (node (ref "C204") (pin "1") (pinfunction "1_1") (pintype "passive"))
      (node (ref "C205") (pin "1") (pinfunction "1_1") (pintype "passive"))
      (node (ref "C206") (pin "2") (pinfunction "2_2") (pintype "passive"))
      (node (ref "C207") (pin "2") (pinfunction "2_2") (pintype "passive"))
      (node (ref "C208") (pin "2") (pinfunction "2_2") (pintype "passive"))
      (node (ref "C209") (pin "2") (pinfunction "2_2") (pintype "passive"))
      (node (ref "C21") (pin "1") (pinfunction "1_1") (pintype "passive"))
      (node (ref "C210") (pin "2") (pinfunction "2_2") (pintype "passive"))
      (node (ref "C211") (pin "2") (pinfunction "2_2") (pintype "passive"))
      (node (ref "C212") (pin "2") (pinfunction "2_2") (pintype "passive"))
      (node (ref "C213") (pin "2") (pinfunction "2_2") (pintype "passive"))
      (node (ref "C214") (pin "2") (pinfunction "2_2") (pintype "passive"))
      (node (ref "C215") (pin "2") (pinfunction "2_2") (pintype "passive"))
      (node (ref "C216") (pin "2") (pinfunction "2_2") (pintype "passive"))
      (node (ref "C217") (pin "2") (pinfunction "2_2") (pintype "passive"))
      (node (ref "C218") (pin "2") (pinfunction "2_2") (pintype "passive"))
      (node (ref "C219") (pin "2") (pinfunction "2_2") (pintype "passive"))
      (node (ref "C22") (pin "1") (pinfunction "1_1") (pintype "passive"))
      (node (ref "C220") (pin "2") (pinfunction "2_2") (pintype "passive"))
      (node (ref "C221") (pin "2") (pinfunction "2_2") (pintype "passive"))
      (node (ref "C222") (pin "2") (pinfunction "2_2") (pintype "passive"))
      (node (ref "C223") (pin "2") (pinfunction "2_2") (pintype "passive"))
      (node (ref "C224") (pin "2") (pinfunction "2_2") (pintype "passive"))
      (node (ref "C225") (pin "2") (pinfunction "2_2") (pintype "passive"))
      (node (ref "C226") (pin "2") (pinfunction "2_2") (pintype "passive"))
      (node (ref "C227") (pin "2") (pinfunction "2_2") (pintype "passive"))
      (node (ref "C228") (pin "2") (pinfunction "2_2") (pintype "passive"))
      (node (ref "C229") (pin "2") (pinfunction "2_2") (pintype "passive"))
      (node (ref "C23") (pin "1") (pinfunction "1_1") (pintype "passive"))
      (node (ref "C230") (pin "2") (pinfunction "2_2") (pintype "passive"))
      (node (ref "C231") (pin "2") (pinfunction "2_2") (pintype "passive"))
      (node (ref "C232") (pin "2") (pinfunction "2_2") (pintype "passive"))
      (node (ref "C233") (pin "2") (pinfunction "2_2") (pintype "passive"))
      (node (ref "C234") (pin "2") (pinfunction "2_2") (pintype "passive"))
      (node (ref "C235") (pin "2") (pinfunction "2_2") (pintype "passive"))
      (node (ref "C236") (pin "2") (pinfunction "2_2") (pintype "passive"))
      (node (ref "C237") (pin "2") (pinfunction "2_2") (pintype "passive"))
      (node (ref "C238") (pin "2") (pinfunction "2_2") (pintype "passive"))
      (node (ref "C239") (pin "2") (pinfunction "2_2") (pintype "passive"))
      (node (ref "C24") (pin "1") (pinfunction "1_1") (pintype "passive"))
      (node (ref "C240") (pin "2") (pinfunction "2_2") (pintype "passive"))
      (node (ref "C241") (pin "2") (pinfunction "2_2") (pintype "passive"))
      (node (ref "C242") (pin "2") (pinfunction "2_2") (pintype "passive"))
      (node (ref "C243") (pin "2") (pinfunction "2_2") (pintype "passive"))
      (node (ref "C244") (pin "2") (pinfunction "2_2") (pintype "passive"))
      (node (ref "C245") (pin "2") (pinfunction "2_2") (pintype "passive"))
      (node (ref "C246") (pin "2") (pinfunction "2_2") (pintype "passive"))
      (node (ref "C247") (pin "2") (pinfunction "2_2") (pintype "passive"))
      (node (ref "C248") (pin "2") (pinfunction "2_2") (pintype "passive"))
      (node (ref "C249") (pin "2") (pinfunction "2_2") (pintype "passive"))
      (node (ref "C25") (pin "1") (pinfunction "1_1") (pintype "passive"))
      (node (ref "C250") (pin "2") (pinfunction "2_2") (pintype "passive"))
      (node (ref "C251") (pin "2") (pinfunction "2_2") (pintype "passive"))
      (node (ref "C252") (pin "2") (pinfunction "2_2") (pintype "passive"))
      (node (ref "C253") (pin "2") (pinfunction "2_2") (pintype "passive"))
      (node (ref "C254") (pin "2") (pinfunction "2_2") (pintype "passive"))
      (node (ref "C255") (pin "2") (pinfunction "2_2") (pintype "passive"))
      (node (ref "C256") (pin "2") (pinfunction "2_2") (pintype "passive"))
      (node (ref "C257") (pin "2") (pinfunction "2_2") (pintype "passive"))
      (node (ref "C258") (pin "2") (pinfunction "2_2") (pintype "passive"))
      (node (ref "C259") (pin "2") (pinfunction "2_2") (pintype "passive"))
      (node (ref "C26") (pin "1") (pinfunction "1_1") (pintype "passive"))
      (node (ref "C260") (pin "2") (pinfunction "2_2") (pintype "passive"))
      (node (ref "C261") (pin "2") (pinfunction "2_2") (pintype "passive"))
      (node (ref "C262") (pin "2") (pinfunction "2_2") (pintype "passive"))
      (node (ref "C263") (pin "2") (pinfunction "2_2") (pintype "passive"))
      (node (ref "C264") (pin "2") (pinfunction "2_2") (pintype "passive"))
      (node (ref "C265") (pin "2") (pinfunction "2_2") (pintype "passive"))
      (node (ref "C266") (pin "2") (pinfunction "2_2") (pintype "passive"))
      (node (ref "C267") (pin "2") (pinfunction "2_2") (pintype "passive"))
      (node (ref "C268") (pin "2") (pinfunction "2_2") (pintype "passive"))
      (node (ref "C27") (pin "1") (pinfunction "1_1") (pintype "passive"))
      (node (ref "C271") (pin "2") (pinfunction "2_2") (pintype "passive"))
      (node (ref "C272") (pin "2") (pinfunction "2_2") (pintype "passive"))
      (node (ref "C273") (pin "2") (pinfunction "2_2") (pintype "passive"))
      (node (ref "C274") (pin "2") (pinfunction "2_2") (pintype "passive"))
      (node (ref "C28") (pin "1") (pinfunction "1_1") (pintype "passive"))
      (node (ref "C29") (pin "1") (pinfunction "1_1") (pintype "passive"))
      (node (ref "C3") (pin "2") (pinfunction "2_2") (pintype "passive"))
      (node (ref "C31") (pin "1") (pinfunction "1_1") (pintype "passive"))
      (node (ref "C32") (pin "1") (pinfunction "1_1") (pintype "passive"))
      (node (ref "C33") (pin "1") (pinfunction "1_1") (pintype "passive"))
      (node (ref "C35") (pin "2") (pinfunction "2_2") (pintype "passive"))
      (node (ref "C36") (pin "2") (pinfunction "2_2") (pintype "passive"))
      (node (ref "C37") (pin "2") (pinfunction "2_2") (pintype "passive"))
      (node (ref "C38") (pin "2") (pinfunction "2_2") (pintype "passive"))
      (node (ref "C4") (pin "1") (pinfunction "1_1") (pintype "passive"))
      (node (ref "C40") (pin "2") (pinfunction "2_2") (pintype "passive"))
      (node (ref "C41") (pin "2") (pinfunction "2_2") (pintype "passive"))
      (node (ref "C42") (pin "2") (pinfunction "2_2") (pintype "passive"))
      (node (ref "C43") (pin "2") (pinfunction "2_2") (pintype "passive"))
      (node (ref "C44") (pin "2") (pinfunction "2_2") (pintype "passive"))
      (node (ref "C45") (pin "2") (pinfunction "2_2") (pintype "passive"))
      (node (ref "C46") (pin "2") (pinfunction "2_2") (pintype "passive"))
      (node (ref "C47") (pin "2") (pinfunction "2_2") (pintype "passive"))
      (node (ref "C49") (pin "2") (pinfunction "2_2") (pintype "passive"))
      (node (ref "C5") (pin "1") (pinfunction "1_1") (pintype "passive"))
      (node (ref "C50") (pin "2") (pinfunction "2_2") (pintype "passive"))
      (node (ref "C52") (pin "2") (pinfunction "2_2") (pintype "passive"))
      (node (ref "C53") (pin "2") (pinfunction "2_2") (pintype "passive"))
      (node (ref "C54") (pin "2") (pinfunction "2_2") (pintype "passive"))
      (node (ref "C55") (pin "2") (pinfunction "2_2") (pintype "passive"))
      (node (ref "C56") (pin "2") (pinfunction "2_2") (pintype "passive"))
      (node (ref "C57") (pin "2") (pinfunction "2_2") (pintype "passive"))
      (node (ref "C58") (pin "2") (pinfunction "2_2") (pintype "passive"))
      (node (ref "C59") (pin "2") (pinfunction "2_2") (pintype "passive"))
      (node (ref "C6") (pin "1") (pinfunction "1_1") (pintype "passive"))
      (node (ref "C60") (pin "2") (pinfunction "2_2") (pintype "passive"))
      (node (ref "C61") (pin "2") (pinfunction "2_2") (pintype "passive"))
      (node (ref "C63") (pin "2") (pinfunction "2_2") (pintype "passive"))
      (node (ref "C64") (pin "2") (pinfunction "2_2") (pintype "passive"))
      (node (ref "C67") (pin "1") (pinfunction "1_1") (pintype "passive"))
      (node (ref "C69") (pin "2") (pinfunction "2_2") (pintype "passive"))
      (node (ref "C7") (pin "2") (pinfunction "2_2") (pintype "passive"))
      (node (ref "C70") (pin "2") (pinfunction "2_2") (pintype "passive"))
      (node (ref "C72") (pin "2") (pinfunction "2_2") (pintype "passive"))
      (node (ref "C73") (pin "2") (pinfunction "2_2") (pintype "passive"))
      (node (ref "C75") (pin "2") (pinfunction "2_2") (pintype "passive"))
      (node (ref "C76") (pin "2") (pinfunction "2_2") (pintype "passive"))
      (node (ref "C77") (pin "2") (pinfunction "2_2") (pintype "passive"))
      (node (ref "C78") (pin "2") (pinfunction "2_2") (pintype "passive"))
      (node (ref "C79") (pin "2") (pinfunction "2_2") (pintype "passive"))
      (node (ref "C8") (pin "2") (pinfunction "2_2") (pintype "passive"))
      (node (ref "C81") (pin "2") (pinfunction "2_2") (pintype "passive"))
      (node (ref "C82") (pin "2") (pinfunction "2_2") (pintype "passive"))
      (node (ref "C83") (pin "2") (pinfunction "2_2") (pintype "passive"))
      (node (ref "C84") (pin "2") (pinfunction "2_2") (pintype "passive"))
      (node (ref "C85") (pin "2") (pinfunction "2_2") (pintype "passive"))
      (node (ref "C86") (pin "2") (pinfunction "2_2") (pintype "passive"))
      (node (ref "C87") (pin "2") (pinfunction "2_2") (pintype "passive"))
      (node (ref "C88") (pin "2") (pinfunction "2_2") (pintype "passive"))
      (node (ref "C89") (pin "2") (pinfunction "2_2") (pintype "passive"))
      (node (ref "C90") (pin "2") (pinfunction "2_2") (pintype "passive"))
      (node (ref "C91") (pin "2") (pinfunction "2_2") (pintype "passive"))
      (node (ref "C94") (pin "2") (pinfunction "2_2") (pintype "passive"))
      (node (ref "C95") (pin "1") (pinfunction "1_1") (pintype "passive"))
      (node (ref "C97") (pin "1") (pinfunction "1_1") (pintype "passive"))
      (node (ref "IC1") (pin "13") (pinfunction "PGND_13") (pintype "bidirectional"))
      (node (ref "IC1") (pin "4") (pinfunction "AGND_4") (pintype "bidirectional"))
      (node (ref "IC1") (pin "5") (pinfunction "PGND_5") (pintype "bidirectional"))
      (node (ref "IC1") (pin "6") (pinfunction "PGND_6") (pintype "bidirectional"))
      (node (ref "IC10") (pin "11") (pinfunction "GND_RF_11") (pintype "bidirectional"))
      (node (ref "IC10") (pin "18") (pinfunction "GND_VCO_18") (pintype "bidirectional"))
      (node (ref "IC10") (pin "21") (pinfunction "GND_TUNE_21") (pintype "bidirectional"))
      (node (ref "IC10") (pin "27") (pinfunction "GND_DIG_27") (pintype "bidirectional"))
      (node (ref "IC10") (pin "31") (pinfunction "GND_SD_31") (pintype "bidirectional"))
      (node (ref "IC10") (pin "33") (pinfunction "EP_33") (pintype "bidirectional"))
      (node (ref "IC10") (pin "8") (pinfunction "GND_CP_8") (pintype "bidirectional"))
      (node (ref "IC10") (pin "9") (pinfunction "GND_PLL_9") (pintype "bidirectional"))
      (node (ref "IC11") (pin "10") (pinfunction "GND_10") (pintype "bidirectional"))
      (node (ref "IC11") (pin "12") (pinfunction "GND_12") (pintype "bidirectional"))
      (node (ref "IC11") (pin "13") (pinfunction "GND_13") (pintype "bidirectional"))
      (node (ref "IC11") (pin "5") (pinfunction "GND_5") (pintype "bidirectional"))
      (node (ref "IC11") (pin "8") (pinfunction "GND_8") (pintype "bidirectional"))
      (node (ref "IC12") (pin "10") (pinfunction "GND_10") (pintype "bidirectional"))
      (node (ref "IC12") (pin "12") (pinfunction "GND_12") (pintype "bidirectional"))
      (node (ref "IC12") (pin "13") (pinfunction "GND_13") (pintype "bidirectional"))
      (node (ref "IC12") (pin "5") (pinfunction "GND_5") (pintype "bidirectional"))
      (node (ref "IC12") (pin "8") (pinfunction "GND_8") (pintype "bidirectional"))
      (node (ref "IC13") (pin "1") (pinfunction "GND_1") (pintype "bidirectional"))
      (node (ref "IC13") (pin "10") (pinfunction "GND_10") (pintype "bidirectional"))
      (node (ref "IC13") (pin "11") (pinfunction "GND_11") (pintype "bidirectional"))
      (node (ref "IC13") (pin "12") (pinfunction "GND_12") (pintype "bidirectional"))
      (node (ref "IC13") (pin "14") (pinfunction "GND_14") (pintype "bidirectional"))
      (node (ref "IC13") (pin "15") (pinfunction "GND_15") (pintype "bidirectional"))
      (node (ref "IC13") (pin "18") (pinfunction "GND_18") (pintype "bidirectional"))
      (node (ref "IC13") (pin "19") (pinfunction "GND_19") (pintype "bidirectional"))
      (node (ref "IC13") (pin "2") (pinfunction "GND_2") (pintype "bidirectional"))
      (node (ref "IC13") (pin "21") (pinfunction "GND_21") (pintype "bidirectional"))
      (node (ref "IC13") (pin "4") (pinfunction "GND_4") (pintype "bidirectional"))
      (node (ref "IC13") (pin "5") (pinfunction "GND_5") (pintype "bidirectional"))
      (node (ref "IC13") (pin "6") (pinfunction "GND_6") (pintype "bidirectional"))
      (node (ref "IC13") (pin "7") (pinfunction "GND_7") (pintype "bidirectional"))
      (node (ref "IC13") (pin "9") (pinfunction "GND_9") (pintype "bidirectional"))
      (node (ref "IC14") (pin "10") (pinfunction "GND_10") (pintype "bidirectional"))
      (node (ref "IC14") (pin "11") (pinfunction "GND_11") (pintype "bidirectional"))
      (node (ref "IC14") (pin "12") (pinfunction "GND_12") (pintype "bidirectional"))
      (node (ref "IC14") (pin "13") (pinfunction "GND_13") (pintype "bidirectional"))
      (node (ref "IC14") (pin "15") (pinfunction "GND_15") (pintype "bidirectional"))
      (node (ref "IC14") (pin "25") (pinfunction "GND_25") (pintype "bidirectional"))
      (node (ref "IC14") (pin "3") (pinfunction "MODE_3") (pintype "bidirectional"))
      (node (ref "IC14") (pin "4") (pinfunction "GND_4") (pintype "bidirectional"))
      (node (ref "IC14") (pin "6") (pinfunction "GND_6") (pintype "bidirectional"))
      (node (ref "IC14") (pin "7") (pinfunction "GND_7") (pintype "bidirectional"))
      (node (ref "IC14") (pin "8") (pinfunction "GND_8") (pintype "bidirectional"))
      (node (ref "IC14") (pin "9") (pinfunction "GND_9") (pintype "bidirectional"))
      (node (ref "IC15") (pin "3") (pinfunction "GND_3") (pintype "bidirectional"))
      (node (ref "IC15") (pin "4") (pinfunction "GND_4") (pintype "bidirectional"))
      (node (ref "IC15") (pin "6") (pinfunction "GND_6") (pintype "bidirectional"))
      (node (ref "IC15") (pin "8") (pinfunction "GND_8") (pintype "bidirectional"))
      (node (ref "IC15") (pin "9") (pinfunction "GND_9") (pintype "bidirectional"))
      (node (ref "IC16") (pin "1") (pinfunction "GND_1") (pintype "bidirectional"))
      (node (ref "IC16") (pin "10") (pinfunction "GND_10") (pintype "bidirectional"))
      (node (ref "IC16") (pin "11") (pinfunction "GND_11") (pintype "bidirectional"))
      (node (ref "IC16") (pin "12") (pinfunction "GND_12") (pintype "bidirectional"))
      (node (ref "IC16") (pin "14") (pinfunction "GND_14") (pintype "bidirectional"))
      (node (ref "IC16") (pin "15") (pinfunction "GND_15") (pintype "bidirectional"))
      (node (ref "IC16") (pin "18") (pinfunction "GND_18") (pintype "bidirectional"))
      (node (ref "IC16") (pin "19") (pinfunction "GND_19") (pintype "bidirectional"))
      (node (ref "IC16") (pin "2") (pinfunction "GND_2") (pintype "bidirectional"))
      (node (ref "IC16") (pin "21") (pinfunction "GND_21") (pintype "bidirectional"))
      (node (ref "IC16") (pin "4") (pinfunction "GND_4") (pintype "bidirectional"))
      (node (ref "IC16") (pin "5") (pinfunction "GND_5") (pintype "bidirectional"))
      (node (ref "IC16") (pin "6") (pinfunction "GND_6") (pintype "bidirectional"))
      (node (ref "IC16") (pin "7") (pinfunction "GND_7") (pintype "bidirectional"))
      (node (ref "IC16") (pin "9") (pinfunction "GND_9") (pintype "bidirectional"))
      (node (ref "IC17") (pin "1") (pinfunction "GND_1") (pintype "bidirectional"))
      (node (ref "IC17") (pin "10") (pinfunction "GND_10") (pintype "bidirectional"))
      (node (ref "IC17") (pin "11") (pinfunction "GND_11") (pintype "bidirectional"))
      (node (ref "IC17") (pin "12") (pinfunction "GND_12") (pintype "bidirectional"))
      (node (ref "IC17") (pin "14") (pinfunction "GND_14") (pintype "bidirectional"))
      (node (ref "IC17") (pin "15") (pinfunction "GND_15") (pintype "bidirectional"))
      (node (ref "IC17") (pin "16") (pinfunction "CTL2_16") (pintype "bidirectional"))
      (node (ref "IC17") (pin "18") (pinfunction "GND_18") (pintype "bidirectional"))
      (node (ref "IC17") (pin "19") (pinfunction "GND_19") (pintype "bidirectional"))
      (node (ref "IC17") (pin "2") (pinfunction "GND_2") (pintype "bidirectional"))
      (node (ref "IC17") (pin "21") (pinfunction "GND_21") (pintype "bidirectional"))
      (node (ref "IC17") (pin "4") (pinfunction "GND_4") (pintype "bidirectional"))
      (node (ref "IC17") (pin "5") (pinfunction "GND_5") (pintype "bidirectional"))
      (node (ref "IC17") (pin "6") (pinfunction "GND_6") (pintype "bidirectional"))
      (node (ref "IC17") (pin "7") (pinfunction "GND_7") (pintype "bidirectional"))
      (node (ref "IC17") (pin "9") (pinfunction "GND_9") (pintype "bidirectional"))
      (node (ref "IC18") (pin "1") (pinfunction "GND_1") (pintype "bidirectional"))
      (node (ref "IC18") (pin "10") (pinfunction "GND_10") (pintype "bidirectional"))
      (node (ref "IC18") (pin "11") (pinfunction "GND_11") (pintype "bidirectional"))
      (node (ref "IC18") (pin "12") (pinfunction "GND_12") (pintype "bidirectional"))
      (node (ref "IC18") (pin "14") (pinfunction "GND_14") (pintype "bidirectional"))
      (node (ref "IC18") (pin "15") (pinfunction "GND_15") (pintype "bidirectional"))
      (node (ref "IC18") (pin "16") (pinfunction "CTL2_16") (pintype "bidirectional"))
      (node (ref "IC18") (pin "18") (pinfunction "GND_18") (pintype "bidirectional"))
      (node (ref "IC18") (pin "19") (pinfunction "GND_19") (pintype "bidirectional"))
      (node (ref "IC18") (pin "2") (pinfunction "GND_2") (pintype "bidirectional"))
      (node (ref "IC18") (pin "21") (pinfunction "GND_21") (pintype "bidirectional"))
      (node (ref "IC18") (pin "4") (pinfunction "GND_4") (pintype "bidirectional"))
      (node (ref "IC18") (pin "5") (pinfunction "GND_5") (pintype "bidirectional"))
      (node (ref "IC18") (pin "6") (pinfunction "GND_6") (pintype "bidirectional"))
      (node (ref "IC18") (pin "7") (pinfunction "GND_7") (pintype "bidirectional"))
      (node (ref "IC18") (pin "9") (pinfunction "GND_9") (pintype "bidirectional"))
      (node (ref "IC19") (pin "1") (pinfunction "GND_1") (pintype "power_in"))
      (node (ref "IC2") (pin "17") (pinfunction "SGND_17") (pintype "bidirectional"))
      (node (ref "IC2") (pin "3") (pinfunction "PGND_3") (pintype "bidirectional"))
      (node (ref "IC2") (pin "5") (pinfunction "SGND_5") (pintype "bidirectional"))
      (node (ref "IC2") (pin "6") (pinfunction "PGND_6") (pintype "bidirectional"))
      (node (ref "IC20") (pin "2") (pinfunction "GND_2") (pintype "power_in"))
      (node (ref "IC21") (pin "11") (pinfunction "GND_RF_11") (pintype "bidirectional"))
      (node (ref "IC21") (pin "18") (pinfunction "GND_VCO_18") (pintype "bidirectional"))
      (node (ref "IC21") (pin "21") (pinfunction "GND_TUNE_21") (pintype "bidirectional"))
      (node (ref "IC21") (pin "27") (pinfunction "GND_DIG_27") (pintype "bidirectional"))
      (node (ref "IC21") (pin "31") (pinfunction "GND_SD_31") (pintype "bidirectional"))
      (node (ref "IC21") (pin "33") (pinfunction "EP_33") (pintype "bidirectional"))
      (node (ref "IC21") (pin "8") (pinfunction "GND_CP_8") (pintype "bidirectional"))
      (node (ref "IC21") (pin "9") (pinfunction "GND_PLL_9") (pintype "bidirectional"))
      (node (ref "IC22") (pin "9") (pinfunction "GND_9") (pintype "bidirectional"))
      (node (ref "IC23") (pin "6") (pinfunction "V-_6") (pintype "power_in"))
      (node (ref "IC24") (pin "1") (pinfunction "GND_1") (pintype "bidirectional"))
      (node (ref "IC24") (pin "12") (pinfunction "GND_12") (pintype "bidirectional"))
      (node (ref "IC24") (pin "14") (pinfunction "GND_14") (pintype "bidirectional"))
      (node (ref "IC24") (pin "17") (pinfunction "GND_17") (pintype "bidirectional"))
      (node (ref "IC24") (pin "19") (pinfunction "GND_19") (pintype "bidirectional"))
      (node (ref "IC24") (pin "2") (pinfunction "GND_2") (pintype "bidirectional"))
      (node (ref "IC24") (pin "23") (pinfunction "GND_23") (pintype "bidirectional"))
      (node (ref "IC24") (pin "25") (pinfunction "GND_25") (pintype "bidirectional"))
      (node (ref "IC24") (pin "5") (pinfunction "GND_5") (pintype "bidirectional"))
      (node (ref "IC24") (pin "6") (pinfunction "GND_6") (pintype "bidirectional"))
      (node (ref "IC24") (pin "8") (pinfunction "GND_8") (pintype "bidirectional"))
      (node (ref "IC25") (pin "2") (pinfunction "GND_2") (pintype "power_in"))
      (node (ref "IC26") (pin "5") (pinfunction "GND_5") (pintype "bidirectional"))
      (node (ref "IC27") (pin "9") (pinfunction "GND_9") (pintype "bidirectional"))
      (node (ref "IC28") (pin "6") (pinfunction "V-_6") (pintype "power_in"))
      (node (ref "IC29") (pin "1") (pinfunction "GND_1") (pintype "bidirectional"))
      (node (ref "IC29") (pin "12") (pinfunction "GND_12") (pintype "bidirectional"))
      (node (ref "IC29") (pin "14") (pinfunction "GND_14") (pintype "bidirectional"))
      (node (ref "IC29") (pin "17") (pinfunction "GND_17") (pintype "bidirectional"))
      (node (ref "IC29") (pin "19") (pinfunction "GND_19") (pintype "bidirectional"))
      (node (ref "IC29") (pin "2") (pinfunction "GND_2") (pintype "bidirectional"))
      (node (ref "IC29") (pin "23") (pinfunction "GND_23") (pintype "bidirectional"))
      (node (ref "IC29") (pin "25") (pinfunction "GND_25") (pintype "bidirectional"))
      (node (ref "IC29") (pin "5") (pinfunction "GND_5") (pintype "bidirectional"))
      (node (ref "IC29") (pin "6") (pinfunction "GND_6") (pintype "bidirectional"))
      (node (ref "IC29") (pin "8") (pinfunction "GND_8") (pintype "bidirectional"))
      (node (ref "IC3") (pin "1") (pinfunction "GND_1") (pintype "bidirectional"))
      (node (ref "IC3") (pin "7") (pinfunction "GND_7") (pintype "bidirectional"))
      (node (ref "IC30") (pin "2") (pinfunction "GND_2") (pintype "power_in"))
      (node (ref "IC31") (pin "5") (pinfunction "GND_5") (pintype "bidirectional"))
      (node (ref "IC32") (pin "6") (pinfunction "V-_6") (pintype "power_in"))
      (node (ref "IC33") (pin "1") (pinfunction "GND_1") (pintype "bidirectional"))
      (node (ref "IC33") (pin "12") (pinfunction "GND_12") (pintype "bidirectional"))
      (node (ref "IC33") (pin "14") (pinfunction "GND_14") (pintype "bidirectional"))
      (node (ref "IC33") (pin "17") (pinfunction "GND_17") (pintype "bidirectional"))
      (node (ref "IC33") (pin "19") (pinfunction "GND_19") (pintype "bidirectional"))
      (node (ref "IC33") (pin "2") (pinfunction "GND_2") (pintype "bidirectional"))
      (node (ref "IC33") (pin "23") (pinfunction "GND_23") (pintype "bidirectional"))
      (node (ref "IC33") (pin "25") (pinfunction "GND_25") (pintype "bidirectional"))
      (node (ref "IC33") (pin "5") (pinfunction "GND_5") (pintype "bidirectional"))
      (node (ref "IC33") (pin "6") (pinfunction "GND_6") (pintype "bidirectional"))
      (node (ref "IC33") (pin "8") (pinfunction "GND_8") (pintype "bidirectional"))
      (node (ref "IC34") (pin "2") (pinfunction "GND_2") (pintype "power_in"))
      (node (ref "IC35") (pin "5") (pinfunction "GND_5") (pintype "bidirectional"))
      (node (ref "IC36") (pin "9") (pinfunction "GND_9") (pintype "bidirectional"))
      (node (ref "IC37") (pin "46") (pinfunction "PB8-BOOT0_46") (pintype "bidirectional"))
      (node (ref "IC37") (pin "49") (pinfunction "GND_49") (pintype "bidirectional"))
      (node (ref "IC4") (pin "1") (pinfunction "GND_1") (pintype "bidirectional"))
      (node (ref "IC4") (pin "7") (pinfunction "GND_7") (pintype "bidirectional"))
      (node (ref "IC5") (pin "1") (pinfunction "GND_1") (pintype "bidirectional"))
      (node (ref "IC5") (pin "7") (pinfunction "GND_7") (pintype "bidirectional"))
      (node (ref "IC6") (pin "1") (pinfunction "GND_1") (pintype "bidirectional"))
      (node (ref "IC6") (pin "7") (pinfunction "GND_7") (pintype "bidirectional"))
      (node (ref "IC7") (pin "21") (pinfunction "GND_21") (pintype "bidirectional"))
      (node (ref "IC8") (pin "1") (pinfunction "GND_1") (pintype "power_in"))
      (node (ref "IC9") (pin "2") (pinfunction "GND_2") (pintype "power_in"))
      (node (ref "J1") (pin "2") (pinfunction "2_2") (pintype "passive"))
      (node (ref "J2") (pin "G@1") (pinfunction "2_G@1") (pintype "passive"))
      (node (ref "J2") (pin "G@2") (pinfunction "2_G@2") (pintype "passive"))
      (node (ref "J2") (pin "G@3") (pinfunction "2_G@3") (pintype "passive"))
      (node (ref "J2") (pin "G@4") (pinfunction "2_G@4") (pintype "passive"))
      (node (ref "J3") (pin "G@1") (pinfunction "2_G@1") (pintype "passive"))
      (node (ref "J3") (pin "G@2") (pinfunction "2_G@2") (pintype "passive"))
      (node (ref "J3") (pin "G@3") (pinfunction "2_G@3") (pintype "passive"))
      (node (ref "J3") (pin "G@4") (pinfunction "2_G@4") (pintype "passive"))
      (node (ref "J4") (pin "1") (pinfunction "GND_1") (pintype "bidirectional"))
      (node (ref "J4") (pin "12") (pinfunction "GND_12") (pintype "bidirectional"))
      (node (ref "J4") (pin "M1") (pinfunction "CASE_M1") (pintype "bidirectional"))
      (node (ref "J4") (pin "M2") (pinfunction "CASE_M2") (pintype "bidirectional"))
      (node (ref "J4") (pin "M3") (pinfunction "CASE_M3") (pintype "bidirectional"))
      (node (ref "J4") (pin "M4") (pinfunction "CASE_M4") (pintype "bidirectional"))
      (node (ref "JP1") (pin "7") (pinfunction "7_7") (pintype "passive"))
      (node (ref "JP2") (pin "20") (pinfunction "20_20") (pintype "passive"))
      (node (ref "L30") (pin "2") (pinfunction "2_2") (pintype "passive"))
      (node (ref "L31") (pin "2") (pinfunction "2_2") (pintype "passive"))
      (node (ref "L38") (pin "2") (pinfunction "2_2") (pintype "passive"))
      (node (ref "L39") (pin "2") (pinfunction "2_2") (pintype "passive"))
      (node (ref "L52") (pin "2") (pinfunction "2_2") (pintype "passive"))
      (node (ref "L53") (pin "2") (pinfunction "2_2") (pintype "passive"))
      (node (ref "LP1") (pin "2") (pinfunction "GND_2") (pintype "bidirectional"))
      (node (ref "LP1") (pin "3") (pinfunction "GND_3") (pintype "bidirectional"))
      (node (ref "LP2") (pin "2") (pinfunction "GND_2") (pintype "bidirectional"))
      (node (ref "LP2") (pin "3") (pinfunction "GND_3") (pintype "bidirectional"))
      (node (ref "LP3") (pin "2") (pinfunction "GND_2") (pintype "bidirectional"))
      (node (ref "LP3") (pin "3") (pinfunction "GND_3") (pintype "bidirectional"))
      (node (ref "R10") (pin "1") (pinfunction "1_1") (pintype "passive"))
      (node (ref "R11") (pin "1") (pinfunction "1_1") (pintype "passive"))
      (node (ref "R115") (pin "2") (pinfunction "2_2") (pintype "passive"))
      (node (ref "R122") (pin "1") (pinfunction "1_1") (pintype "passive"))
      (node (ref "R131") (pin "1") (pinfunction "1_1") (pintype "passive"))
      (node (ref "R133") (pin "1") (pinfunction "1_1") (pintype "passive"))
      (node (ref "R134") (pin "2") (pinfunction "2_2") (pintype "passive"))
      (node (ref "R14") (pin "1") (pinfunction "1_1") (pintype "passive"))
      (node (ref "R169") (pin "2") (pinfunction "2_2") (pintype "passive"))
      (node (ref "R17") (pin "2") (pinfunction "2_2") (pintype "passive"))
      (node (ref "R172") (pin "2") (pinfunction "2_2") (pintype "passive"))
      (node (ref "R174") (pin "2") (pinfunction "2_2") (pintype "passive"))
      (node (ref "R175") (pin "2") (pinfunction "2_2") (pintype "passive"))
      (node (ref "R18") (pin "2") (pinfunction "2_2") (pintype "passive"))
      (node (ref "R19") (pin "2") (pinfunction "2_2") (pintype "passive"))
      (node (ref "R23") (pin "2") (pinfunction "2_2") (pintype "passive"))
      (node (ref "R25") (pin "2") (pinfunction "2_2") (pintype "passive"))
      (node (ref "R28") (pin "1") (pinfunction "1_1") (pintype "passive"))
      (node (ref "R3") (pin "1") (pinfunction "1_1") (pintype "passive"))
      (node (ref "R30") (pin "1") (pinfunction "1_1") (pintype "passive"))
      (node (ref "R31") (pin "1") (pinfunction "1_1") (pintype "passive"))
      (node (ref "R38") (pin "1") (pinfunction "1_1") (pintype "passive"))
      (node (ref "R39") (pin "2") (pinfunction "2_2") (pintype "passive"))
      (node (ref "R40") (pin "3") (pinfunction "GND_3") (pintype "bidirectional"))
      (node (ref "R47") (pin "3") (pinfunction "GND_3") (pintype "bidirectional"))
      (node (ref "R48") (pin "3") (pinfunction "GND_3") (pintype "bidirectional"))
      (node (ref "R49") (pin "3") (pinfunction "GND_3") (pintype "bidirectional"))
      (node (ref "R5") (pin "1") (pinfunction "1_1") (pintype "passive"))
      (node (ref "R50") (pin "2") (pinfunction "2_2") (pintype "passive"))
      (node (ref "R6") (pin "1") (pinfunction "1_1") (pintype "passive"))
      (node (ref "R7") (pin "2") (pinfunction "2_2") (pintype "passive"))
      (node (ref "R76") (pin "2") (pinfunction "2_2") (pintype "passive"))
      (node (ref "R9") (pin "1") (pinfunction "1_1") (pintype "passive"))
      (node (ref "T3") (pin "4") (pinfunction "OUT+_4") (pintype "bidirectional"))
      (node (ref "TP10") (pin "TP") (pinfunction "TP_TP") (pintype "input"))
      (node (ref "TP12") (pin "TP") (pinfunction "TP_TP") (pintype "input"))
      (node (ref "TP4") (pin "TP") (pinfunction "TP_TP") (pintype "input"))
      (node (ref "TP6") (pin "TP") (pinfunction "TP_TP") (pintype "input"))
      (node (ref "TP8") (pin "TP") (pinfunction "TP_TP") (pintype "input"))
      (node (ref "U1") (pin "4") (pinfunction "GND_4") (pintype "power_in"))
      (node (ref "U2") (pin "P108") (pinfunction "GND_P108") (pintype "power_in"))
      (node (ref "U2") (pin "P113") (pinfunction "GND_P113") (pintype "power_in"))
      (node (ref "U2") (pin "P13") (pinfunction "GND_P13") (pintype "power_in"))
      (node (ref "U2") (pin "P130") (pinfunction "GND_P130") (pintype "power_in"))
      (node (ref "U2") (pin "P136") (pinfunction "GND_P136") (pintype "power_in"))
      (node (ref "U2") (pin "P25") (pinfunction "GND_P25") (pintype "power_in"))
      (node (ref "U2") (pin "P3") (pinfunction "GND_P3") (pintype "power_in"))
      (node (ref "U2") (pin "P49") (pinfunction "GND_P49") (pintype "power_in"))
      (node (ref "U2") (pin "P54") (pinfunction "GND_P54") (pintype "power_in"))
      (node (ref "U2") (pin "P68") (pinfunction "GND_P68") (pintype "power_in"))
      (node (ref "U2") (pin "P73") (pinfunction "SUSPEND_P73") (pintype "input"))
      (node (ref "U2") (pin "P77") (pinfunction "GND_P77") (pintype "power_in"))
      (node (ref "U2") (pin "P91") (pinfunction "GND_P91") (pintype "power_in"))
      (node (ref "U2") (pin "P96") (pinfunction "GND_P96") (pintype "power_in"))
      (node (ref "X1") (pin "G@1") (pinfunction "2_G@1") (pintype "passive"))
      (node (ref "X1") (pin "G@2") (pinfunction "2_G@2") (pintype "passive"))
      (node (ref "X1") (pin "G@3") (pinfunction "2_G@3") (pintype "passive"))
      (node (ref "X1") (pin "G@4") (pinfunction "2_G@4") (pintype "passive"))
      (node (ref "X2") (pin "G@1") (pinfunction "2_G@1") (pintype "passive"))
      (node (ref "X2") (pin "G@2") (pinfunction "2_G@2") (pintype "passive"))
      (node (ref "X2") (pin "G@3") (pinfunction "2_G@3") (pintype "passive"))
      (node (ref "X2") (pin "G@4") (pinfunction "2_G@4") (pintype "passive"))
      (node (ref "Y1") (pin "1") (pinfunction "GND/NC_1") (pintype "power_in"))
      (node (ref "Y1") (pin "2") (pinfunction "GND_2") (pintype "power_in"))
    )
    (net (code "31") (name "HIGHBAND_SELECT") (class "Default")
      (node (ref "C245") (pin "1") (pinfunction "1_1") (pintype "passive"))
      (node (ref "R154") (pin "2") (pinfunction "2_2") (pintype "passive"))
      (node (ref "U2") (pin "P21") (pinfunction "IO_L42N_GCLK24_3_P21") (pintype "bidirectional"))
    )
    (net (code "32") (name "LO1_CE") (class "Default")
      (node (ref "IC21") (pin "4") (pinfunction "CE_4") (pintype "bidirectional"))
      (node (ref "R31") (pin "2") (pinfunction "2_2") (pintype "passive"))
      (node (ref "U2") (pin "P45") (pinfunction "IO_L49N_D4_2_P45") (pintype "bidirectional"))
    )
    (net (code "33") (name "LO1_CLK") (class "Default")
      (node (ref "IC21") (pin "1") (pinfunction "CLK_1") (pintype "input"))
      (node (ref "U2") (pin "P48") (pinfunction "IO_L48P_D7_2_P48") (pintype "bidirectional"))
    )
    (net (code "34") (name "LO1_LD") (class "Default")
      (node (ref "IC21") (pin "25") (pinfunction "LD_25") (pintype "output"))
      (node (ref "U2") (pin "P56") (pinfunction "IO_L30P_GCLK1_D13_2_P56") (pintype "bidirectional"))
    )
    (net (code "35") (name "LO1_LE") (class "Default")
      (node (ref "IC21") (pin "3") (pinfunction "LE_3") (pintype "input"))
      (node (ref "U2") (pin "P46") (pinfunction "IO_L49P_D3_2_P46") (pintype "bidirectional"))
    )
    (net (code "36") (name "LO1_MOSI") (class "Default")
      (node (ref "IC21") (pin "2") (pinfunction "DATA_2") (pintype "input"))
      (node (ref "U2") (pin "P47") (pinfunction "IO_L48N_RDWR_B_VREF_2_P47") (pintype "bidirectional"))
    )
    (net (code "37") (name "LO1_MUX") (class "Default")
      (node (ref "IC21") (pin "30") (pinfunction "MUX_30") (pintype "bidirectional"))
      (node (ref "U2") (pin "P51") (pinfunction "IO_L31P_GCLK31_D14_2_P51") (pintype "bidirectional"))
    )
    (net (code "38") (name "LO1_REF") (class "Default")
      (node (ref "C80") (pin "1") (pinfunction "1_1") (pintype "passive"))
      (node (ref "IC7") (pin "17") (pinfunction "CLK5_17") (pintype "bidirectional"))
    )
    (net (code "39") (name "LO1_RF_EN") (class "Default")
      (node (ref "IC21") (pin "26") (pinfunction "RFOUT_EN_26") (pintype "input"))
      (node (ref "U2") (pin "P55") (pinfunction "IO_L30N_GCLK0_USERCCLK_2_P55") (pintype "bidirectional"))
    )
    (net (code "40") (name "LOWBAND_SELECT") (class "Default")
      (node (ref "C247") (pin "1") (pinfunction "1_1") (pintype "passive"))
      (node (ref "R155") (pin "2") (pinfunction "2_2") (pintype "passive"))
      (node (ref "U2") (pin "P17") (pinfunction "IO_L43P_GCLK23_3_P17") (pintype "bidirectional"))
    )
    (net (code "41") (name "MCU_AUX1") (class "Default")
      (node (ref "IC37") (pin "9") (pinfunction "PA1_9") (pintype "bidirectional"))
      (node (ref "U2") (pin "P78") (pinfunction "IO_L47N_1_P78") (pintype "bidirectional"))
    )
    (net (code "42") (name "MCU_AUX2") (class "Default")
      (node (ref "IC37") (pin "10") (pinfunction "PA2_10") (pintype "bidirectional"))
      (node (ref "U2") (pin "P74") (pinfunction "IO_L74N_DOUT_BUSY_1_P74") (pintype "bidirectional"))
    )
    (net (code "43") (name "MCU_AUX3") (class "Default")
      (node (ref "IC37") (pin "11") (pinfunction "PA3_11") (pintype "bidirectional"))
      (node (ref "U2") (pin "P75") (pinfunction "IO_L74P_AWAKE_1_P75") (pintype "bidirectional"))
    )
    (net (code "44") (name "MCU_FLASH_CS") (class "Default")
      (node (ref "IC37") (pin "17") (pinfunction "PB0_17") (pintype "bidirectional"))
      (node (ref "R107") (pin "1") (pinfunction "1_1") (pintype "passive"))
    )
    (net (code "45") (name "MCU_FPGA_CCLK") (class "Default")
      (node (ref "IC37") (pin "26") (pinfunction "PB13_26") (pintype "bidirectional"))
      (node (ref "R109") (pin "1") (pinfunction "1_1") (pintype "passive"))
    )
    (net (code "46") (name "MCU_FPGA_DIN") (class "Default")
      (node (ref "IC37") (pin "28") (pinfunction "PB15_28") (pintype "bidirectional"))
      (node (ref "R110") (pin "1") (pinfunction "1_1") (pintype "passive"))
    )
    (net (code "47") (name "MCU_FPGA_NSS") (class "Default")
      (node (ref "IC37") (pin "12") (pinfunction "PA4_12") (pintype "bidirectional"))
      (node (ref "U2") (pin "P67") (pinfunction "IO_L2P_CMPCLK_2_P67") (pintype "bidirectional"))
    )
    (net (code "48") (name "MCU_FPGA_UNUSED1") (class "Default")
      (node (ref "IC37") (pin "43") (pinfunction "PB5_43") (pintype "bidirectional"))
      (node (ref "U2") (pin "P79") (pinfunction "IO_L47P_1_P79") (pintype "bidirectional"))
    )
    (net (code "49") (name "MCU_FPGA_UNUSED2") (class "Default")
      (node (ref "IC37") (pin "41") (pinfunction "PB3_41") (pintype "bidirectional"))
      (node (ref "U2") (pin "P80") (pinfunction "IO_L46N_1_P80") (pintype "bidirectional"))
    )
    (net (code "50") (name "MCU_FPGA_UNUSED3") (class "Default")
      (node (ref "IC37") (pin "40") (pinfunction "PC11_40") (pintype "bidirectional"))
      (node (ref "U2") (pin "P81") (pinfunction "IO_L46P_1_P81") (pintype "bidirectional"))
    )
    (net (code "51") (name "MCU_INTR") (class "Default")
      (node (ref "IC37") (pin "18") (pinfunction "PB1_18") (pintype "bidirectional"))
      (node (ref "U2") (pin "P59") (pinfunction "IO_L13N_D10_2_P59") (pintype "bidirectional"))
    )
    (net (code "52") (name "MCU_MISO") (class "Default")
      (node (ref "IC37") (pin "14") (pinfunction "PA6_14") (pintype "bidirectional"))
      (node (ref "R106") (pin "1") (pinfunction "1_1") (pintype "passive"))
      (node (ref "U2") (pin "P62") (pinfunction "IO_L12P_D1_MISO2_2_P62") (pintype "bidirectional"))
    )
    (net (code "53") (name "MCU_MOSI") (class "Default")
      (node (ref "IC37") (pin "15") (pinfunction "PA7_15") (pintype "bidirectional"))
      (node (ref "R105") (pin "1") (pinfunction "1_1") (pintype "passive"))
      (node (ref "U2") (pin "P61") (pinfunction "IO_L12N_D2_MISO3_2_P61") (pintype "bidirectional"))
    )
    (net (code "54") (name "MCU_SCK") (class "Default")
      (node (ref "IC37") (pin "13") (pinfunction "PA5_13") (pintype "bidirectional"))
      (node (ref "R104") (pin "1") (pinfunction "1_1") (pintype "passive"))
      (node (ref "U2") (pin "P66") (pinfunction "IO_L2N_CMPMOSI_2_P66") (pintype "bidirectional"))
    )
    (net (code "55") (name "NRST") (class "Default")
      (node (ref "IC37") (pin "7") (pinfunction "PG10-NRST_7") (pintype "bidirectional"))
      (node (ref "JP1") (pin "9") (pinfunction "9_9") (pintype "passive"))
    )
    (net (code "56") (name "Net-(C5-Pad2)") (class "Default")
      (node (ref "C5") (pin "2") (pinfunction "2_2") (pintype "passive"))
      (node (ref "R1") (pin "1") (pinfunction "1_1") (pintype "passive"))
    )
    (net (code "57") (name "Net-(C30-Pad1)") (class "Default")
      (node (ref "C30") (pin "1") (pinfunction "1_1") (pintype "passive"))
      (node (ref "X1") (pin "1") (pinfunction "1_1") (pintype "passive"))
    )
    (net (code "58") (name "Net-(C39-Pad2)") (class "Default")
      (node (ref "C39") (pin "2") (pinfunction "2_2") (pintype "passive"))
      (node (ref "X2") (pin "1") (pinfunction "1_1") (pintype "passive"))
    )
    (net (code "59") (name "Net-(C40-Pad1)") (class "Default")
      (node (ref "C40") (pin "1") (pinfunction "1_1") (pintype "passive"))
      (node (ref "R180") (pin "2") (pinfunction "2_2") (pintype "passive"))
      (node (ref "R181") (pin "1") (pinfunction "1_1") (pintype "passive"))
    )
    (net (code "60") (name "Net-(C41-Pad1)") (class "Default")
      (node (ref "C41") (pin "1") (pinfunction "1_1") (pintype "passive"))
      (node (ref "R178") (pin "1") (pinfunction "1_1") (pintype "passive"))
      (node (ref "R179") (pin "2") (pinfunction "2_2") (pintype "passive"))
    )
    (net (code "61") (name "Net-(C42-Pad1)") (class "Default")
      (node (ref "C42") (pin "1") (pinfunction "1_1") (pintype "passive"))
      (node (ref "R176") (pin "2") (pinfunction "2_2") (pintype "passive"))
      (node (ref "R177") (pin "1") (pinfunction "1_1") (pintype "passive"))
    )
    (net (code "62") (name "Net-(C43-Pad1)") (class "Default")
      (node (ref "C43") (pin "1") (pinfunction "1_1") (pintype "passive"))
      (node (ref "L14") (pin "2") (pinfunction "2_2") (pintype "passive"))
      (node (ref "L18") (pin "1") (pinfunction "1_1") (pintype "passive"))
    )
    (net (code "63") (name "Net-(C47-Pad1)") (class "Default")
      (node (ref "C47") (pin "1") (pinfunction "1_1") (pintype "passive"))
      (node (ref "L18") (pin "2") (pinfunction "2_2") (pintype "passive"))
      (node (ref "R7") (pin "1") (pinfunction "1_1") (pintype "passive"))
      (node (ref "R8") (pin "1") (pinfunction "1_1") (pintype "passive"))
    )
    (net (code "64") (name "Net-(C48-Pad2)") (class "Default")
      (node (ref "C48") (pin "2") (pinfunction "2_2") (pintype "passive"))
      (node (ref "R8") (pin "2") (pinfunction "2_2") (pintype "passive"))
      (node (ref "R9") (pin "2") (pinfunction "2_2") (pintype "passive"))
    )
    (net (code "65") (name "Net-(C53-Pad1)") (class "Default")
      (node (ref "C53") (pin "1") (pinfunction "1_1") (pintype "passive"))
      (node (ref "IC8") (pin "2") (pinfunction "VOUT_2") (pintype "power_in"))
      (node (ref "IC8") (pin "4") (pinfunction "VOUT_4") (pintype "power_in"))
      (node (ref "L19") (pin "1") (pinfunction "1_1") (pintype "passive"))
    )
    (net (code "66") (name "Net-(C62-Pad1)") (class "Default")
      (node (ref "C62") (pin "1") (pinfunction "1_1") (pintype "passive"))
      (node (ref "R14") (pin "2") (pinfunction "2_2") (pintype "passive"))
    )
    (net (code "67") (name "Net-(C66-Pad2)") (class "Default")
      (node (ref "C66") (pin "2") (pinfunction "2_2") (pintype "passive"))
      (node (ref "R16") (pin "1") (pinfunction "1_1") (pintype "passive"))
    )
    (net (code "68") (name "Net-(C74-Pad2)") (class "Default")
      (node (ref "C74") (pin "2") (pinfunction "2_2") (pintype "passive"))
      (node (ref "R26") (pin "1") (pinfunction "1_1") (pintype "passive"))
    )
    (net (code "69") (name "Net-(C82-Pad1)") (class "Default")
      (node (ref "C82") (pin "1") (pinfunction "1_1") (pintype "passive"))
      (node (ref "IC19") (pin "2") (pinfunction "VOUT_2") (pintype "power_in"))
      (node (ref "IC19") (pin "4") (pinfunction "VOUT_4") (pintype "power_in"))
      (node (ref "L28") (pin "1") (pinfunction "1_1") (pintype "passive"))
    )
    (net (code "70") (name "Net-(C92-Pad2)") (class "Default")
      (node (ref "C92") (pin "2") (pinfunction "2_2") (pintype "passive"))
      (node (ref "R37") (pin "1") (pinfunction "1_1") (pintype "passive"))
    )
    (net (code "71") (name "Net-(C93-Pad1)") (class "Default")
      (node (ref "C93") (pin "1") (pinfunction "1_1") (pintype "passive"))
      (node (ref "R38") (pin "2") (pinfunction "2_2") (pintype "passive"))
    )
    (net (code "72") (name "Net-(C99-Pad1)") (class "Default")
      (node (ref "C99") (pin "1") (pinfunction "1_1") (pintype "passive"))
      (node (ref "J2") (pin "1") (pinfunction "1_1") (pintype "passive"))
    )
    (net (code "73") (name "Net-(C114-Pad1)") (class "Default")
      (node (ref "C114") (pin "1") (pinfunction "1_1") (pintype "passive"))
      (node (ref "R168") (pin "1") (pinfunction "1_1") (pintype "passive"))
      (node (ref "R169") (pin "1") (pinfunction "1_1") (pintype "passive"))
    )
    (net (code "74") (name "Net-(C119-Pad1)") (class "Default")
      (node (ref "C119") (pin "1") (pinfunction "1_1") (pintype "passive"))
      (node (ref "C122") (pin "1") (pinfunction "1_1") (pintype "passive"))
      (node (ref "L16") (pin "1") (pinfunction "1_1") (pintype "passive"))
      (node (ref "L32") (pin "1") (pinfunction "1_1") (pintype "passive"))
      (node (ref "L33") (pin "1") (pinfunction "1_1") (pintype "passive"))
    )
    (net (code "75") (name "Net-(C120-Pad2)") (class "Default")
      (node (ref "C120") (pin "2") (pinfunction "2_2") (pintype "passive"))
      (node (ref "C124") (pin "1") (pinfunction "1_1") (pintype "passive"))
      (node (ref "L34") (pin "1") (pinfunction "1_1") (pintype "passive"))
    )
    (net (code "76") (name "Net-(C121-Pad1)") (class "Default")
      (node (ref "C121") (pin "1") (pinfunction "1_1") (pintype "passive"))
      (node (ref "R58") (pin "1") (pinfunction "1_1") (pintype "passive"))
      (node (ref "R61") (pin "2") (pinfunction "2_2") (pintype "passive"))
    )
    (net (code "77") (name "Net-(C121-Pad2)") (class "Default")
      (node (ref "C121") (pin "2") (pinfunction "2_2") (pintype "passive"))
      (node (ref "R59") (pin "1") (pinfunction "1_1") (pintype "passive"))
      (node (ref "R62") (pin "2") (pinfunction "2_2") (pintype "passive"))
    )
    (net (code "78") (name "Net-(C123-Pad2)") (class "Default")
      (node (ref "C123") (pin "2") (pinfunction "2_2") (pintype "passive"))
      (node (ref "C124") (pin "2") (pinfunction "2_2") (pintype "passive"))
      (node (ref "L35") (pin "1") (pinfunction "1_1") (pintype "passive"))
    )
    (net (code "79") (name "Net-(C128-Pad1)") (class "Default")
      (node (ref "C128") (pin "1") (pinfunction "1_1") (pintype "passive"))
      (node (ref "L34") (pin "2") (pinfunction "2_2") (pintype "passive"))
      (node (ref "L36") (pin "1") (pinfunction "1_1") (pintype "passive"))
    )
    (net (code "80") (name "Net-(C128-Pad2)") (class "Default")
      (node (ref "C128") (pin "2") (pinfunction "2_2") (pintype "passive"))
      (node (ref "L35") (pin "2") (pinfunction "2_2") (pintype "passive"))
      (node (ref "L37") (pin "1") (pinfunction "1_1") (pintype "passive"))
    )
    (net (code "81") (name "Net-(C130-Pad1)") (class "Default")
      (node (ref "C130") (pin "1") (pinfunction "1_1") (pintype "passive"))
      (node (ref "L36") (pin "2") (pinfunction "2_2") (pintype "passive"))
      (node (ref "R63") (pin "2") (pinfunction "2_2") (pintype "passive"))
      (node (ref "R64") (pin "2") (pinfunction "2_2") (pintype "passive"))
    )
    (net (code "82") (name "Net-(C130-Pad2)") (class "Default")
      (node (ref "C130") (pin "2") (pinfunction "2_2") (pintype "passive"))
      (node (ref "L37") (pin "2") (pinfunction "2_2") (pintype "passive"))
      (node (ref "R63") (pin "1") (pinfunction "1_1") (pintype "passive"))
      (node (ref "R65") (pin "2") (pinfunction "2_2") (pintype "passive"))
    )
    (net (code "83") (name "Net-(C136-Pad1)") (class "Default")
      (node (ref "C136") (pin "1") (pinfunction "1_1") (pintype "passive"))
      (node (ref "J3") (pin "1") (pinfunction "1_1") (pintype "passive"))
    )
    (net (code "84") (name "Net-(C156-Pad1)") (class "Default")
      (node (ref "C156") (pin "1") (pinfunction "1_1") (pintype "passive"))
      (node (ref "C159") (pin "1") (pinfunction "1_1") (pintype "passive"))
      (node (ref "L40") (pin "1") (pinfunction "1_1") (pintype "passive"))
      (node (ref "L41") (pin "1") (pinfunction "1_1") (pintype "passive"))
      (node (ref "L55") (pin "1") (pinfunction "1_1") (pintype "passive"))
    )
    (net (code "85") (name "Net-(C157-Pad2)") (class "Default")
      (node (ref "C157") (pin "2") (pinfunction "2_2") (pintype "passive"))
      (node (ref "C161") (pin "1") (pinfunction "1_1") (pintype "passive"))
      (node (ref "L42") (pin "1") (pinfunction "1_1") (pintype "passive"))
    )
    (net (code "86") (name "Net-(C158-Pad1)") (class "Default")
      (node (ref "C158") (pin "1") (pinfunction "1_1") (pintype "passive"))
      (node (ref "R85") (pin "1") (pinfunction "1_1") (pintype "passive"))
      (node (ref "R88") (pin "2") (pinfunction "2_2") (pintype "passive"))
    )
    (net (code "87") (name "Net-(C158-Pad2)") (class "Default")
      (node (ref "C158") (pin "2") (pinfunction "2_2") (pintype "passive"))
      (node (ref "R86") (pin "1") (pinfunction "1_1") (pintype "passive"))
      (node (ref "R89") (pin "2") (pinfunction "2_2") (pintype "passive"))
    )
    (net (code "88") (name "Net-(C160-Pad2)") (class "Default")
      (node (ref "C160") (pin "2") (pinfunction "2_2") (pintype "passive"))
      (node (ref "C161") (pin "2") (pinfunction "2_2") (pintype "passive"))
      (node (ref "L43") (pin "1") (pinfunction "1_1") (pintype "passive"))
    )
    (net (code "89") (name "Net-(C165-Pad1)") (class "Default")
      (node (ref "C165") (pin "1") (pinfunction "1_1") (pintype "passive"))
      (node (ref "L42") (pin "2") (pinfunction "2_2") (pintype "passive"))
      (node (ref "L44") (pin "1") (pinfunction "1_1") (pintype "passive"))
    )
    (net (code "90") (name "Net-(C165-Pad2)") (class "Default")
      (node (ref "C165") (pin "2") (pinfunction "2_2") (pintype "passive"))
      (node (ref "L43") (pin "2") (pinfunction "2_2") (pintype "passive"))
      (node (ref "L45") (pin "1") (pinfunction "1_1") (pintype "passive"))
    )
    (net (code "91") (name "Net-(C167-Pad1)") (class "Default")
      (node (ref "C167") (pin "1") (pinfunction "1_1") (pintype "passive"))
      (node (ref "L44") (pin "2") (pinfunction "2_2") (pintype "passive"))
      (node (ref "R90") (pin "2") (pinfunction "2_2") (pintype "passive"))
      (node (ref "R91") (pin "2") (pinfunction "2_2") (pintype "passive"))
    )
    (net (code "92") (name "Net-(C167-Pad2)") (class "Default")
      (node (ref "C167") (pin "2") (pinfunction "2_2") (pintype "passive"))
      (node (ref "L45") (pin "2") (pinfunction "2_2") (pintype "passive"))
      (node (ref "R90") (pin "1") (pinfunction "1_1") (pintype "passive"))
      (node (ref "R92") (pin "2") (pinfunction "2_2") (pintype "passive"))
    )
    (net (code "93") (name "Net-(C183-Pad1)") (class "Default")
      (node (ref "C183") (pin "1") (pinfunction "1_1") (pintype "passive"))
      (node (ref "R173") (pin "1") (pinfunction "1_1") (pintype "passive"))
      (node (ref "R174") (pin "1") (pinfunction "1_1") (pintype "passive"))
    )
    (net (code "94") (name "Net-(C184-Pad1)") (class "Default")
      (node (ref "C184") (pin "1") (pinfunction "1_1") (pintype "passive"))
      (node (ref "R96") (pin "1") (pinfunction "1_1") (pintype "passive"))
      (node (ref "R98") (pin "2") (pinfunction "2_2") (pintype "passive"))
    )
    (net (code "95") (name "Net-(C184-Pad2)") (class "Default")
      (node (ref "C184") (pin "2") (pinfunction "2_2") (pintype "passive"))
      (node (ref "R97") (pin "1") (pinfunction "1_1") (pintype "passive"))
      (node (ref "R99") (pin "2") (pinfunction "2_2") (pintype "passive"))
    )
    (net (code "96") (name "Net-(C190-Pad1)") (class "Default")
      (node (ref "C190") (pin "1") (pinfunction "1_1") (pintype "passive"))
      (node (ref "C193") (pin "1") (pinfunction "1_1") (pintype "passive"))
      (node (ref "L46") (pin "1") (pinfunction "1_1") (pintype "passive"))
      (node (ref "L47") (pin "1") (pinfunction "1_1") (pintype "passive"))
      (node (ref "L60") (pin "1") (pinfunction "1_1") (pintype "passive"))
    )
    (net (code "97") (name "Net-(C191-Pad2)") (class "Default")
      (node (ref "C191") (pin "2") (pinfunction "2_2") (pintype "passive"))
      (node (ref "C194") (pin "1") (pinfunction "1_1") (pintype "passive"))
      (node (ref "L48") (pin "1") (pinfunction "1_1") (pintype "passive"))
    )
    (net (code "98") (name "Net-(C192-Pad2)") (class "Default")
      (node (ref "C192") (pin "2") (pinfunction "2_2") (pintype "passive"))
      (node (ref "C194") (pin "2") (pinfunction "2_2") (pintype "passive"))
      (node (ref "L49") (pin "1") (pinfunction "1_1") (pintype "passive"))
    )
    (net (code "99") (name "Net-(C196-Pad1)") (class "Default")
      (node (ref "C196") (pin "1") (pinfunction "1_1") (pintype "passive"))
      (node (ref "L48") (pin "2") (pinfunction "2_2") (pintype "passive"))
      (node (ref "L50") (pin "1") (pinfunction "1_1") (pintype "passive"))
    )
    (net (code "100") (name "Net-(C196-Pad2)") (class "Default")
      (node (ref "C196") (pin "2") (pinfunction "2_2") (pintype "passive"))
      (node (ref "L49") (pin "2") (pinfunction "2_2") (pintype "passive"))
      (node (ref "L51") (pin "1") (pinfunction "1_1") (pintype "passive"))
    )
    (net (code "101") (name "Net-(C269-Pad2)") (class "Default")
      (node (ref "C269") (pin "2") (pinfunction "2_2") (pintype "passive"))
      (node (ref "R168") (pin "2") (pinfunction "2_2") (pintype "passive"))
      (node (ref "R172") (pin "1") (pinfunction "1_1") (pintype "passive"))
    )
    (net (code "102") (name "Net-(C270-Pad2)") (class "Default")
      (node (ref "C270") (pin "2") (pinfunction "2_2") (pintype "passive"))
      (node (ref "R173") (pin "2") (pinfunction "2_2") (pintype "passive"))
      (node (ref "R175") (pin "1") (pinfunction "1_1") (pintype "passive"))
    )
    (net (code "103") (name "Net-(IC1-COMP)") (class "Default")
      (node (ref "IC1") (pin "12") (pinfunction "COMP_12") (pintype "bidirectional"))
      (node (ref "R1") (pin "2") (pinfunction "2_2") (pintype "passive"))
    )
    (net (code "104") (name "Net-(IC1-FB)") (class "Default")
      (node (ref "C9") (pin "2") (pinfunction "2_2") (pintype "passive"))
      (node (ref "IC1") (pin "3") (pinfunction "FB_3") (pintype "bidirectional"))
      (node (ref "R4") (pin "1") (pinfunction "1_1") (pintype "passive"))
      (node (ref "R5") (pin "2") (pinfunction "2_2") (pintype "passive"))
    )
    (net (code "105") (name "Net-(IC1-OVP)") (class "Default")
      (node (ref "IC1") (pin "9") (pinfunction "OVP_9") (pintype "bidirectional"))
      (node (ref "R2") (pin "1") (pinfunction "1_1") (pintype "passive"))
      (node (ref "R3") (pin "2") (pinfunction "2_2") (pintype "passive"))
    )
    (net (code "106") (name "Net-(IC1-SS)") (class "Default")
      (node (ref "C4") (pin "2") (pinfunction "2_2") (pintype "passive"))
      (node (ref "IC1") (pin "2") (pinfunction "SS_2") (pintype "bidirectional"))
    )
    (net (code "107") (name "Net-(IC2A-SW)") (class "Default")
      (node (ref "IC2") (pin "7") (pinfunction "SW_7") (pintype "bidirectional"))
      (node (ref "L2") (pin "P$1") (pinfunction "1_P$1") (pintype "passive"))
    )
    (net (code "108") (name "Net-(IC2B-FB)") (class "Default")
      (node (ref "C11") (pin "1") (pinfunction "1_1") (pintype "passive"))
      (node (ref "C8") (pin "1") (pinfunction "1_1") (pintype "passive"))
      (node (ref "IC2") (pin "16") (pinfunction "FB_16") (pintype "bidirectional"))
      (node (ref "L3") (pin "P$2") (pinfunction "2_P$2") (pintype "passive"))
      (node (ref "L4") (pin "P$1") (pinfunction "1_P$1") (pintype "passive"))
    )
    (net (code "109") (name "Net-(IC2B-SW)") (class "Default")
      (node (ref "IC2") (pin "2") (pinfunction "SW_2") (pintype "bidirectional"))
      (node (ref "L3") (pin "P$1") (pinfunction "1_P$1") (pintype "passive"))
    )
    (net (code "110") (name "Net-(IC3-EN)") (class "Default")
      (node (ref "C16") (pin "1") (pinfunction "1_1") (pintype "passive"))
      (node (ref "C17") (pin "1") (pinfunction "1_1") (pintype "passive"))
      (node (ref "C18") (pin "2") (pinfunction "2_2") (pintype "passive"))
      (node (ref "C19") (pin "2") (pinfunction "2_2") (pintype "passive"))
      (node (ref "C20") (pin "2") (pinfunction "2_2") (pintype "passive"))
      (node (ref "C21") (pin "2") (pinfunction "2_2") (pintype "passive"))
      (node (ref "IC3") (pin "4") (pinfunction "VIN_4") (pintype "bidirectional"))
      (node (ref "IC3") (pin "6") (pinfunction "EN_6") (pintype "bidirectional"))
      (node (ref "IC4") (pin "4") (pinfunction "VIN_4") (pintype "bidirectional"))
      (node (ref "IC4") (pin "6") (pinfunction "EN_6") (pintype "bidirectional"))
      (node (ref "IC5") (pin "4") (pinfunction "VIN_4") (pintype "bidirectional"))
      (node (ref "IC5") (pin "6") (pinfunction "EN_6") (pintype "bidirectional"))
      (node (ref "IC6") (pin "4") (pinfunction "VIN_4") (pintype "bidirectional"))
      (node (ref "IC6") (pin "6") (pinfunction "EN_6") (pintype "bidirectional"))
      (node (ref "L5") (pin "P$2") (pinfunction "2_P$2") (pintype "passive"))
      (node (ref "TP3") (pin "TP") (pinfunction "TP_TP") (pintype "input"))
    )
    (net (code "111") (name "Net-(IC3-SENSE)") (class "Default")
      (node (ref "C22") (pin "2") (pinfunction "2_2") (pintype "passive"))
      (node (ref "IC3") (pin "2") (pinfunction "SENSE_2") (pintype "bidirectional"))
      (node (ref "IC3") (pin "3") (pinfunction "VOUT_3") (pintype "bidirectional"))
      (node (ref "L6") (pin "1") (pinfunction "1_1") (pintype "passive"))
    )
    (net (code "112") (name "Net-(IC4-SENSE)") (class "Default")
      (node (ref "C23") (pin "2") (pinfunction "2_2") (pintype "passive"))
      (node (ref "IC4") (pin "2") (pinfunction "SENSE_2") (pintype "bidirectional"))
      (node (ref "IC4") (pin "3") (pinfunction "VOUT_3") (pintype "bidirectional"))
      (node (ref "L7") (pin "1") (pinfunction "1_1") (pintype "passive"))
    )
    (net (code "113") (name "Net-(IC5-SENSE)") (class "Default")
      (node (ref "C24") (pin "2") (pinfunction "2_2") (pintype "passive"))
      (node (ref "IC5") (pin "2") (pinfunction "SENSE_2") (pintype "bidirectional"))
      (node (ref "IC5") (pin "3") (pinfunction "VOUT_3") (pintype "bidirectional"))
      (node (ref "L8") (pin "1") (pinfunction "1_1") (pintype "passive"))
    )
    (net (code "114") (name "Net-(IC6-SENSE)") (class "Default")
      (node (ref "C25") (pin "2") (pinfunction "2_2") (pintype "passive"))
      (node (ref "IC6") (pin "2") (pinfunction "SENSE_2") (pintype "bidirectional"))
      (node (ref "IC6") (pin "3") (pinfunction "VOUT_3") (pintype "bidirectional"))
      (node (ref "L9") (pin "1") (pinfunction "1_1") (pintype "passive"))
    )
    (net (code "115") (name "Net-(IC7-CLK0)") (class "Default")
      (node (ref "C38") (pin "1") (pinfunction "1_1") (pintype "passive"))
      (node (ref "IC7") (pin "13") (pinfunction "CLK0_13") (pintype "bidirectional"))
      (node (ref "L14") (pin "1") (pinfunction "1_1") (pintype "passive"))
    )
    (net (code "116") (name "Net-(IC7-CLK1)") (class "Default")
      (node (ref "C36") (pin "1") (pinfunction "1_1") (pintype "passive"))
      (node (ref "IC7") (pin "12") (pinfunction "CLK1_12") (pintype "bidirectional"))
      (node (ref "R179") (pin "1") (pinfunction "1_1") (pintype "passive"))
    )
    (net (code "117") (name "Net-(IC7-CLK2)") (class "Default")
      (node (ref "C37") (pin "1") (pinfunction "1_1") (pintype "passive"))
      (node (ref "IC7") (pin "9") (pinfunction "CLK2_9") (pintype "bidirectional"))
      (node (ref "R176") (pin "1") (pinfunction "1_1") (pintype "passive"))
    )
    (net (code "118") (name "Net-(IC7-CLK4)") (class "Default")
      (node (ref "C35") (pin "1") (pinfunction "1_1") (pintype "passive"))
      (node (ref "IC7") (pin "19") (pinfunction "CLK4_19") (pintype "bidirectional"))
      (node (ref "R180") (pin "1") (pinfunction "1_1") (pintype "passive"))
    )
    (net (code "119") (name "Net-(IC7-CLK6)") (class "Default")
      (node (ref "C39") (pin "1") (pinfunction "1_1") (pintype "passive"))
      (node (ref "IC7") (pin "16") (pinfunction "CLK6_16") (pintype "bidirectional"))
    )
    (net (code "120") (name "Net-(IC7-CLKIN)") (class "Default")
      (node (ref "C30") (pin "2") (pinfunction "2_2") (pintype "passive"))
      (node (ref "IC7") (pin "6") (pinfunction "CLKIN_6") (pintype "bidirectional"))
    )
    (net (code "121") (name "Net-(IC7-OEB)") (class "Default")
      (node (ref "IC7") (pin "7") (pinfunction "OEB_7") (pintype "bidirectional"))
      (node (ref "R6") (pin "2") (pinfunction "2_2") (pintype "passive"))
    )
    (net (code "122") (name "Net-(IC7-VDDOA)") (class "Default")
      (node (ref "C32") (pin "2") (pinfunction "2_2") (pintype "passive"))
      (node (ref "C33") (pin "2") (pinfunction "2_2") (pintype "passive"))
      (node (ref "IC7") (pin "10") (pinfunction "VDDOB_10") (pintype "bidirectional"))
      (node (ref "IC7") (pin "11") (pinfunction "VDDOA_11") (pintype "bidirectional"))
      (node (ref "IC7") (pin "14") (pinfunction "VDDOD_14") (pintype "bidirectional"))
      (node (ref "IC7") (pin "18") (pinfunction "VDDOC_18") (pintype "bidirectional"))
      (node (ref "L10") (pin "2") (pinfunction "2_2") (pintype "passive"))
    )
    (net (code "123") (name "Net-(IC7-XA)") (class "Default")
      (node (ref "C34") (pin "1") (pinfunction "1_1") (pintype "passive"))
      (node (ref "IC7") (pin "1") (pinfunction "XA_1") (pintype "bidirectional"))
    )
    (net (code "124") (name "Net-(IC9-VOUT)") (class "Default")
      (node (ref "C52") (pin "1") (pinfunction "1_1") (pintype "passive"))
      (node (ref "IC9") (pin "5") (pinfunction "VOUT_5") (pintype "power_in"))
      (node (ref "L20") (pin "1") (pinfunction "1_1") (pintype "passive"))
    )
    (net (code "125") (name "Net-(IC10-BIAS_FILT)") (class "Default")
      (node (ref "C60") (pin "1") (pinfunction "1_1") (pintype "passive"))
      (node (ref "IC10") (pin "23") (pinfunction "BIAS_FILT_23") (pintype "bidirectional"))
    )
    (net (code "126") (name "Net-(IC10-CE)") (class "Default")
      (node (ref "C268") (pin "1") (pinfunction "1_1") (pintype "passive"))
      (node (ref "IC10") (pin "4") (pinfunction "CE_4") (pintype "bidirectional"))
      (node (ref "R163") (pin "1") (pinfunction "1_1") (pintype "passive"))
    )
    (net (code "127") (name "Net-(IC10-CLK)") (class "Default")
      (node (ref "IC10") (pin "1") (pinfunction "CLK_1") (pintype "input"))
      (node (ref "R164") (pin "1") (pinfunction "1_1") (pintype "passive"))
    )
    (net (code "128") (name "Net-(IC10-CP_OUT)") (class "Default")
      (node (ref "C63") (pin "1") (pinfunction "1_1") (pintype "passive"))
      (node (ref "C66") (pin "1") (pinfunction "1_1") (pintype "passive"))
      (node (ref "IC10") (pin "7") (pinfunction "CP_OUT_7") (pintype "bidirectional"))
      (node (ref "R15") (pin "1") (pinfunction "1_1") (pintype "passive"))
    )
    (net (code "129") (name "Net-(IC10-DATA)") (class "Default")
      (node (ref "IC10") (pin "2") (pinfunction "DATA_2") (pintype "input"))
      (node (ref "R170") (pin "1") (pinfunction "1_1") (pintype "passive"))
    )
    (net (code "130") (name "Net-(IC10-LD)") (class "Default")
      (node (ref "C274") (pin "1") (pinfunction "1_1") (pintype "passive"))
      (node (ref "IC10") (pin "25") (pinfunction "LD_25") (pintype "output"))
      (node (ref "R166") (pin "1") (pinfunction "1_1") (pintype "passive"))
    )
    (net (code "131") (name "Net-(IC10-LE)") (class "Default")
      (node (ref "IC10") (pin "3") (pinfunction "LE_3") (pintype "input"))
      (node (ref "R171") (pin "1") (pinfunction "1_1") (pintype "passive"))
    )
    (net (code "132") (name "Net-(IC10-MUX)") (class "Default")
      (node (ref "IC10") (pin "30") (pinfunction "MUX_30") (pintype "bidirectional"))
      (node (ref "R167") (pin "1") (pinfunction "1_1") (pintype "passive"))
    )
    (net (code "133") (name "Net-(IC10-NOISE_FILT)") (class "Default")
      (node (ref "C59") (pin "1") (pinfunction "1_1") (pintype "passive"))
      (node (ref "IC10") (pin "19") (pinfunction "NOISE_FILT_19") (pintype "bidirectional"))
    )
    (net (code "134") (name "Net-(IC10-REF_IN)") (class "Default")
      (node (ref "C51") (pin "2") (pinfunction "2_2") (pintype "passive"))
      (node (ref "IC10") (pin "29") (pinfunction "REF_IN_29") (pintype "input"))
    )
    (net (code "135") (name "Net-(IC10-REG)") (class "Default")
      (node (ref "C58") (pin "1") (pinfunction "1_1") (pintype "passive"))
      (node (ref "IC10") (pin "24") (pinfunction "REG_24") (pintype "bidirectional"))
    )
    (net (code "136") (name "Net-(IC10-RFOUTA_N)") (class "Default")
      (node (ref "C62") (pin "2") (pinfunction "2_2") (pintype "passive"))
      (node (ref "IC10") (pin "13") (pinfunction "RFOUTA_N_13") (pintype "bidirectional"))
      (node (ref "R13") (pin "1") (pinfunction "1_1") (pintype "passive"))
    )
    (net (code "137") (name "Net-(IC10-RFOUTA_P)") (class "Default")
      (node (ref "C65") (pin "1") (pinfunction "1_1") (pintype "passive"))
      (node (ref "IC10") (pin "12") (pinfunction "RFOUTA_P_12") (pintype "bidirectional"))
      (node (ref "R12") (pin "1") (pinfunction "1_1") (pintype "passive"))
    )
    (net (code "138") (name "Net-(IC10-RFOUT_EN)") (class "Default")
      (node (ref "C272") (pin "1") (pinfunction "1_1") (pintype "passive"))
      (node (ref "IC10") (pin "26") (pinfunction "RFOUT_EN_26") (pintype "input"))
      (node (ref "R165") (pin "1") (pinfunction "1_1") (pintype "passive"))
    )
    (net (code "139") (name "Net-(IC10-RSET)") (class "Default")
      (node (ref "IC10") (pin "22") (pinfunction "RSET_22") (pintype "bidirectional"))
      (node (ref "R10") (pin "2") (pinfunction "2_2") (pintype "passive"))
    )
    (net (code "140") (name "Net-(IC10-SW)") (class "Default")
      (node (ref "IC10") (pin "5") (pinfunction "SW_5") (pintype "bidirectional"))
      (node (ref "R16") (pin "2") (pinfunction "2_2") (pintype "passive"))
      (node (ref "R17") (pin "1") (pinfunction "1_1") (pintype "passive"))
    )
    (net (code "141") (name "Net-(IC10-TUNE)") (class "Default")
      (node (ref "C67") (pin "2") (pinfunction "2_2") (pintype "passive"))
      (node (ref "IC10") (pin "20") (pinfunction "TUNE_20") (pintype "bidirectional"))
      (node (ref "R15") (pin "2") (pinfunction "2_2") (pintype "passive"))
    )
    (net (code "142") (name "Net-(IC10-VCC_DIG)") (class "Default")
      (node (ref "C54") (pin "1") (pinfunction "1_1") (pintype "passive"))
      (node (ref "C55") (pin "1") (pinfunction "1_1") (pintype "passive"))
      (node (ref "IC10") (pin "28") (pinfunction "VCC_DIG_28") (pintype "bidirectional"))
      (node (ref "IC10") (pin "32") (pinfunction "VDD_SD_32") (pintype "bidirectional"))
      (node (ref "L64") (pin "1") (pinfunction "1_1") (pintype "passive"))
    )
    (net (code "143") (name "Net-(IC10-VCC_RF)") (class "Default")
      (node (ref "C56") (pin "1") (pinfunction "1_1") (pintype "passive"))
      (node (ref "C61") (pin "1") (pinfunction "1_1") (pintype "passive"))
      (node (ref "C64") (pin "1") (pinfunction "1_1") (pintype "passive"))
      (node (ref "IC10") (pin "16") (pinfunction "VCC_RF_16") (pintype "bidirectional"))
      (node (ref "IC10") (pin "17") (pinfunction "VCC_VCO_17") (pintype "bidirectional"))
      (node (ref "L19") (pin "2") (pinfunction "2_2") (pintype "passive"))
      (node (ref "R12") (pin "2") (pinfunction "2_2") (pintype "passive"))
      (node (ref "R13") (pin "2") (pinfunction "2_2") (pintype "passive"))
      (node (ref "TP14") (pin "TP") (pinfunction "TP_TP") (pintype "input"))
    )
    (net (code "144") (name "Net-(IC11-ANT)") (class "Default")
      (node (ref "C65") (pin "2") (pinfunction "2_2") (pintype "passive"))
      (node (ref "IC11") (pin "7") (pinfunction "ANT_7") (pintype "bidirectional"))
    )
    (net (code "145") (name "Net-(IC11-C1)") (class "Default")
      (node (ref "IC11") (pin "2") (pinfunction "C1_2") (pintype "bidirectional"))
      (node (ref "R18") (pin "1") (pinfunction "1_1") (pintype "passive"))
      (node (ref "R21") (pin "1") (pinfunction "1_1") (pintype "passive"))
    )
    (net (code "146") (name "Net-(IC11-C2)") (class "Default")
      (node (ref "IC11") (pin "1") (pinfunction "C2_1") (pintype "bidirectional"))
      (node (ref "R19") (pin "1") (pinfunction "1_1") (pintype "passive"))
      (node (ref "R20") (pin "1") (pinfunction "1_1") (pintype "passive"))
    )
    (net (code "147") (name "Net-(IC11-RF1)") (class "Default")
      (node (ref "IC11") (pin "9") (pinfunction "RF1_9") (pintype "bidirectional"))
      (node (ref "IC12") (pin "6") (pinfunction "RF3_6") (pintype "bidirectional"))
    )
    (net (code "148") (name "Net-(IC11-RF2)") (class "Default")
      (node (ref "IC11") (pin "11") (pinfunction "RF2_11") (pintype "bidirectional"))
      (node (ref "LP1") (pin "4") (pinfunction "IN_4") (pintype "bidirectional"))
    )
    (net (code "149") (name "Net-(IC11-RF3)") (class "Default")
      (node (ref "IC11") (pin "6") (pinfunction "RF3_6") (pintype "bidirectional"))
      (node (ref "LP3") (pin "4") (pinfunction "IN_4") (pintype "bidirectional"))
    )
    (net (code "150") (name "Net-(IC11-RF4)") (class "Default")
      (node (ref "IC11") (pin "4") (pinfunction "RF4_4") (pintype "bidirectional"))
      (node (ref "LP2") (pin "4") (pinfunction "IN_4") (pintype "bidirectional"))
    )
    (net (code "151") (name "Net-(IC12-ANT)") (class "Default")
      (node (ref "C68") (pin "1") (pinfunction "1_1") (pintype "passive"))
      (node (ref "IC12") (pin "7") (pinfunction "ANT_7") (pintype "bidirectional"))
    )
    (net (code "152") (name "Net-(IC12-C1)") (class "Default")
      (node (ref "IC12") (pin "2") (pinfunction "C1_2") (pintype "bidirectional"))
      (node (ref "R24") (pin "1") (pinfunction "1_1") (pintype "passive"))
      (node (ref "R25") (pin "1") (pinfunction "1_1") (pintype "passive"))
    )
    (net (code "153") (name "Net-(IC12-C2)") (class "Default")
      (node (ref "IC12") (pin "1") (pinfunction "C2_1") (pintype "bidirectional"))
      (node (ref "R22") (pin "1") (pinfunction "1_1") (pintype "passive"))
      (node (ref "R23") (pin "1") (pinfunction "1_1") (pintype "passive"))
    )
    (net (code "154") (name "Net-(IC12-RF1)") (class "Default")
      (node (ref "IC12") (pin "9") (pinfunction "RF1_9") (pintype "bidirectional"))
      (node (ref "LP3") (pin "1") (pinfunction "OUT_1") (pintype "bidirectional"))
    )
    (net (code "155") (name "Net-(IC12-RF2)") (class "Default")
      (node (ref "IC12") (pin "11") (pinfunction "RF2_11") (pintype "bidirectional"))
      (node (ref "LP2") (pin "1") (pinfunction "OUT_1") (pintype "bidirectional"))
    )
    (net (code "156") (name "Net-(IC12-RF4)") (class "Default")
      (node (ref "IC12") (pin "4") (pinfunction "RF4_4") (pintype "bidirectional"))
      (node (ref "LP1") (pin "1") (pinfunction "OUT_1") (pintype "bidirectional"))
    )
    (net (code "157") (name "Net-(IC13-CTL1)") (class "Default")
      (node (ref "C246") (pin "1") (pinfunction "1_1") (pintype "passive"))
      (node (ref "IC13") (pin "17") (pinfunction "CTL1_17") (pintype "bidirectional"))
      (node (ref "R154") (pin "1") (pinfunction "1_1") (pintype "passive"))
    )
    (net (code "158") (name "Net-(IC13-CTL2)") (class "Default")
      (node (ref "C248") (pin "1") (pinfunction "1_1") (pintype "passive"))
      (node (ref "IC13") (pin "16") (pinfunction "CTL2_16") (pintype "bidirectional"))
      (node (ref "R155") (pin "1") (pinfunction "1_1") (pintype "passive"))
    )
    (net (code "159") (name "Net-(IC13-RF_COM)") (class "Default")
      (node (ref "IC13") (pin "8") (pinfunction "RF_COM_8") (pintype "bidirectional"))
      (node (ref "IC14") (pin "5") (pinfunction "RF1_5") (pintype "bidirectional"))
    )
    (net (code "160") (name "Net-(IC13-VCC)") (class "Default")
      (node (ref "C69") (pin "1") (pinfunction "1_1") (pintype "passive"))
      (node (ref "IC13") (pin "20") (pinfunction "VCC_20") (pintype "bidirectional"))
      (node (ref "L21") (pin "2") (pinfunction "2_2") (pintype "passive"))
    )
    (net (code "161") (name "Net-(IC14-D0)") (class "Default")
      (node (ref "C250") (pin "1") (pinfunction "1_1") (pintype "passive"))
      (node (ref "IC14") (pin "1") (pinfunction "D0_1") (pintype "bidirectional"))
      (node (ref "R156") (pin "1") (pinfunction "1_1") (pintype "passive"))
    )
    (net (code "162") (name "Net-(IC14-D1)") (class "Default")
      (node (ref "C252") (pin "1") (pinfunction "1_1") (pintype "passive"))
      (node (ref "IC14") (pin "24") (pinfunction "D1_24") (pintype "bidirectional"))
      (node (ref "R157") (pin "1") (pinfunction "1_1") (pintype "passive"))
    )
    (net (code "163") (name "Net-(IC14-D2)") (class "Default")
      (node (ref "C254") (pin "1") (pinfunction "1_1") (pintype "passive"))
      (node (ref "IC14") (pin "23") (pinfunction "D2_23") (pintype "bidirectional"))
      (node (ref "R158") (pin "1") (pinfunction "1_1") (pintype "passive"))
    )
    (net (code "164") (name "Net-(IC14-D3)") (class "Default")
      (node (ref "C256") (pin "1") (pinfunction "1_1") (pintype "passive"))
      (node (ref "IC14") (pin "22") (pinfunction "D3_22") (pintype "bidirectional"))
      (node (ref "R159") (pin "1") (pinfunction "1_1") (pintype "passive"))
    )
    (net (code "165") (name "Net-(IC14-D4)") (class "Default")
      (node (ref "C261") (pin "1") (pinfunction "1_1") (pintype "passive"))
      (node (ref "IC14") (pin "21") (pinfunction "D4_21") (pintype "bidirectional"))
      (node (ref "R162") (pin "2") (pinfunction "2_2") (pintype "passive"))
    )
    (net (code "166") (name "Net-(IC14-D5)") (class "Default")
      (node (ref "C259") (pin "1") (pinfunction "1_1") (pintype "passive"))
      (node (ref "IC14") (pin "20") (pinfunction "D5_20") (pintype "bidirectional"))
      (node (ref "R161") (pin "2") (pinfunction "2_2") (pintype "passive"))
    )
    (net (code "167") (name "Net-(IC14-D6)") (class "Default")
      (node (ref "C257") (pin "1") (pinfunction "1_1") (pintype "passive"))
      (node (ref "IC14") (pin "19") (pinfunction "D6_19") (pintype "bidirectional"))
      (node (ref "R160") (pin "2") (pinfunction "2_2") (pintype "passive"))
    )
    (net (code "168") (name "Net-(IC14-LE)") (class "Default")
      (node (ref "C70") (pin "1") (pinfunction "1_1") (pintype "passive"))
      (node (ref "IC14") (pin "16") (pinfunction "LE_16") (pintype "bidirectional"))
      (node (ref "IC14") (pin "2") (pinfunction "VDD_2") (pintype "bidirectional"))
      (node (ref "L22") (pin "2") (pinfunction "2_2") (pintype "passive"))
    )
    (net (code "169") (name "Net-(IC14-RF2)") (class "Default")
      (node (ref "C71") (pin "1") (pinfunction "1_1") (pintype "passive"))
      (node (ref "IC14") (pin "14") (pinfunction "RF2_14") (pintype "bidirectional"))
    )
    (net (code "170") (name "Net-(IC15-PWDN)") (class "Default")
      (node (ref "C244") (pin "1") (pinfunction "1_1") (pintype "passive"))
      (node (ref "IC15") (pin "5") (pinfunction "PWDN_5") (pintype "bidirectional"))
      (node (ref "R153") (pin "1") (pinfunction "1_1") (pintype "passive"))
    )
    (net (code "171") (name "Net-(IC15-RFIN)") (class "Default")
      (node (ref "C71") (pin "2") (pinfunction "2_2") (pintype "passive"))
      (node (ref "IC15") (pin "2") (pinfunction "RFIN_2") (pintype "bidirectional"))
    )
    (net (code "172") (name "Net-(IC15-RFOUT)") (class "Default")
      (node (ref "C74") (pin "1") (pinfunction "1_1") (pintype "passive"))
      (node (ref "IC15") (pin "7") (pinfunction "RFOUT_7") (pintype "bidirectional"))
      (node (ref "L24") (pin "2") (pinfunction "2_2") (pintype "passive"))
    )
    (net (code "173") (name "Net-(IC15-VCC)") (class "Default")
      (node (ref "C72") (pin "1") (pinfunction "1_1") (pintype "passive"))
      (node (ref "C73") (pin "1") (pinfunction "1_1") (pintype "passive"))
      (node (ref "IC15") (pin "1") (pinfunction "VCC_1") (pintype "bidirectional"))
      (node (ref "L11") (pin "1") (pinfunction "1_1") (pintype "passive"))
      (node (ref "L23") (pin "2") (pinfunction "2_2") (pintype "passive"))
    )
    (net (code "174") (name "Net-(IC16-CTL1)") (class "Default")
      (node (ref "C238") (pin "1") (pinfunction "1_1") (pintype "passive"))
      (node (ref "IC16") (pin "17") (pinfunction "CTL1_17") (pintype "bidirectional"))
      (node (ref "R150") (pin "1") (pinfunction "1_1") (pintype "passive"))
    )
    (net (code "175") (name "Net-(IC16-CTL2)") (class "Default")
      (node (ref "C240") (pin "1") (pinfunction "1_1") (pintype "passive"))
      (node (ref "IC16") (pin "16") (pinfunction "CTL2_16") (pintype "bidirectional"))
      (node (ref "R151") (pin "1") (pinfunction "1_1") (pintype "passive"))
    )
    (net (code "176") (name "Net-(IC16-RF1)") (class "Default")
      (node (ref "IC16") (pin "3") (pinfunction "RF1_3") (pintype "bidirectional"))
      (node (ref "IC17") (pin "3") (pinfunction "RF1_3") (pintype "bidirectional"))
    )
    (net (code "177") (name "Net-(IC16-RF2)") (class "Default")
      (node (ref "IC16") (pin "13") (pinfunction "RF2_13") (pintype "bidirectional"))
      (node (ref "IC18") (pin "8") (pinfunction "RF_COM_8") (pintype "bidirectional"))
    )
    (net (code "178") (name "Net-(IC16-RF_COM)") (class "Default")
      (node (ref "IC16") (pin "8") (pinfunction "RF_COM_8") (pintype "bidirectional"))
      (node (ref "R29") (pin "2") (pinfunction "2_2") (pintype "passive"))
    )
    (net (code "179") (name "Net-(IC16-VCC)") (class "Default")
      (node (ref "C75") (pin "1") (pinfunction "1_1") (pintype "passive"))
      (node (ref "IC16") (pin "20") (pinfunction "VCC_20") (pintype "bidirectional"))
      (node (ref "L25") (pin "1") (pinfunction "1_1") (pintype "passive"))
    )
    (net (code "180") (name "Net-(IC17-CTL1)") (class "Default")
      (node (ref "C236") (pin "1") (pinfunction "1_1") (pintype "passive"))
      (node (ref "IC17") (pin "17") (pinfunction "CTL1_17") (pintype "bidirectional"))
      (node (ref "R149") (pin "1") (pinfunction "1_1") (pintype "passive"))
    )
    (net (code "181") (name "Net-(IC17-VCC)") (class "Default")
      (node (ref "C77") (pin "1") (pinfunction "1_1") (pintype "passive"))
      (node (ref "IC17") (pin "20") (pinfunction "VCC_20") (pintype "bidirectional"))
      (node (ref "L26") (pin "2") (pinfunction "2_2") (pintype "passive"))
    )
    (net (code "182") (name "Net-(IC18-CTL1)") (class "Default")
      (node (ref "C242") (pin "1") (pinfunction "1_1") (pintype "passive"))
      (node (ref "IC18") (pin "17") (pinfunction "CTL1_17") (pintype "bidirectional"))
      (node (ref "R152") (pin "1") (pinfunction "1_1") (pintype "passive"))
    )
    (net (code "183") (name "Net-(IC18-VCC)") (class "Default")
      (node (ref "C76") (pin "1") (pinfunction "1_1") (pintype "passive"))
      (node (ref "IC18") (pin "20") (pinfunction "VCC_20") (pintype "bidirectional"))
      (node (ref "L27") (pin "2") (pinfunction "2_2") (pintype "passive"))
    )
    (net (code "184") (name "Net-(IC20-VOUT)") (class "Default")
      (node (ref "C81") (pin "1") (pinfunction "1_1") (pintype "passive"))
      (node (ref "IC20") (pin "5") (pinfunction "VOUT_5") (pintype "power_in"))
      (node (ref "L29") (pin "1") (pinfunction "1_1") (pintype "passive"))
    )
    (net (code "185") (name "Net-(IC21-BIAS_FILT)") (class "Default")
      (node (ref "C89") (pin "1") (pinfunction "1_1") (pintype "passive"))
      (node (ref "IC21") (pin "23") (pinfunction "BIAS_FILT_23") (pintype "bidirectional"))
    )
    (net (code "186") (name "Net-(IC21-CP_OUT)") (class "Default")
      (node (ref "C90") (pin "1") (pinfunction "1_1") (pintype "passive"))
      (node (ref "C92") (pin "1") (pinfunction "1_1") (pintype "passive"))
      (node (ref "IC21") (pin "7") (pinfunction "CP_OUT_7") (pintype "bidirectional"))
      (node (ref "R36") (pin "1") (pinfunction "1_1") (pintype "passive"))
    )
    (net (code "187") (name "Net-(IC21-NOISE_FILT)") (class "Default")
      (node (ref "C88") (pin "1") (pinfunction "1_1") (pintype "passive"))
      (node (ref "IC21") (pin "19") (pinfunction "NOISE_FILT_19") (pintype "bidirectional"))
    )
    (net (code "188") (name "Net-(IC21-REF_IN)") (class "Default")
      (node (ref "C80") (pin "2") (pinfunction "2_2") (pintype "passive"))
      (node (ref "IC21") (pin "29") (pinfunction "REF_IN_29") (pintype "input"))
    )
    (net (code "189") (name "Net-(IC21-REG)") (class "Default")
      (node (ref "C87") (pin "1") (pinfunction "1_1") (pintype "passive"))
      (node (ref "IC21") (pin "24") (pinfunction "REG_24") (pintype "bidirectional"))
    )
    (net (code "190") (name "Net-(IC21-RFOUTB_N)") (class "Default")
      (node (ref "C93") (pin "2") (pinfunction "2_2") (pintype "passive"))
      (node (ref "IC21") (pin "15") (pinfunction "RFOUTB_N_15") (pintype "bidirectional"))
      (node (ref "R35") (pin "1") (pinfunction "1_1") (pintype "passive"))
    )
    (net (code "191") (name "Net-(IC21-RSET)") (class "Default")
      (node (ref "IC21") (pin "22") (pinfunction "RSET_22") (pintype "bidirectional"))
      (node (ref "R30") (pin "2") (pinfunction "2_2") (pintype "passive"))
    )
    (net (code "192") (name "Net-(IC21-SW)") (class "Default")
      (node (ref "IC21") (pin "5") (pinfunction "SW_5") (pintype "bidirectional"))
      (node (ref "R37") (pin "2") (pinfunction "2_2") (pintype "passive"))
      (node (ref "R39") (pin "1") (pinfunction "1_1") (pintype "passive"))
    )
    (net (code "193") (name "Net-(IC21-TUNE)") (class "Default")
      (node (ref "C95") (pin "2") (pinfunction "2_2") (pintype "passive"))
      (node (ref "IC21") (pin "20") (pinfunction "TUNE_20") (pintype "bidirectional"))
      (node (ref "R36") (pin "2") (pinfunction "2_2") (pintype "passive"))
    )
    (net (code "194") (name "Net-(IC21-VCC_CP)") (class "Default")
      (node (ref "C86") (pin "1") (pinfunction "1_1") (pintype "passive"))
      (node (ref "IC21") (pin "10") (pinfunction "VCC_PLL_10") (pintype "bidirectional"))
      (node (ref "IC21") (pin "6") (pinfunction "VCC_CP_6") (pintype "bidirectional"))
      (node (ref "L29") (pin "2") (pinfunction "2_2") (pintype "passive"))
      (node (ref "TP15") (pin "TP") (pinfunction "TP_TP") (pintype "input"))
    )
    (net (code "195") (name "Net-(IC21-VCC_DIG)") (class "Default")
      (node (ref "C83") (pin "1") (pinfunction "1_1") (pintype "passive"))
      (node (ref "C84") (pin "1") (pinfunction "1_1") (pintype "passive"))
      (node (ref "IC21") (pin "28") (pinfunction "VCC_DIG_28") (pintype "bidirectional"))
      (node (ref "IC21") (pin "32") (pinfunction "VDD_SD_32") (pintype "bidirectional"))
      (node (ref "L65") (pin "1") (pinfunction "1_1") (pintype "passive"))
    )
    (net (code "196") (name "Net-(IC21-VCC_RF)") (class "Default")
      (node (ref "C85") (pin "1") (pinfunction "1_1") (pintype "passive"))
      (node (ref "C91") (pin "1") (pinfunction "1_1") (pintype "passive"))
      (node (ref "C94") (pin "1") (pinfunction "1_1") (pintype "passive"))
      (node (ref "IC21") (pin "16") (pinfunction "VCC_RF_16") (pintype "bidirectional"))
      (node (ref "IC21") (pin "17") (pinfunction "VCC_VCO_17") (pintype "bidirectional"))
      (node (ref "L28") (pin "2") (pinfunction "2_2") (pintype "passive"))
      (node (ref "R32") (pin "2") (pinfunction "2_2") (pintype "passive"))
      (node (ref "R33") (pin "2") (pinfunction "2_2") (pintype "passive"))
      (node (ref "R34") (pin "2") (pinfunction "2_2") (pintype "passive"))
      (node (ref "R35") (pin "2") (pinfunction "2_2") (pintype "passive"))
      (node (ref "TP16") (pin "TP") (pinfunction "TP_TP") (pintype "input"))
    )
    (net (code "197") (name "Net-(IC22-IN+)") (class "Default")
      (node (ref "IC22") (pin "3") (pinfunction "IN+_3") (pintype "bidirectional"))
      (node (ref "L30") (pin "1") (pinfunction "1_1") (pintype "passive"))
      (node (ref "R65") (pin "1") (pinfunction "1_1") (pintype "passive"))
      (node (ref "R66") (pin "2") (pinfunction "2_2") (pintype "passive"))
    )
    (net (code "198") (name "Net-(IC22-IN-)") (class "Default")
      (node (ref "IC22") (pin "4") (pinfunction "IN-_4") (pintype "bidirectional"))
      (node (ref "L31") (pin "1") (pinfunction "1_1") (pintype "passive"))
      (node (ref "R64") (pin "1") (pinfunction "1_1") (pintype "passive"))
      (node (ref "R66") (pin "1") (pinfunction "1_1") (pintype "passive"))
    )
    (net (code "199") (name "Net-(IC22-LO+)") (class "Default")
      (node (ref "C98") (pin "2") (pinfunction "2_2") (pintype "passive"))
      (node (ref "IC22") (pin "8") (pinfunction "LO+_8") (pintype "bidirectional"))
    )
    (net (code "200") (name "Net-(IC22-LO-)") (class "Default")
      (node (ref "C97") (pin "2") (pinfunction "2_2") (pintype "passive"))
      (node (ref "IC22") (pin "1") (pinfunction "LO-_1") (pintype "bidirectional"))
    )
    (net (code "201") (name "Net-(IC22-OUT+)") (class "Default")
      (node (ref "C100") (pin "1") (pinfunction "1_1") (pintype "passive"))
      (node (ref "IC22") (pin "6") (pinfunction "OUT+_6") (pintype "bidirectional"))
      (node (ref "R53") (pin "2") (pinfunction "2_2") (pintype "passive"))
    )
    (net (code "202") (name "Net-(IC22-OUT-)") (class "Default")
      (node (ref "C101") (pin "1") (pinfunction "1_1") (pintype "passive"))
      (node (ref "IC22") (pin "5") (pinfunction "OUT-_5") (pintype "bidirectional"))
      (node (ref "R54") (pin "2") (pinfunction "2_2") (pintype "passive"))
    )
    (net (code "203") (name "Net-(IC22-VCC)") (class "Default")
      (node (ref "C102") (pin "2") (pinfunction "2_2") (pintype "passive"))
      (node (ref "C103") (pin "2") (pinfunction "2_2") (pintype "passive"))
      (node (ref "IC22") (pin "7") (pinfunction "VCC_7") (pintype "bidirectional"))
      (node (ref "L12") (pin "1") (pinfunction "1_1") (pintype "passive"))
      (node (ref "R53") (pin "1") (pinfunction "1_1") (pintype "passive"))
      (node (ref "R54") (pin "1") (pinfunction "1_1") (pintype "passive"))
    )
    (net (code "204") (name "Net-(IC23-+IN)") (class "Default")
      (node (ref "C100") (pin "2") (pinfunction "2_2") (pintype "passive"))
      (node (ref "C112") (pin "1") (pinfunction "1_1") (pintype "passive"))
      (node (ref "IC23") (pin "8") (pinfunction "+IN_8") (pintype "input"))
      (node (ref "R55") (pin "1") (pinfunction "1_1") (pintype "passive"))
    )
    (net (code "205") (name "Net-(IC23-+OUT)") (class "Default")
      (node (ref "C113") (pin "1") (pinfunction "1_1") (pintype "passive"))
      (node (ref "IC23") (pin "4") (pinfunction "+OUT_4") (pintype "bidirectional"))
      (node (ref "R56") (pin "1") (pinfunction "1_1") (pintype "passive"))
      (node (ref "R59") (pin "2") (pinfunction "2_2") (pintype "passive"))
    )
    (net (code "206") (name "Net-(IC23--IN)") (class "Default")
      (node (ref "C101") (pin "2") (pinfunction "2_2") (pintype "passive"))
      (node (ref "C113") (pin "2") (pinfunction "2_2") (pintype "passive"))
      (node (ref "IC23") (pin "1") (pinfunction "-IN_1") (pintype "input"))
      (node (ref "R56") (pin "2") (pinfunction "2_2") (pintype "passive"))
    )
    (net (code "207") (name "Net-(IC23--OUT)") (class "Default")
      (node (ref "C112") (pin "2") (pinfunction "2_2") (pintype "passive"))
      (node (ref "IC23") (pin "5") (pinfunction "-OUT_5") (pintype "bidirectional"))
      (node (ref "R55") (pin "2") (pinfunction "2_2") (pintype "passive"))
      (node (ref "R58") (pin "2") (pinfunction "2_2") (pintype "passive"))
    )
    (net (code "208") (name "Net-(IC23-V+)") (class "Default")
      (node (ref "C115") (pin "2") (pinfunction "2_2") (pintype "passive"))
      (node (ref "IC23") (pin "3") (pinfunction "V+_3") (pintype "power_in"))
      (node (ref "L15") (pin "1") (pinfunction "1_1") (pintype "passive"))
    )
    (net (code "209") (name "Net-(IC23-VOCM)") (class "Default")
      (node (ref "C116") (pin "1") (pinfunction "1_1") (pintype "passive"))
      (node (ref "IC23") (pin "2") (pinfunction "VOCM_2") (pintype "output"))
    )
    (net (code "210") (name "Net-(IC24-DETO)") (class "Default")
      (node (ref "IC24") (pin "11") (pinfunction "DETO_11") (pintype "bidirectional"))
      (node (ref "R57") (pin "2") (pinfunction "2_2") (pintype "passive"))
    )
    (net (code "211") (name "Net-(IC24-IN+)") (class "Default")
      (node (ref "C109") (pin "2") (pinfunction "2_2") (pintype "passive"))
      (node (ref "IC24") (pin "15") (pinfunction "IN+_15") (pintype "bidirectional"))
    )
    (net (code "212") (name "Net-(IC24-IN-)") (class "Default")
      (node (ref "C110") (pin "2") (pinfunction "2_2") (pintype "passive"))
      (node (ref "IC24") (pin "16") (pinfunction "IN-_16") (pintype "bidirectional"))
    )
    (net (code "213") (name "Net-(IC24-LO+)") (class "Default")
      (node (ref "C114") (pin "2") (pinfunction "2_2") (pintype "passive"))
      (node (ref "IC24") (pin "3") (pinfunction "LO+_3") (pintype "bidirectional"))
    )
    (net (code "214") (name "Net-(IC24-LO-)") (class "Default")
      (node (ref "C117") (pin "1") (pinfunction "1_1") (pintype "passive"))
      (node (ref "IC24") (pin "4") (pinfunction "LO-_4") (pintype "bidirectional"))
    )
    (net (code "215") (name "Net-(IC24-OUT+)") (class "Default")
      (node (ref "C120") (pin "1") (pinfunction "1_1") (pintype "passive"))
      (node (ref "IC24") (pin "20") (pinfunction "OUT+_20") (pintype "bidirectional"))
      (node (ref "L32") (pin "2") (pinfunction "2_2") (pintype "passive"))
    )
    (net (code "216") (name "Net-(IC24-OUT-)") (class "Default")
      (node (ref "C123") (pin "1") (pinfunction "1_1") (pintype "passive"))
      (node (ref "IC24") (pin "21") (pinfunction "OUT-_21") (pintype "bidirectional"))
      (node (ref "L33") (pin "2") (pinfunction "2_2") (pintype "passive"))
    )
    (net (code "217") (name "Net-(IC24-VPDT)") (class "Default")
      (node (ref "C104") (pin "1") (pinfunction "1_1") (pintype "passive"))
      (node (ref "C105") (pin "1") (pinfunction "1_1") (pintype "passive"))
      (node (ref "C106") (pin "1") (pinfunction "1_1") (pintype "passive"))
      (node (ref "C108") (pin "1") (pinfunction "1_1") (pintype "passive"))
      (node (ref "C111") (pin "1") (pinfunction "1_1") (pintype "passive"))
      (node (ref "IC24") (pin "13") (pinfunction "VPDT_13") (pintype "bidirectional"))
      (node (ref "IC24") (pin "18") (pinfunction "VPRF_18") (pintype "bidirectional"))
      (node (ref "IC24") (pin "24") (pinfunction "VPLO_24") (pintype "bidirectional"))
      (node (ref "IC24") (pin "7") (pinfunction "VPLO_7") (pintype "bidirectional"))
      (node (ref "L17") (pin "1") (pinfunction "1_1") (pintype "passive"))
    )
    (net (code "218") (name "Net-(IC24-VSET)") (class "Default")
      (node (ref "C118") (pin "2") (pinfunction "2_2") (pintype "passive"))
      (node (ref "IC24") (pin "10") (pinfunction "VSET_10") (pintype "bidirectional"))
      (node (ref "R57") (pin "1") (pinfunction "1_1") (pintype "passive"))
      (node (ref "R60") (pin "2") (pinfunction "2_2") (pintype "passive"))
    )
    (net (code "219") (name "Net-(IC25-EN)") (class "Default")
      (node (ref "C129") (pin "1") (pinfunction "1_1") (pintype "passive"))
      (node (ref "IC25") (pin "1") (pinfunction "VIN_1") (pintype "power_in"))
      (node (ref "IC25") (pin "3") (pinfunction "EN_3") (pintype "input"))
      (node (ref "IC26") (pin "1") (pinfunction "VREF_1") (pintype "bidirectional"))
      (node (ref "L13") (pin "1") (pinfunction "1_1") (pintype "passive"))
    )
    (net (code "220") (name "Net-(IC25-VOUT)") (class "Default")
      (node (ref "C131") (pin "1") (pinfunction "1_1") (pintype "passive"))
      (node (ref "IC25") (pin "5") (pinfunction "VOUT_5") (pintype "power_in"))
      (node (ref "IC26") (pin "2") (pinfunction "AVDD_2") (pintype "bidirectional"))
      (node (ref "TP17") (pin "TP") (pinfunction "TP_TP") (pintype "input"))
    )
    (net (code "221") (name "Net-(IC26-AIN+)") (class "Default")
      (node (ref "C125") (pin "2") (pinfunction "2_2") (pintype "passive"))
      (node (ref "C126") (pin "1") (pinfunction "1_1") (pintype "passive"))
      (node (ref "IC26") (pin "3") (pinfunction "AIN+_3") (pintype "bidirectional"))
      (node (ref "R61") (pin "1") (pinfunction "1_1") (pintype "passive"))
    )
    (net (code "222") (name "Net-(IC26-AIN-)") (class "Default")
      (node (ref "C126") (pin "2") (pinfunction "2_2") (pintype "passive"))
      (node (ref "C127") (pin "1") (pinfunction "1_1") (pintype "passive"))
      (node (ref "IC26") (pin "4") (pinfunction "AIN-_4") (pintype "bidirectional"))
      (node (ref "R62") (pin "1") (pinfunction "1_1") (pintype "passive"))
    )
    (net (code "223") (name "Net-(IC27-IN+)") (class "Default")
      (node (ref "IC27") (pin "3") (pinfunction "IN+_3") (pintype "bidirectional"))
      (node (ref "L38") (pin "1") (pinfunction "1_1") (pintype "passive"))
      (node (ref "R92") (pin "1") (pinfunction "1_1") (pintype "passive"))
      (node (ref "R93") (pin "2") (pinfunction "2_2") (pintype "passive"))
    )
    (net (code "224") (name "Net-(IC27-IN-)") (class "Default")
      (node (ref "IC27") (pin "4") (pinfunction "IN-_4") (pintype "bidirectional"))
      (node (ref "L39") (pin "1") (pinfunction "1_1") (pintype "passive"))
      (node (ref "R91") (pin "1") (pinfunction "1_1") (pintype "passive"))
      (node (ref "R93") (pin "1") (pinfunction "1_1") (pintype "passive"))
    )
    (net (code "225") (name "Net-(IC27-LO+)") (class "Default")
      (node (ref "C135") (pin "2") (pinfunction "2_2") (pintype "passive"))
      (node (ref "IC27") (pin "8") (pinfunction "LO+_8") (pintype "bidirectional"))
    )
    (net (code "226") (name "Net-(IC27-LO-)") (class "Default")
      (node (ref "C134") (pin "2") (pinfunction "2_2") (pintype "passive"))
      (node (ref "IC27") (pin "1") (pinfunction "LO-_1") (pintype "bidirectional"))
    )
    (net (code "227") (name "Net-(IC27-OUT+)") (class "Default")
      (node (ref "C137") (pin "1") (pinfunction "1_1") (pintype "passive"))
      (node (ref "IC27") (pin "6") (pinfunction "OUT+_6") (pintype "bidirectional"))
      (node (ref "R80") (pin "2") (pinfunction "2_2") (pintype "passive"))
    )
    (net (code "228") (name "Net-(IC27-OUT-)") (class "Default")
      (node (ref "C138") (pin "1") (pinfunction "1_1") (pintype "passive"))
      (node (ref "IC27") (pin "5") (pinfunction "OUT-_5") (pintype "bidirectional"))
      (node (ref "R81") (pin "2") (pinfunction "2_2") (pintype "passive"))
    )
    (net (code "229") (name "Net-(IC27-VCC)") (class "Default")
      (node (ref "C139") (pin "2") (pinfunction "2_2") (pintype "passive"))
      (node (ref "C140") (pin "2") (pinfunction "2_2") (pintype "passive"))
      (node (ref "IC27") (pin "7") (pinfunction "VCC_7") (pintype "bidirectional"))
      (node (ref "L57") (pin "1") (pinfunction "1_1") (pintype "passive"))
      (node (ref "R80") (pin "1") (pinfunction "1_1") (pintype "passive"))
      (node (ref "R81") (pin "1") (pinfunction "1_1") (pintype "passive"))
    )
    (net (code "230") (name "Net-(IC28-+IN)") (class "Default")
      (node (ref "C137") (pin "2") (pinfunction "2_2") (pintype "passive"))
      (node (ref "C149") (pin "1") (pinfunction "1_1") (pintype "passive"))
      (node (ref "IC28") (pin "8") (pinfunction "+IN_8") (pintype "input"))
      (node (ref "R82") (pin "1") (pinfunction "1_1") (pintype "passive"))
    )
    (net (code "231") (name "Net-(IC28-+OUT)") (class "Default")
      (node (ref "C150") (pin "1") (pinfunction "1_1") (pintype "passive"))
      (node (ref "IC28") (pin "4") (pinfunction "+OUT_4") (pintype "bidirectional"))
      (node (ref "R83") (pin "1") (pinfunction "1_1") (pintype "passive"))
      (node (ref "R86") (pin "2") (pinfunction "2_2") (pintype "passive"))
    )
    (net (code "232") (name "Net-(IC28--IN)") (class "Default")
      (node (ref "C138") (pin "2") (pinfunction "2_2") (pintype "passive"))
      (node (ref "C150") (pin "2") (pinfunction "2_2") (pintype "passive"))
      (node (ref "IC28") (pin "1") (pinfunction "-IN_1") (pintype "input"))
      (node (ref "R83") (pin "2") (pinfunction "2_2") (pintype "passive"))
    )
    (net (code "233") (name "Net-(IC28--OUT)") (class "Default")
      (node (ref "C149") (pin "2") (pinfunction "2_2") (pintype "passive"))
      (node (ref "IC28") (pin "5") (pinfunction "-OUT_5") (pintype "bidirectional"))
      (node (ref "R82") (pin "2") (pinfunction "2_2") (pintype "passive"))
      (node (ref "R85") (pin "2") (pinfunction "2_2") (pintype "passive"))
    )
    (net (code "234") (name "Net-(IC28-V+)") (class "Default")
      (node (ref "C152") (pin "2") (pinfunction "2_2") (pintype "passive"))
      (node (ref "IC28") (pin "3") (pinfunction "V+_3") (pintype "power_in"))
      (node (ref "L56") (pin "1") (pinfunction "1_1") (pintype "passive"))
    )
    (net (code "235") (name "Net-(IC28-VOCM)") (class "Default")
      (node (ref "C153") (pin "1") (pinfunction "1_1") (pintype "passive"))
      (node (ref "IC28") (pin "2") (pinfunction "VOCM_2") (pintype "output"))
    )
    (net (code "236") (name "Net-(IC29-DETO)") (class "Default")
      (node (ref "IC29") (pin "11") (pinfunction "DETO_11") (pintype "bidirectional"))
      (node (ref "R84") (pin "2") (pinfunction "2_2") (pintype "passive"))
    )
    (net (code "237") (name "Net-(IC29-IN+)") (class "Default")
      (node (ref "C146") (pin "2") (pinfunction "2_2") (pintype "passive"))
      (node (ref "IC29") (pin "15") (pinfunction "IN+_15") (pintype "bidirectional"))
    )
    (net (code "238") (name "Net-(IC29-IN-)") (class "Default")
      (node (ref "C147") (pin "2") (pinfunction "2_2") (pintype "passive"))
      (node (ref "IC29") (pin "16") (pinfunction "IN-_16") (pintype "bidirectional"))
    )
    (net (code "239") (name "Net-(IC29-LO+)") (class "Default")
      (node (ref "C151") (pin "2") (pinfunction "2_2") (pintype "passive"))
      (node (ref "IC29") (pin "3") (pinfunction "LO+_3") (pintype "bidirectional"))
    )
    (net (code "240") (name "Net-(IC29-LO-)") (class "Default")
      (node (ref "C154") (pin "1") (pinfunction "1_1") (pintype "passive"))
      (node (ref "IC29") (pin "4") (pinfunction "LO-_4") (pintype "bidirectional"))
    )
    (net (code "241") (name "Net-(IC29-OUT+)") (class "Default")
      (node (ref "C157") (pin "1") (pinfunction "1_1") (pintype "passive"))
      (node (ref "IC29") (pin "20") (pinfunction "OUT+_20") (pintype "bidirectional"))
      (node (ref "L40") (pin "2") (pinfunction "2_2") (pintype "passive"))
    )
    (net (code "242") (name "Net-(IC29-OUT-)") (class "Default")
      (node (ref "C160") (pin "1") (pinfunction "1_1") (pintype "passive"))
      (node (ref "IC29") (pin "21") (pinfunction "OUT-_21") (pintype "bidirectional"))
      (node (ref "L41") (pin "2") (pinfunction "2_2") (pintype "passive"))
    )
    (net (code "243") (name "Net-(IC29-VPDT)") (class "Default")
      (node (ref "C141") (pin "1") (pinfunction "1_1") (pintype "passive"))
      (node (ref "C142") (pin "1") (pinfunction "1_1") (pintype "passive"))
      (node (ref "C143") (pin "1") (pinfunction "1_1") (pintype "passive"))
      (node (ref "C145") (pin "1") (pinfunction "1_1") (pintype "passive"))
      (node (ref "C148") (pin "1") (pinfunction "1_1") (pintype "passive"))
      (node (ref "IC29") (pin "13") (pinfunction "VPDT_13") (pintype "bidirectional"))
      (node (ref "IC29") (pin "18") (pinfunction "VPRF_18") (pintype "bidirectional"))
      (node (ref "IC29") (pin "24") (pinfunction "VPLO_24") (pintype "bidirectional"))
      (node (ref "IC29") (pin "7") (pinfunction "VPLO_7") (pintype "bidirectional"))
      (node (ref "L54") (pin "1") (pinfunction "1_1") (pintype "passive"))
    )
    (net (code "244") (name "Net-(IC29-VSET)") (class "Default")
      (node (ref "C155") (pin "2") (pinfunction "2_2") (pintype "passive"))
      (node (ref "IC29") (pin "10") (pinfunction "VSET_10") (pintype "bidirectional"))
      (node (ref "R84") (pin "1") (pinfunction "1_1") (pintype "passive"))
      (node (ref "R87") (pin "2") (pinfunction "2_2") (pintype "passive"))
    )
    (net (code "245") (name "Net-(IC30-EN)") (class "Default")
      (node (ref "C166") (pin "1") (pinfunction "1_1") (pintype "passive"))
      (node (ref "IC30") (pin "1") (pinfunction "VIN_1") (pintype "power_in"))
      (node (ref "IC30") (pin "3") (pinfunction "EN_3") (pintype "input"))
      (node (ref "IC31") (pin "1") (pinfunction "VREF_1") (pintype "bidirectional"))
      (node (ref "L58") (pin "1") (pinfunction "1_1") (pintype "passive"))
    )
    (net (code "246") (name "Net-(IC30-VOUT)") (class "Default")
      (node (ref "C168") (pin "1") (pinfunction "1_1") (pintype "passive"))
      (node (ref "IC30") (pin "5") (pinfunction "VOUT_5") (pintype "power_in"))
      (node (ref "IC31") (pin "2") (pinfunction "AVDD_2") (pintype "bidirectional"))
      (node (ref "TP18") (pin "TP") (pinfunction "TP_TP") (pintype "input"))
    )
    (net (code "247") (name "Net-(IC31-AIN+)") (class "Default")
      (node (ref "C162") (pin "2") (pinfunction "2_2") (pintype "passive"))
      (node (ref "C163") (pin "1") (pinfunction "1_1") (pintype "passive"))
      (node (ref "IC31") (pin "3") (pinfunction "AIN+_3") (pintype "bidirectional"))
      (node (ref "R88") (pin "1") (pinfunction "1_1") (pintype "passive"))
    )
    (net (code "248") (name "Net-(IC31-AIN-)") (class "Default")
      (node (ref "C163") (pin "2") (pinfunction "2_2") (pintype "passive"))
      (node (ref "C164") (pin "1") (pinfunction "1_1") (pintype "passive"))
      (node (ref "IC31") (pin "4") (pinfunction "AIN-_4") (pintype "bidirectional"))
      (node (ref "R89") (pin "1") (pinfunction "1_1") (pintype "passive"))
    )
    (net (code "249") (name "Net-(IC32-+IN)") (class "Default")
      (node (ref "C173") (pin "1") (pinfunction "1_1") (pintype "passive"))
      (node (ref "C202") (pin "2") (pinfunction "2_2") (pintype "passive"))
      (node (ref "IC32") (pin "8") (pinfunction "+IN_8") (pintype "input"))
      (node (ref "R94") (pin "1") (pinfunction "1_1") (pintype "passive"))
    )
    (net (code "250") (name "Net-(IC32-+OUT)") (class "Default")
      (node (ref "C174") (pin "1") (pinfunction "1_1") (pintype "passive"))
      (node (ref "IC32") (pin "4") (pinfunction "+OUT_4") (pintype "bidirectional"))
      (node (ref "R95") (pin "1") (pinfunction "1_1") (pintype "passive"))
      (node (ref "R97") (pin "2") (pinfunction "2_2") (pintype "passive"))
    )
    (net (code "251") (name "Net-(IC32--IN)") (class "Default")
      (node (ref "C174") (pin "2") (pinfunction "2_2") (pintype "passive"))
      (node (ref "C203") (pin "2") (pinfunction "2_2") (pintype "passive"))
      (node (ref "IC32") (pin "1") (pinfunction "-IN_1") (pintype "input"))
      (node (ref "R95") (pin "2") (pinfunction "2_2") (pintype "passive"))
    )
    (net (code "252") (name "Net-(IC32--OUT)") (class "Default")
      (node (ref "C173") (pin "2") (pinfunction "2_2") (pintype "passive"))
      (node (ref "IC32") (pin "5") (pinfunction "-OUT_5") (pintype "bidirectional"))
      (node (ref "R94") (pin "2") (pinfunction "2_2") (pintype "passive"))
      (node (ref "R96") (pin "2") (pinfunction "2_2") (pintype "passive"))
    )
    (net (code "253") (name "Net-(IC32-V+)") (class "Default")
      (node (ref "C181") (pin "2") (pinfunction "2_2") (pintype "passive"))
      (node (ref "IC32") (pin "3") (pinfunction "V+_3") (pintype "power_in"))
      (node (ref "L62") (pin "1") (pinfunction "1_1") (pintype "passive"))
    )
    (net (code "254") (name "Net-(IC32-VOCM)") (class "Default")
      (node (ref "C182") (pin "1") (pinfunction "1_1") (pintype "passive"))
      (node (ref "IC32") (pin "2") (pinfunction "VOCM_2") (pintype "output"))
    )
    (net (code "255") (name "Net-(IC33-DETO)") (class "Default")
      (node (ref "IC33") (pin "11") (pinfunction "DETO_11") (pintype "bidirectional"))
      (node (ref "R100") (pin "2") (pinfunction "2_2") (pintype "passive"))
    )
    (net (code "256") (name "Net-(IC33-IN+)") (class "Default")
      (node (ref "C178") (pin "2") (pinfunction "2_2") (pintype "passive"))
      (node (ref "IC33") (pin "15") (pinfunction "IN+_15") (pintype "bidirectional"))
    )
    (net (code "257") (name "Net-(IC33-IN-)") (class "Default")
      (node (ref "C179") (pin "2") (pinfunction "2_2") (pintype "passive"))
      (node (ref "IC33") (pin "16") (pinfunction "IN-_16") (pintype "bidirectional"))
    )
    (net (code "258") (name "Net-(IC33-LO+)") (class "Default")
      (node (ref "C183") (pin "2") (pinfunction "2_2") (pintype "passive"))
      (node (ref "IC33") (pin "3") (pinfunction "LO+_3") (pintype "bidirectional"))
    )
    (net (code "259") (name "Net-(IC33-LO-)") (class "Default")
      (node (ref "C185") (pin "1") (pinfunction "1_1") (pintype "passive"))
      (node (ref "IC33") (pin "4") (pinfunction "LO-_4") (pintype "bidirectional"))
    )
    (net (code "260") (name "Net-(IC33-OUT+)") (class "Default")
      (node (ref "C191") (pin "1") (pinfunction "1_1") (pintype "passive"))
      (node (ref "IC33") (pin "20") (pinfunction "OUT+_20") (pintype "bidirectional"))
      (node (ref "L46") (pin "2") (pinfunction "2_2") (pintype "passive"))
    )
    (net (code "261") (name "Net-(IC33-OUT-)") (class "Default")
      (node (ref "C192") (pin "1") (pinfunction "1_1") (pintype "passive"))
      (node (ref "IC33") (pin "21") (pinfunction "OUT-_21") (pintype "bidirectional"))
      (node (ref "L47") (pin "2") (pinfunction "2_2") (pintype "passive"))
    )
    (net (code "262") (name "Net-(IC33-VPDT)") (class "Default")
      (node (ref "C171") (pin "1") (pinfunction "1_1") (pintype "passive"))
      (node (ref "C172") (pin "1") (pinfunction "1_1") (pintype "passive"))
      (node (ref "C175") (pin "1") (pinfunction "1_1") (pintype "passive"))
      (node (ref "C177") (pin "1") (pinfunction "1_1") (pintype "passive"))
      (node (ref "C180") (pin "1") (pinfunction "1_1") (pintype "passive"))
      (node (ref "IC33") (pin "13") (pinfunction "VPDT_13") (pintype "bidirectional"))
      (node (ref "IC33") (pin "18") (pinfunction "VPRF_18") (pintype "bidirectional"))
      (node (ref "IC33") (pin "24") (pinfunction "VPLO_24") (pintype "bidirectional"))
      (node (ref "IC33") (pin "7") (pinfunction "VPLO_7") (pintype "bidirectional"))
      (node (ref "L59") (pin "1") (pinfunction "1_1") (pintype "passive"))
    )
    (net (code "263") (name "Net-(IC33-VSET)") (class "Default")
      (node (ref "C186") (pin "2") (pinfunction "2_2") (pintype "passive"))
      (node (ref "IC33") (pin "10") (pinfunction "VSET_10") (pintype "bidirectional"))
      (node (ref "R100") (pin "1") (pinfunction "1_1") (pintype "passive"))
      (node (ref "R101") (pin "2") (pinfunction "2_2") (pintype "passive"))
    )
    (net (code "264") (name "Net-(IC34-EN)") (class "Default")
      (node (ref "C195") (pin "1") (pinfunction "1_1") (pintype "passive"))
      (node (ref "IC34") (pin "1") (pinfunction "VIN_1") (pintype "power_in"))
      (node (ref "IC34") (pin "3") (pinfunction "EN_3") (pintype "input"))
      (node (ref "IC35") (pin "1") (pinfunction "VREF_1") (pintype "bidirectional"))
      (node (ref "L63") (pin "2") (pinfunction "2_2") (pintype "passive"))
    )
    (net (code "265") (name "Net-(IC34-VOUT)") (class "Default")
      (node (ref "C198") (pin "1") (pinfunction "1_1") (pintype "passive"))
      (node (ref "IC34") (pin "5") (pinfunction "VOUT_5") (pintype "power_in"))
      (node (ref "IC35") (pin "2") (pinfunction "AVDD_2") (pintype "bidirectional"))
      (node (ref "TP19") (pin "TP") (pinfunction "TP_TP") (pintype "input"))
    )
    (net (code "266") (name "Net-(IC35-AIN+)") (class "Default")
      (node (ref "C187") (pin "2") (pinfunction "2_2") (pintype "passive"))
      (node (ref "C188") (pin "1") (pinfunction "1_1") (pintype "passive"))
      (node (ref "IC35") (pin "3") (pinfunction "AIN+_3") (pintype "bidirectional"))
      (node (ref "R98") (pin "1") (pinfunction "1_1") (pintype "passive"))
    )
    (net (code "267") (name "Net-(IC35-AIN-)") (class "Default")
      (node (ref "C188") (pin "2") (pinfunction "2_2") (pintype "passive"))
      (node (ref "C189") (pin "1") (pinfunction "1_1") (pintype "passive"))
      (node (ref "IC35") (pin "4") (pinfunction "AIN-_4") (pintype "bidirectional"))
      (node (ref "R99") (pin "1") (pinfunction "1_1") (pintype "passive"))
    )
    (net (code "268") (name "Net-(IC36-IN+)") (class "Default")
      (node (ref "C197") (pin "2") (pinfunction "2_2") (pintype "passive"))
      (node (ref "IC36") (pin "3") (pinfunction "IN+_3") (pintype "bidirectional"))
      (node (ref "L51") (pin "2") (pinfunction "2_2") (pintype "passive"))
      (node (ref "L53") (pin "1") (pinfunction "1_1") (pintype "passive"))
    )
    (net (code "269") (name "Net-(IC36-IN-)") (class "Default")
      (node (ref "C197") (pin "1") (pinfunction "1_1") (pintype "passive"))
      (node (ref "IC36") (pin "4") (pinfunction "IN-_4") (pintype "bidirectional"))
      (node (ref "L50") (pin "2") (pinfunction "2_2") (pintype "passive"))
      (node (ref "L52") (pin "1") (pinfunction "1_1") (pintype "passive"))
    )
    (net (code "270") (name "Net-(IC36-LO+)") (class "Default")
      (node (ref "C200") (pin "2") (pinfunction "2_2") (pintype "passive"))
      (node (ref "IC36") (pin "8") (pinfunction "LO+_8") (pintype "bidirectional"))
    )
    (net (code "271") (name "Net-(IC36-LO-)") (class "Default")
      (node (ref "C199") (pin "2") (pinfunction "2_2") (pintype "passive"))
      (node (ref "IC36") (pin "1") (pinfunction "LO-_1") (pintype "bidirectional"))
    )
    (net (code "272") (name "Net-(IC36-OUT+)") (class "Default")
      (node (ref "C202") (pin "1") (pinfunction "1_1") (pintype "passive"))
      (node (ref "IC36") (pin "6") (pinfunction "OUT+_6") (pintype "bidirectional"))
      (node (ref "R102") (pin "2") (pinfunction "2_2") (pintype "passive"))
    )
    (net (code "273") (name "Net-(IC36-OUT-)") (class "Default")
      (node (ref "C203") (pin "1") (pinfunction "1_1") (pintype "passive"))
      (node (ref "IC36") (pin "5") (pinfunction "OUT-_5") (pintype "bidirectional"))
      (node (ref "R103") (pin "2") (pinfunction "2_2") (pintype "passive"))
    )
    (net (code "274") (name "Net-(IC36-VCC)") (class "Default")
      (node (ref "C204") (pin "2") (pinfunction "2_2") (pintype "passive"))
      (node (ref "C205") (pin "2") (pinfunction "2_2") (pintype "passive"))
      (node (ref "IC36") (pin "7") (pinfunction "VCC_7") (pintype "bidirectional"))
      (node (ref "L61") (pin "1") (pinfunction "1_1") (pintype "passive"))
      (node (ref "R102") (pin "1") (pinfunction "1_1") (pintype "passive"))
      (node (ref "R103") (pin "1") (pinfunction "1_1") (pintype "passive"))
    )
    (net (code "275") (name "Net-(IC37-PA9)") (class "Default")
      (node (ref "IC37") (pin "31") (pinfunction "PA9_31") (pintype "bidirectional"))
      (node (ref "IC37") (pin "44") (pinfunction "PB6_44") (pintype "bidirectional"))
      (node (ref "J4") (pin "4") (pinfunction "CC1_4") (pintype "bidirectional"))
    )
    (net (code "276") (name "Net-(IC37-PA10)") (class "Default")
      (node (ref "IC37") (pin "32") (pinfunction "PA10_32") (pintype "bidirectional"))
      (node (ref "IC37") (pin "42") (pinfunction "PB4_42") (pintype "bidirectional"))
      (node (ref "J4") (pin "10") (pinfunction "CC2_10") (pintype "bidirectional"))
    )
    (net (code "277") (name "Net-(IC37-PA11)") (class "Default")
      (node (ref "IC37") (pin "33") (pinfunction "PA11_33") (pintype "bidirectional"))
      (node (ref "R118") (pin "2") (pinfunction "2_2") (pintype "passive"))
    )
    (net (code "278") (name "Net-(IC37-PA12)") (class "Default")
      (node (ref "IC37") (pin "34") (pinfunction "PA12_34") (pintype "bidirectional"))
      (node (ref "R119") (pin "1") (pinfunction "1_1") (pintype "passive"))
    )
    (net (code "279") (name "Net-(IC37-PA15)") (class "Default")
      (node (ref "IC37") (pin "38") (pinfunction "PA15_38") (pintype "bidirectional"))
      (node (ref "R120") (pin "2") (pinfunction "2_2") (pintype "passive"))
    )
    (net (code "280") (name "Net-(J4-D+1)") (class "Default")
      (node (ref "J4") (pin "6") (pinfunction "D+1_6") (pintype "bidirectional"))
      (node (ref "J4") (pin "8") (pinfunction "D+2_8") (pintype "bidirectional"))
      (node (ref "R119") (pin "2") (pinfunction "2_2") (pintype "passive"))
    )
    (net (code "281") (name "Net-(J4-D-1)") (class "Default")
      (node (ref "J4") (pin "5") (pinfunction "D-2_5") (pintype "bidirectional"))
      (node (ref "J4") (pin "7") (pinfunction "D-1_7") (pintype "bidirectional"))
      (node (ref "R118") (pin "1") (pinfunction "1_1") (pintype "passive"))
    )
    (net (code "282") (name "Net-(L1-2)") (class "Default")
      (node (ref "D1") (pin "A") (pinfunction "A_A") (pintype "passive"))
      (node (ref "IC1") (pin "7") (pinfunction "SW_7") (pintype "bidirectional"))
      (node (ref "IC1") (pin "8") (pinfunction "SW_8") (pintype "bidirectional"))
      (node (ref "L1") (pin "P$2") (pinfunction "2_P$2") (pintype "passive"))
    )
    (net (code "283") (name "Net-(L5-1)") (class "Default")
      (node (ref "C12") (pin "1") (pinfunction "1_1") (pintype "passive"))
      (node (ref "C13") (pin "1") (pinfunction "1_1") (pintype "passive"))
      (node (ref "C9") (pin "1") (pinfunction "1_1") (pintype "passive"))
      (node (ref "D1") (pin "C") (pinfunction "C_C") (pintype "passive"))
      (node (ref "L5") (pin "P$1") (pinfunction "1_P$1") (pintype "passive"))
      (node (ref "R2") (pin "2") (pinfunction "2_2") (pintype "passive"))
      (node (ref "R4") (pin "2") (pinfunction "2_2") (pintype "passive"))
    )
    (net (code "284") (name "Net-(L11-Pad2)") (class "Default")
      (node (ref "L11") (pin "2") (pinfunction "2_2") (pintype "passive"))
      (node (ref "L24") (pin "1") (pinfunction "1_1") (pintype "passive"))
    )
    (net (code "285") (name "Net-(LED1-PadC)") (class "Default")
      (node (ref "LED1") (pin "C") (pinfunction "C_C") (pintype "passive"))
      (node (ref "R120") (pin "1") (pinfunction "1_1") (pintype "passive"))
    )
    (net (code "286") (name "Net-(LED2-PadC)") (class "Default")
      (node (ref "LED2") (pin "C") (pinfunction "C_C") (pintype "passive"))
      (node (ref "R134") (pin "1") (pinfunction "1_1") (pintype "passive"))
    )
    (net (code "287") (name "Net-(LED3-PadC)") (class "Default")
      (node (ref "LED3") (pin "C") (pinfunction "C_C") (pintype "passive"))
      (node (ref "R135") (pin "1") (pinfunction "1_1") (pintype "passive"))
    )
    (net (code "288") (name "Net-(LED4-PadC)") (class "Default")
      (node (ref "LED4") (pin "C") (pinfunction "C_C") (pintype "passive"))
      (node (ref "R136") (pin "1") (pinfunction "1_1") (pintype "passive"))
    )
    (net (code "289") (name "Net-(LED5-PadC)") (class "Default")
      (node (ref "LED5") (pin "C") (pinfunction "C_C") (pintype "passive"))
      (node (ref "R137") (pin "1") (pinfunction "1_1") (pintype "passive"))
    )
    (net (code "290") (name "Net-(LED6-PadC)") (class "Default")
      (node (ref "LED6") (pin "C") (pinfunction "C_C") (pintype "passive"))
      (node (ref "R138") (pin "1") (pinfunction "1_1") (pintype "passive"))
    )
    (net (code "291") (name "Net-(LED7-PadC)") (class "Default")
      (node (ref "LED7") (pin "C") (pinfunction "C_C") (pintype "passive"))
      (node (ref "R139") (pin "1") (pinfunction "1_1") (pintype "passive"))
    )
    (net (code "292") (name "Net-(LED8-PadC)") (class "Default")
      (node (ref "LED8") (pin "C") (pinfunction "C_C") (pintype "passive"))
      (node (ref "R140") (pin "1") (pinfunction "1_1") (pintype "passive"))
    )
    (net (code "293") (name "Net-(LED9-PadC)") (class "Default")
      (node (ref "LED9") (pin "C") (pinfunction "C_C") (pintype "passive"))
      (node (ref "R141") (pin "1") (pinfunction "1_1") (pintype "passive"))
    )
    (net (code "294") (name "Net-(LED10-PadC)") (class "Default")
      (node (ref "LED10") (pin "C") (pinfunction "C_C") (pintype "passive"))
      (node (ref "R142") (pin "1") (pinfunction "1_1") (pintype "passive"))
    )
    (net (code "295") (name "Net-(Q1-G)") (class "Default")
      (node (ref "J1") (pin "3") (pinfunction "3_3") (pintype "passive"))
      (node (ref "Q1") (pin "1") (pinfunction "G_1") (pintype "passive"))
      (node (ref "Q2") (pin "1") (pinfunction "G_1") (pintype "passive"))
      (node (ref "R125") (pin "1") (pinfunction "1_1") (pintype "passive"))
    )
    (net (code "296") (name "Net-(Q1-S)") (class "Default")
      (node (ref "Q1") (pin "2") (pinfunction "S_2") (pintype "passive"))
      (node (ref "Q2") (pin "2") (pinfunction "S_2") (pintype "passive"))
      (node (ref "R125") (pin "2") (pinfunction "2_2") (pintype "passive"))
    )
    (net (code "297") (name "Net-(R26-Pad2)") (class "Default")
      (node (ref "R26") (pin "2") (pinfunction "2_2") (pintype "passive"))
      (node (ref "R27") (pin "2") (pinfunction "2_2") (pintype "passive"))
      (node (ref "R29") (pin "1") (pinfunction "1_1") (pintype "passive"))
    )
    (net (code "298") (name "Net-(R40-IN)") (class "Default")
      (node (ref "R40") (pin "1") (pinfunction "IN_1") (pintype "bidirectional"))
      (node (ref "R72") (pin "2") (pinfunction "2_2") (pintype "passive"))
      (node (ref "R73") (pin "2") (pinfunction "2_2") (pintype "passive"))
    )
    (net (code "299") (name "Net-(R40-OUT)") (class "Default")
      (node (ref "C133") (pin "2") (pinfunction "2_2") (pintype "passive"))
      (node (ref "R40") (pin "2") (pinfunction "OUT_2") (pintype "bidirectional"))
    )
    (net (code "300") (name "Net-(R47-IN)") (class "Default")
      (node (ref "C136") (pin "2") (pinfunction "2_2") (pintype "passive"))
      (node (ref "R47") (pin "1") (pinfunction "IN_1") (pintype "bidirectional"))
      (node (ref "R47") (pin "2") (pinfunction "OUT_2") (pintype "bidirectional"))
      (node (ref "R72") (pin "1") (pinfunction "1_1") (pintype "passive"))
      (node (ref "T2") (pin "4") (pinfunction "OUT+_4") (pintype "bidirectional"))
    )
    (net (code "301") (name "Net-(R48-IN)") (class "Default")
      (node (ref "C99") (pin "2") (pinfunction "2_2") (pintype "passive"))
      (node (ref "R45") (pin "1") (pinfunction "1_1") (pintype "passive"))
      (node (ref "R48") (pin "1") (pinfunction "IN_1") (pintype "bidirectional"))
      (node (ref "R48") (pin "2") (pinfunction "OUT_2") (pintype "bidirectional"))
      (node (ref "T1") (pin "6") (pinfunction "OUT-_6") (pintype "bidirectional"))
    )
    (net (code "302") (name "Net-(R49-IN)") (class "Default")
      (node (ref "C96") (pin "2") (pinfunction "2_2") (pintype "passive"))
      (node (ref "R49") (pin "1") (pinfunction "IN_1") (pintype "bidirectional"))
    )
    (net (code "303") (name "Net-(R49-OUT)") (class "Default")
      (node (ref "R45") (pin "2") (pinfunction "2_2") (pintype "passive"))
      (node (ref "R46") (pin "2") (pinfunction "2_2") (pintype "passive"))
      (node (ref "R49") (pin "2") (pinfunction "OUT_2") (pintype "bidirectional"))
    )
    (net (code "304") (name "Net-(T1-IN+)") (class "Default")
      (node (ref "C107") (pin "1") (pinfunction "1_1") (pintype "passive"))
      (node (ref "C110") (pin "1") (pinfunction "1_1") (pintype "passive"))
      (node (ref "T1") (pin "3") (pinfunction "IN+_3") (pintype "bidirectional"))
    )
    (net (code "305") (name "Net-(T1-IN-)") (class "Default")
      (node (ref "C107") (pin "2") (pinfunction "2_2") (pintype "passive"))
      (node (ref "C109") (pin "1") (pinfunction "1_1") (pintype "passive"))
      (node (ref "T1") (pin "2") (pinfunction "IN-_2") (pintype "bidirectional"))
    )
    (net (code "306") (name "Net-(T1-OUT+)") (class "Default")
      (node (ref "R46") (pin "1") (pinfunction "1_1") (pintype "passive"))
      (node (ref "R50") (pin "1") (pinfunction "1_1") (pintype "passive"))
      (node (ref "T1") (pin "4") (pinfunction "OUT+_4") (pintype "bidirectional"))
    )
    (net (code "307") (name "Net-(T2-IN+)") (class "Default")
      (node (ref "C144") (pin "1") (pinfunction "1_1") (pintype "passive"))
      (node (ref "C147") (pin "1") (pinfunction "1_1") (pintype "passive"))
      (node (ref "T2") (pin "3") (pinfunction "IN+_3") (pintype "bidirectional"))
    )
    (net (code "308") (name "Net-(T2-IN-)") (class "Default")
      (node (ref "C144") (pin "2") (pinfunction "2_2") (pintype "passive"))
      (node (ref "C146") (pin "1") (pinfunction "1_1") (pintype "passive"))
      (node (ref "T2") (pin "2") (pinfunction "IN-_2") (pintype "bidirectional"))
    )
    (net (code "309") (name "Net-(T2-OUT-)") (class "Default")
      (node (ref "R73") (pin "1") (pinfunction "1_1") (pintype "passive"))
      (node (ref "R76") (pin "1") (pinfunction "1_1") (pintype "passive"))
      (node (ref "T2") (pin "6") (pinfunction "OUT-_6") (pintype "bidirectional"))
    )
    (net (code "310") (name "Net-(T3-IN+)") (class "Default")
      (node (ref "C176") (pin "1") (pinfunction "1_1") (pintype "passive"))
      (node (ref "C179") (pin "1") (pinfunction "1_1") (pintype "passive"))
      (node (ref "T3") (pin "3") (pinfunction "IN+_3") (pintype "bidirectional"))
    )
    (net (code "311") (name "Net-(T3-IN-)") (class "Default")
      (node (ref "C176") (pin "2") (pinfunction "2_2") (pintype "passive"))
      (node (ref "C178") (pin "1") (pinfunction "1_1") (pintype "passive"))
      (node (ref "T3") (pin "2") (pinfunction "IN-_2") (pintype "bidirectional"))
    )
    (net (code "312") (name "Net-(T3-OUT-)") (class "Default")
      (node (ref "C170") (pin "2") (pinfunction "2_2") (pintype "passive"))
      (node (ref "T3") (pin "6") (pinfunction "OUT-_6") (pintype "bidirectional"))
    )
    (net (code "313") (name "Net-(U1-CLK)") (class "Default")
      (node (ref "R104") (pin "2") (pinfunction "2_2") (pintype "passive"))
      (node (ref "R111") (pin "1") (pinfunction "1_1") (pintype "passive"))
      (node (ref "U1") (pin "6") (pinfunction "CLK_6") (pintype "input"))
    )
    (net (code "314") (name "Net-(U1-DI)") (class "Default")
      (node (ref "R105") (pin "2") (pinfunction "2_2") (pintype "passive"))
      (node (ref "R112") (pin "1") (pinfunction "1_1") (pintype "passive"))
      (node (ref "U1") (pin "5") (pinfunction "DI_5") (pintype "input"))
    )
    (net (code "315") (name "Net-(U1-DO)") (class "Default")
      (node (ref "R106") (pin "2") (pinfunction "2_2") (pintype "passive"))
      (node (ref "R113") (pin "1") (pinfunction "1_1") (pintype "passive"))
      (node (ref "U1") (pin "2") (pinfunction "DO_2") (pintype "output"))
    )
    (net (code "316") (name "Net-(U1-~{CS})") (class "Default")
      (node (ref "R107") (pin "2") (pinfunction "2_2") (pintype "passive"))
      (node (ref "R114") (pin "1") (pinfunction "1_1") (pintype "passive"))
      (node (ref "U1") (pin "1") (pinfunction "~{CS}_1") (pintype "input"))
    )
    (net (code "317") (name "Net-(U2A-IO_L1N_VREF_0)") (class "Default")
      (node (ref "C223") (pin "1") (pinfunction "1_1") (pintype "passive"))
      (node (ref "R133") (pin "2") (pinfunction "2_2") (pintype "passive"))
      (node (ref "R143") (pin "2") (pinfunction "2_2") (pintype "passive"))
      (node (ref "U2") (pin "P143") (pinfunction "IO_L1N_VREF_0_P143") (pintype "bidirectional"))
    )
    (net (code "318") (name "Net-(U2A-IO_L1P_HSWAPEN_0)") (class "Default")
      (node (ref "C225") (pin "1") (pinfunction "1_1") (pintype "passive"))
      (node (ref "R132") (pin "1") (pinfunction "1_1") (pintype "passive"))
      (node (ref "R144") (pin "1") (pinfunction "1_1") (pintype "passive"))
      (node (ref "U2") (pin "P144") (pinfunction "IO_L1P_HSWAPEN_0_P144") (pintype "bidirectional"))
    )
    (net (code "319") (name "Net-(U2A-IO_L2N_0)") (class "Default")
      (node (ref "C229") (pin "1") (pinfunction "1_1") (pintype "passive"))
      (node (ref "R130") (pin "1") (pinfunction "1_1") (pintype "passive"))
      (node (ref "R146") (pin "1") (pinfunction "1_1") (pintype "passive"))
      (node (ref "U2") (pin "P141") (pinfunction "IO_L2N_0_P141") (pintype "bidirectional"))
    )
    (net (code "320") (name "Net-(U2A-IO_L3P_0)") (class "Default")
      (node (ref "C227") (pin "1") (pinfunction "1_1") (pintype "passive"))
      (node (ref "R131") (pin "2") (pinfunction "2_2") (pintype "passive"))
      (node (ref "R145") (pin "2") (pinfunction "2_2") (pintype "passive"))
      (node (ref "U2") (pin "P140") (pinfunction "IO_L3P_0_P140") (pintype "bidirectional"))
    )
    (net (code "321") (name "Net-(U2A-IO_L34N_GCLK18_0)") (class "Default")
      (node (ref "JP2") (pin "4") (pinfunction "4_4") (pintype "passive"))
      (node (ref "U2") (pin "P133") (pinfunction "IO_L34N_GCLK18_0_P133") (pintype "bidirectional"))
    )
    (net (code "322") (name "Net-(U2A-IO_L34P_GCLK19_0)") (class "Default")
      (node (ref "JP2") (pin "2") (pinfunction "2_2") (pintype "passive"))
      (node (ref "U2") (pin "P134") (pinfunction "IO_L34P_GCLK19_0_P134") (pintype "bidirectional"))
    )
    (net (code "323") (name "Net-(U2A-IO_L35N_GCLK16_0)") (class "Default")
      (node (ref "JP2") (pin "6") (pinfunction "6_6") (pintype "passive"))
      (node (ref "U2") (pin "P131") (pinfunction "IO_L35N_GCLK16_0_P131") (pintype "bidirectional"))
    )
    (net (code "324") (name "Net-(U2A-IO_L35P_GCLK17_0)") (class "Default")
      (node (ref "JP2") (pin "3") (pinfunction "3_3") (pintype "passive"))
      (node (ref "U2") (pin "P132") (pinfunction "IO_L35P_GCLK17_0_P132") (pintype "bidirectional"))
    )
    (net (code "325") (name "Net-(U2A-IO_L36N_GCLK14_0)") (class "Default")
      (node (ref "JP2") (pin "8") (pinfunction "8_8") (pintype "passive"))
      (node (ref "U2") (pin "P126") (pinfunction "IO_L36N_GCLK14_0_P126") (pintype "bidirectional"))
    )
    (net (code "326") (name "Net-(U2A-IO_L36P_GCLK15_0)") (class "Default")
      (node (ref "JP2") (pin "5") (pinfunction "5_5") (pintype "passive"))
      (node (ref "U2") (pin "P127") (pinfunction "IO_L36P_GCLK15_0_P127") (pintype "bidirectional"))
    )
    (net (code "327") (name "Net-(U2A-IO_L37N_GCLK12_0)") (class "Default")
      (node (ref "JP2") (pin "10") (pinfunction "10_10") (pintype "passive"))
      (node (ref "U2") (pin "P123") (pinfunction "IO_L37N_GCLK12_0_P123") (pintype "bidirectional"))
    )
    (net (code "328") (name "Net-(U2A-IO_L37P_GCLK13_0)") (class "Default")
      (node (ref "JP2") (pin "7") (pinfunction "7_7") (pintype "passive"))
      (node (ref "U2") (pin "P124") (pinfunction "IO_L37P_GCLK13_0_P124") (pintype "bidirectional"))
    )
    (net (code "329") (name "Net-(U2A-IO_L62N_VREF_0)") (class "Default")
      (node (ref "JP2") (pin "12") (pinfunction "12_12") (pintype "passive"))
      (node (ref "U2") (pin "P120") (pinfunction "IO_L62N_VREF_0_P120") (pintype "bidirectional"))
    )
    (net (code "330") (name "Net-(U2A-IO_L62P_0)") (class "Default")
      (node (ref "JP2") (pin "9") (pinfunction "9_9") (pintype "passive"))
      (node (ref "U2") (pin "P121") (pinfunction "IO_L62P_0_P121") (pintype "bidirectional"))
    )
    (net (code "331") (name "Net-(U2A-IO_L63N_SCP6_0)") (class "Default")
      (node (ref "JP2") (pin "14") (pinfunction "14_14") (pintype "passive"))
      (node (ref "U2") (pin "P118") (pinfunction "IO_L63N_SCP6_0_P118") (pintype "bidirectional"))
    )
    (net (code "332") (name "Net-(U2A-IO_L63P_SCP7_0)") (class "Default")
      (node (ref "JP2") (pin "11") (pinfunction "11_11") (pintype "passive"))
      (node (ref "U2") (pin "P119") (pinfunction "IO_L63P_SCP7_0_P119") (pintype "bidirectional"))
    )
    (net (code "333") (name "Net-(U2A-IO_L64N_SCP4_0)") (class "Default")
      (node (ref "JP2") (pin "16") (pinfunction "16_16") (pintype "passive"))
      (node (ref "U2") (pin "P116") (pinfunction "IO_L64N_SCP4_0_P116") (pintype "bidirectional"))
    )
    (net (code "334") (name "Net-(U2A-IO_L64P_SCP5_0)") (class "Default")
      (node (ref "JP2") (pin "13") (pinfunction "13_13") (pintype "passive"))
      (node (ref "U2") (pin "P117") (pinfunction "IO_L64P_SCP5_0_P117") (pintype "bidirectional"))
    )
    (net (code "335") (name "Net-(U2A-IO_L65N_SCP2_0)") (class "Default")
      (node (ref "JP2") (pin "18") (pinfunction "18_18") (pintype "passive"))
      (node (ref "U2") (pin "P114") (pinfunction "IO_L65N_SCP2_0_P114") (pintype "bidirectional"))
    )
    (net (code "336") (name "Net-(U2A-IO_L65P_SCP3_0)") (class "Default")
      (node (ref "JP2") (pin "15") (pinfunction "15_15") (pintype "passive"))
      (node (ref "U2") (pin "P115") (pinfunction "IO_L65P_SCP3_0_P115") (pintype "bidirectional"))
    )
    (net (code "337") (name "Net-(U2A-IO_L66N_SCP0_0)") (class "Default")
      (node (ref "JP2") (pin "19") (pinfunction "19_19") (pintype "passive"))
      (node (ref "U2") (pin "P111") (pinfunction "IO_L66N_SCP0_0_P111") (pintype "bidirectional"))
    )
    (net (code "338") (name "Net-(U2A-IO_L66P_SCP1_0)") (class "Default")
      (node (ref "JP2") (pin "17") (pinfunction "17_17") (pintype "passive"))
      (node (ref "U2") (pin "P112") (pinfunction "IO_L66P_SCP1_0_P112") (pintype "bidirectional"))
    )
    (net (code "339") (name "Net-(U2B-IO_L41N_GCLK8_1)") (class "Default")
      (node (ref "R135") (pin "2") (pinfunction "2_2") (pintype "passive"))
      (node (ref "U2") (pin "P92") (pinfunction "IO_L41N_GCLK8_1_P92") (pintype "bidirectional"))
    )
    (net (code "340") (name "Net-(U2B-IO_L41P_GCLK9_IRDY1_1)") (class "Default")
      (node (ref "R136") (pin "2") (pinfunction "2_2") (pintype "passive"))
      (node (ref "U2") (pin "P93") (pinfunction "IO_L41P_GCLK9_IRDY1_1_P93") (pintype "bidirectional"))
    )
    (net (code "341") (name "Net-(U2B-IO_L42N_GCLK6_TRDY1_1)") (class "Default")
      (node (ref "R138") (pin "2") (pinfunction "2_2") (pintype "passive"))
      (node (ref "U2") (pin "P87") (pinfunction "IO_L42N_GCLK6_TRDY1_1_P87") (pintype "bidirectional"))
    )
    (net (code "342") (name "Net-(U2B-IO_L42P_GCLK7_1)") (class "Default")
      (node (ref "R137") (pin "2") (pinfunction "2_2") (pintype "passive"))
      (node (ref "U2") (pin "P88") (pinfunction "IO_L42P_GCLK7_1_P88") (pintype "bidirectional"))
    )
    (net (code "343") (name "Net-(U2B-IO_L43N_GCLK4_1)") (class "Default")
      (node (ref "R140") (pin "2") (pinfunction "2_2") (pintype "passive"))
      (node (ref "U2") (pin "P84") (pinfunction "IO_L43N_GCLK4_1_P84") (pintype "bidirectional"))
    )
    (net (code "344") (name "Net-(U2B-IO_L43P_GCLK5_1)") (class "Default")
      (node (ref "R139") (pin "2") (pinfunction "2_2") (pintype "passive"))
      (node (ref "U2") (pin "P85") (pinfunction "IO_L43P_GCLK5_1_P85") (pintype "bidirectional"))
    )
    (net (code "345") (name "Net-(U2B-IO_L45N_1)") (class "Default")
      (node (ref "R142") (pin "2") (pinfunction "2_2") (pintype "passive"))
      (node (ref "U2") (pin "P82") (pinfunction "IO_L45N_1_P82") (pintype "bidirectional"))
    )
    (net (code "346") (name "Net-(U2B-IO_L45P_1)") (class "Default")
      (node (ref "R141") (pin "2") (pinfunction "2_2") (pintype "passive"))
      (node (ref "U2") (pin "P83") (pinfunction "IO_L45P_1_P83") (pintype "bidirectional"))
    )
    (net (code "347") (name "Net-(U2C-IO_L14N_D12_2)") (class "Default")
      (node (ref "C232") (pin "1") (pinfunction "1_1") (pintype "passive"))
      (node (ref "R122") (pin "2") (pinfunction "2_2") (pintype "passive"))
      (node (ref "R147") (pin "1") (pinfunction "1_1") (pintype "passive"))
      (node (ref "U2") (pin "P57") (pinfunction "IO_L14N_D12_2_P57") (pintype "bidirectional"))
    )
    (net (code "348") (name "Net-(U2C-IO_L14P_D11_2)") (class "Default")
      (node (ref "C234") (pin "1") (pinfunction "1_1") (pintype "passive"))
      (node (ref "R121") (pin "1") (pinfunction "1_1") (pintype "passive"))
      (node (ref "R148") (pin "2") (pinfunction "2_2") (pintype "passive"))
      (node (ref "U2") (pin "P58") (pinfunction "IO_L14P_D11_2_P58") (pintype "bidirectional"))
    )
    (net (code "349") (name "Net-(U2C-IO_L31N_GCLK30_D15_2)") (class "Default")
      (node (ref "R126") (pin "2") (pinfunction "2_2") (pintype "passive"))
      (node (ref "U2") (pin "P50") (pinfunction "IO_L31N_GCLK30_D15_2_P50") (pintype "bidirectional"))
    )
    (net (code "350") (name "Net-(U2C-IO_L62N_D6_2)") (class "Default")
      (node (ref "R123") (pin "2") (pinfunction "2_2") (pintype "passive"))
      (node (ref "U2") (pin "P43") (pinfunction "IO_L62N_D6_2_P43") (pintype "bidirectional"))
    )
    (net (code "351") (name "Net-(U2C-IO_L64P_D8_2)") (class "Default")
      (node (ref "R124") (pin "2") (pinfunction "2_2") (pintype "passive"))
      (node (ref "U2") (pin "P41") (pinfunction "IO_L64P_D8_2_P41") (pintype "bidirectional"))
    )
    (net (code "352") (name "Net-(Y1-OUT)") (class "Default")
      (node (ref "C34") (pin "2") (pinfunction "2_2") (pintype "passive"))
      (node (ref "Y1") (pin "3") (pinfunction "OUT_3") (pintype "output"))
    )
    (net (code "353") (name "PORT1LO1") (class "Default")
      (node (ref "C269") (pin "1") (pinfunction "1_1") (pintype "passive"))
      (node (ref "IC21") (pin "12") (pinfunction "RFOUTA_P_12") (pintype "bidirectional"))
      (node (ref "R32") (pin "1") (pinfunction "1_1") (pintype "passive"))
    )
    (net (code "354") (name "PORT1LO2") (class "Default")
      (node (ref "C46") (pin "1") (pinfunction "1_1") (pintype "passive"))
      (node (ref "C98") (pin "1") (pinfunction "1_1") (pintype "passive"))
      (node (ref "R177") (pin "2") (pinfunction "2_2") (pintype "passive"))
    )
    (net (code "355") (name "PORT1MIX1_EN") (class "Default")
      (node (ref "C230") (pin "1") (pinfunction "1_1") (pintype "passive"))
      (node (ref "IC24") (pin "9") (pinfunction "ENBL_9") (pintype "bidirectional"))
      (node (ref "R146") (pin "2") (pinfunction "2_2") (pintype "passive"))
    )
    (net (code "356") (name "PORT1MIX2_EN") (class "Default")
      (node (ref "C228") (pin "1") (pinfunction "1_1") (pintype "passive"))
      (node (ref "IC22") (pin "2") (pinfunction "EN_2") (pintype "bidirectional"))
      (node (ref "IC23") (pin "7") (pinfunction "SHDN_7") (pintype "bidirectional"))
      (node (ref "R145") (pin "1") (pinfunction "1_1") (pintype "passive"))
    )
    (net (code "357") (name "PORT1SRC") (class "Default")
      (node (ref "C96") (pin "1") (pinfunction "1_1") (pintype "passive"))
      (node (ref "IC18") (pin "3") (pinfunction "RF1_3") (pintype "bidirectional"))
    )
    (net (code "358") (name "PORT1SWITCH") (class "Default")
      (node (ref "C241") (pin "1") (pinfunction "1_1") (pintype "passive"))
      (node (ref "R152") (pin "2") (pinfunction "2_2") (pintype "passive"))
      (node (ref "U2") (pin "P142") (pinfunction "IO_L2P_0_P142") (pintype "bidirectional"))
    )
    (net (code "359") (name "PORT1_CONVSTART") (class "Default")
      (node (ref "IC26") (pin "6") (pinfunction "CONVST_6") (pintype "bidirectional"))
      (node (ref "U2") (pin "P139") (pinfunction "IO_L3N_0_P139") (pintype "bidirectional"))
    )
    (net (code "360") (name "PORT1_SCLK") (class "Default")
      (node (ref "IC26") (pin "8") (pinfunction "SCLK_8") (pintype "bidirectional"))
      (node (ref "U2") (pin "P137") (pinfunction "IO_L4N_0_P137") (pintype "bidirectional"))
    )
    (net (code "361") (name "PORT1_SDO") (class "Default")
      (node (ref "IC26") (pin "7") (pinfunction "SDO_7") (pintype "bidirectional"))
      (node (ref "U2") (pin "P138") (pinfunction "IO_L4P_0_P138") (pintype "bidirectional"))
    )
    (net (code "362") (name "PORT2LO1") (class "Default")
      (node (ref "C151") (pin "1") (pinfunction "1_1") (pintype "passive"))
      (node (ref "IC21") (pin "14") (pinfunction "RFOUTB_P_14") (pintype "bidirectional"))
      (node (ref "R34") (pin "1") (pinfunction "1_1") (pintype "passive"))
    )
    (net (code "363") (name "PORT2LO2") (class "Default")
      (node (ref "C135") (pin "1") (pinfunction "1_1") (pintype "passive"))
      (node (ref "C44") (pin "1") (pinfunction "1_1") (pintype "passive"))
      (node (ref "R181") (pin "2") (pinfunction "2_2") (pintype "passive"))
    )
    (net (code "364") (name "PORT2MIX1_EN") (class "Default")
      (node (ref "C233") (pin "1") (pinfunction "1_1") (pintype "passive"))
      (node (ref "IC29") (pin "9") (pinfunction "ENBL_9") (pintype "bidirectional"))
      (node (ref "R148") (pin "1") (pinfunction "1_1") (pintype "passive"))
    )
    (net (code "365") (name "PORT2MIX2_EN") (class "Default")
      (node (ref "C231") (pin "1") (pinfunction "1_1") (pintype "passive"))
      (node (ref "IC27") (pin "2") (pinfunction "EN_2") (pintype "bidirectional"))
      (node (ref "IC28") (pin "7") (pinfunction "SHDN_7") (pintype "bidirectional"))
      (node (ref "R147") (pin "2") (pinfunction "2_2") (pintype "passive"))
    )
    (net (code "366") (name "PORT2SRC") (class "Default")
      (node (ref "C133") (pin "1") (pinfunction "1_1") (pintype "passive"))
      (node (ref "IC17") (pin "8") (pinfunction "RF_COM_8") (pintype "bidirectional"))
    )
    (net (code "367") (name "PORT2SWITCH") (class "Default")
      (node (ref "C235") (pin "1") (pinfunction "1_1") (pintype "passive"))
      (node (ref "R149") (pin "2") (pinfunction "2_2") (pintype "passive"))
      (node (ref "U2") (pin "P40") (pinfunction "IO_L64N_D9_2_P40") (pintype "bidirectional"))
    )
    (net (code "368") (name "PORT2_CONVSTART") (class "Default")
      (node (ref "IC31") (pin "6") (pinfunction "CONVST_6") (pintype "bidirectional"))
      (node (ref "U2") (pin "P44") (pinfunction "IO_L62P_D5_2_P44") (pintype "bidirectional"))
    )
    (net (code "369") (name "PORT2_SCLK") (class "Default")
      (node (ref "IC31") (pin "8") (pinfunction "SCLK_8") (pintype "bidirectional"))
      (node (ref "R124") (pin "1") (pinfunction "1_1") (pintype "passive"))
    )
    (net (code "370") (name "PORT2_SDO") (class "Default")
      (node (ref "IC31") (pin "7") (pinfunction "SDO_7") (pintype "bidirectional"))
      (node (ref "R123") (pin "1") (pinfunction "1_1") (pintype "passive"))
    )
    (net (code "371") (name "PORTSWITCH1") (class "Default")
      (node (ref "C239") (pin "1") (pinfunction "1_1") (pintype "passive"))
      (node (ref "R151") (pin "2") (pinfunction "2_2") (pintype "passive"))
      (node (ref "U2") (pin "P6") (pinfunction "IO_L52P_3_P6") (pintype "bidirectional"))
    )
    (net (code "372") (name "PORTSWITCH2") (class "Default")
      (node (ref "C237") (pin "1") (pinfunction "1_1") (pintype "passive"))
      (node (ref "R150") (pin "2") (pinfunction "2_2") (pintype "passive"))
      (node (ref "U2") (pin "P7") (pinfunction "IO_L51N_3_P7") (pintype "bidirectional"))
    )
    (net (code "373") (name "REFLO1") (class "Default")
      (node (ref "C270") (pin "1") (pinfunction "1_1") (pintype "passive"))
      (node (ref "IC21") (pin "13") (pinfunction "RFOUTA_N_13") (pintype "bidirectional"))
      (node (ref "R33") (pin "1") (pinfunction "1_1") (pintype "passive"))
    )
    (net (code "374") (name "REFLO2") (class "Default")
      (node (ref "C200") (pin "1") (pinfunction "1_1") (pintype "passive"))
      (node (ref "C45") (pin "1") (pinfunction "1_1") (pintype "passive"))
      (node (ref "R178") (pin "2") (pinfunction "2_2") (pintype "passive"))
    )
    (net (code "375") (name "REFMIX1_EN") (class "Default")
      (node (ref "C226") (pin "1") (pinfunction "1_1") (pintype "passive"))
      (node (ref "IC33") (pin "9") (pinfunction "ENBL_9") (pintype "bidirectional"))
      (node (ref "R144") (pin "2") (pinfunction "2_2") (pintype "passive"))
    )
    (net (code "376") (name "REFMIX2_EN") (class "Default")
      (node (ref "C224") (pin "1") (pinfunction "1_1") (pintype "passive"))
      (node (ref "IC32") (pin "7") (pinfunction "SHDN_7") (pintype "bidirectional"))
      (node (ref "IC36") (pin "2") (pinfunction "EN_2") (pintype "bidirectional"))
      (node (ref "R143") (pin "1") (pinfunction "1_1") (pintype "passive"))
    )
    (net (code "377") (name "REFSRC") (class "Default")
      (node (ref "C170") (pin "1") (pinfunction "1_1") (pintype "passive"))
      (node (ref "R27") (pin "1") (pinfunction "1_1") (pintype "passive"))
      (node (ref "R28") (pin "2") (pinfunction "2_2") (pintype "passive"))
    )
    (net (code "378") (name "REF_CONVSTART") (class "Default")
      (node (ref "IC35") (pin "6") (pinfunction "CONVST_6") (pintype "bidirectional"))
      (node (ref "U2") (pin "P5") (pinfunction "IO_L52N_3_P5") (pintype "bidirectional"))
    )
    (net (code "379") (name "REF_SCLK") (class "Default")
      (node (ref "IC35") (pin "8") (pinfunction "SCLK_8") (pintype "bidirectional"))
      (node (ref "U2") (pin "P1") (pinfunction "IO_L83N_VREF_3_P1") (pintype "bidirectional"))
    )
    (net (code "380") (name "REF_SDO") (class "Default")
      (node (ref "IC35") (pin "7") (pinfunction "SDO_7") (pintype "bidirectional"))
      (node (ref "U2") (pin "P2") (pinfunction "IO_L83P_3_P2") (pintype "bidirectional"))
    )
    (net (code "381") (name "SCL") (class "Default")
      (node (ref "IC2") (pin "11") (pinfunction "SCL_11") (pintype "bidirectional"))
      (node (ref "IC37") (pin "16") (pinfunction "PC4_16") (pintype "bidirectional"))
      (node (ref "IC7") (pin "4") (pinfunction "SCL_4") (pintype "bidirectional"))
      (node (ref "R116") (pin "1") (pinfunction "1_1") (pintype "passive"))
    )
    (net (code "382") (name "SDA") (class "Default")
      (node (ref "IC2") (pin "10") (pinfunction "SDA_10") (pintype "bidirectional"))
      (node (ref "IC37") (pin "30") (pinfunction "PA8_30") (pintype "bidirectional"))
      (node (ref "IC7") (pin "5") (pinfunction "SDA_5") (pintype "bidirectional"))
      (node (ref "R117") (pin "1") (pinfunction "1_1") (pintype "passive"))
    )
    (net (code "383") (name "SOURCE_CE") (class "Default")
      (node (ref "C267") (pin "1") (pinfunction "1_1") (pintype "passive"))
      (node (ref "R11") (pin "2") (pinfunction "2_2") (pintype "passive"))
      (node (ref "R163") (pin "2") (pinfunction "2_2") (pintype "passive"))
      (node (ref "U2") (pin "P27") (pinfunction "IO_L37P_3_P27") (pintype "bidirectional"))
    )
    (net (code "384") (name "SOURCE_CLK") (class "Default")
      (node (ref "R164") (pin "2") (pinfunction "2_2") (pintype "passive"))
      (node (ref "U2") (pin "P32") (pinfunction "IO_L2N_3_P32") (pintype "bidirectional"))
    )
    (net (code "385") (name "SOURCE_HIGHBAND") (class "Default")
      (node (ref "C68") (pin "2") (pinfunction "2_2") (pintype "passive"))
      (node (ref "IC13") (pin "3") (pinfunction "RF1_3") (pintype "bidirectional"))
    )
    (net (code "386") (name "SOURCE_LD") (class "Default")
      (node (ref "C273") (pin "1") (pinfunction "1_1") (pintype "passive"))
      (node (ref "R166") (pin "2") (pinfunction "2_2") (pintype "passive"))
      (node (ref "U2") (pin "P35") (pinfunction "IO_L1P_3_P35") (pintype "bidirectional"))
    )
    (net (code "387") (name "SOURCE_LE") (class "Default")
      (node (ref "R171") (pin "2") (pinfunction "2_2") (pintype "passive"))
      (node (ref "U2") (pin "P29") (pinfunction "IO_L36N_3_P29") (pintype "bidirectional"))
    )
    (net (code "388") (name "SOURCE_LOWBAND") (class "Default")
      (node (ref "C48") (pin "1") (pinfunction "1_1") (pintype "passive"))
      (node (ref "IC13") (pin "13") (pinfunction "RF2_13") (pintype "bidirectional"))
    )
    (net (code "389") (name "SOURCE_MOSI") (class "Default")
      (node (ref "R170") (pin "2") (pinfunction "2_2") (pintype "passive"))
      (node (ref "U2") (pin "P30") (pinfunction "IO_L36P_3_P30") (pintype "bidirectional"))
    )
    (net (code "390") (name "SOURCE_MUX") (class "Default")
      (node (ref "R167") (pin "2") (pinfunction "2_2") (pintype "passive"))
      (node (ref "U2") (pin "P33") (pinfunction "IO_L2P_3_P33") (pintype "bidirectional"))
    )
    (net (code "391") (name "SOURCE_REF") (class "Default")
      (node (ref "C51") (pin "1") (pinfunction "1_1") (pintype "passive"))
      (node (ref "IC7") (pin "8") (pinfunction "CLK3_8") (pintype "bidirectional"))
    )
    (net (code "392") (name "SOURCE_RF_EN") (class "Default")
      (node (ref "C271") (pin "1") (pinfunction "1_1") (pintype "passive"))
      (node (ref "R165") (pin "2") (pinfunction "2_2") (pintype "passive"))
      (node (ref "U2") (pin "P34") (pinfunction "IO_L1N_VREF_3_P34") (pintype "bidirectional"))
    )
    (net (code "393") (name "SOURCE_VCC") (class "Default")
      (node (ref "C57") (pin "1") (pinfunction "1_1") (pintype "passive"))
      (node (ref "IC10") (pin "10") (pinfunction "VCC_PLL_10") (pintype "bidirectional"))
      (node (ref "IC10") (pin "6") (pinfunction "VCC_CP_6") (pintype "bidirectional"))
      (node (ref "IC11") (pin "3") (pinfunction "VDD_3") (pintype "bidirectional"))
      (node (ref "IC12") (pin "3") (pinfunction "VDD_3") (pintype "bidirectional"))
      (node (ref "L20") (pin "2") (pinfunction "2_2") (pintype "passive"))
      (node (ref "TP13") (pin "TP") (pinfunction "TP_TP") (pintype "input"))
    )
    (net (code "394") (name "SWCLK") (class "Default")
      (node (ref "IC37") (pin "37") (pinfunction "PA14_37") (pintype "bidirectional"))
      (node (ref "JP1") (pin "6") (pinfunction "6_6") (pintype "passive"))
    )
    (net (code "395") (name "SWDIO") (class "Default")
      (node (ref "IC37") (pin "36") (pinfunction "PA13_36") (pintype "bidirectional"))
      (node (ref "JP1") (pin "8") (pinfunction "8_8") (pintype "passive"))
    )
    (net (code "396") (name "TCK") (class "Default")
      (node (ref "JP1") (pin "1") (pinfunction "1_1") (pintype "passive"))
      (node (ref "U2") (pin "P109") (pinfunction "TCK_P109") (pintype "input"))
    )
    (net (code "397") (name "TDI") (class "Default")
      (node (ref "JP1") (pin "3") (pinfunction "3_3") (pintype "passive"))
      (node (ref "U2") (pin "P110") (pinfunction "TDI_P110") (pintype "input"))
    )
    (net (code "398") (name "TDO") (class "Default")
      (node (ref "JP1") (pin "2") (pinfunction "2_2") (pintype "passive"))
      (node (ref "U2") (pin "P106") (pinfunction "TDO_P106") (pintype "output"))
    )
    (net (code "399") (name "TMS") (class "Default")
      (node (ref "JP1") (pin "4") (pinfunction "4_4") (pintype "passive"))
      (node (ref "U2") (pin "P107") (pinfunction "TMS_P107") (pintype "input"))
    )
    (net (code "400") (name "UART_TX") (class "Default")
      (node (ref "IC37") (pin "39") (pinfunction "PC10_39") (pintype "bidirectional"))
      (node (ref "JP1") (pin "10") (pinfunction "10_10") (pintype "passive"))
    )
    (net (code "401") (name "USB_POWER") (class "Default")
      (node (ref "J4") (pin "11") (pinfunction "VBUS_11") (pintype "bidirectional"))
      (node (ref "J4") (pin "2") (pinfunction "VBUS_2") (pintype "bidirectional"))
      (node (ref "Q1") (pin "3") (pinfunction "D_3") (pintype "passive"))
    )
    (net (code "402") (name "VCCINT") (class "Default")
      (node (ref "C10") (pin "1") (pinfunction "1_1") (pintype "passive"))
      (node (ref "C211") (pin "1") (pinfunction "1_1") (pintype "passive"))
      (node (ref "C213") (pin "1") (pinfunction "1_1") (pintype "passive"))
      (node (ref "C215") (pin "1") (pinfunction "1_1") (pintype "passive"))
      (node (ref "C217") (pin "1") (pinfunction "1_1") (pintype "passive"))
      (node (ref "C219") (pin "1") (pinfunction "1_1") (pintype "passive"))
      (node (ref "C7") (pin "1") (pinfunction "1_1") (pintype "passive"))
      (node (ref "IC2") (pin "9") (pinfunction "FB_9") (pintype "bidirectional"))
      (node (ref "L2") (pin "P$2") (pinfunction "2_P$2") (pintype "passive"))
      (node (ref "TP1") (pin "TP") (pinfunction "TP_TP") (pintype "input"))
      (node (ref "U2") (pin "P128") (pinfunction "VCCINT_P128") (pintype "input"))
      (node (ref "U2") (pin "P19") (pinfunction "VCCINT_P19") (pintype "input"))
      (node (ref "U2") (pin "P28") (pinfunction "VCCINT_P28") (pintype "input"))
      (node (ref "U2") (pin "P52") (pinfunction "VCCINT_P52") (pintype "input"))
      (node (ref "U2") (pin "P89") (pinfunction "VCCINT_P89") (pintype "input"))
    )
    (net (code "403") (name "unconnected-(IC2A-{slash}POR-Pad12)") (class "Default")
      (node (ref "IC2") (pin "12") (pinfunction "/POR_12") (pintype "bidirectional"))
    )
    (net (code "404") (name "unconnected-(IC2B-{slash}POR-Pad13)") (class "Default")
      (node (ref "IC2") (pin "13") (pinfunction "/POR_13") (pintype "bidirectional"))
    )
    (net (code "405") (name "unconnected-(IC7-INTR-Pad3)") (class "Default")
      (node (ref "IC7") (pin "3") (pinfunction "INTR_3") (pintype "bidirectional"))
    )
    (net (code "406") (name "unconnected-(IC7-XB-Pad2)") (class "Default")
      (node (ref "IC7") (pin "2") (pinfunction "XB_2") (pintype "bidirectional"))
    )
    (net (code "407") (name "unconnected-(IC10-RFOUTB_N-Pad15)") (class "Default")
      (node (ref "IC10") (pin "15") (pinfunction "RFOUTB_N_15") (pintype "bidirectional"))
    )
    (net (code "408") (name "unconnected-(IC10-RFOUTB_P-Pad14)") (class "Default")
      (node (ref "IC10") (pin "14") (pinfunction "RFOUTB_P_14") (pintype "bidirectional"))
    )
    (net (code "409") (name "unconnected-(IC14-CLK-Pad17)") (class "Default")
      (node (ref "IC14") (pin "17") (pinfunction "CLK_17") (pintype "bidirectional"))
    )
    (net (code "410") (name "unconnected-(IC14-DATA-Pad18)") (class "Default")
      (node (ref "IC14") (pin "18") (pinfunction "DATA_18") (pintype "bidirectional"))
    )
    (net (code "411") (name "unconnected-(IC17-RF2-Pad13)") (class "Default")
      (node (ref "IC17") (pin "13") (pinfunction "RF2_13") (pintype "bidirectional"))
    )
    (net (code "412") (name "unconnected-(IC18-RF2-Pad13)") (class "Default")
      (node (ref "IC18") (pin "13") (pinfunction "RF2_13") (pintype "bidirectional"))
    )
    (net (code "413") (name "unconnected-(IC37-PA0-Pad8)") (class "Default")
      (node (ref "IC37") (pin "8") (pinfunction "PA0_8") (pintype "bidirectional"))
    )
    (net (code "414") (name "unconnected-(IC37-PB10-Pad22)") (class "Default")
      (node (ref "IC37") (pin "22") (pinfunction "PB10_22") (pintype "bidirectional"))
    )
    (net (code "415") (name "unconnected-(IC37-PB11-Pad24)") (class "Default")
      (node (ref "IC37") (pin "24") (pinfunction "PB11_24") (pintype "bidirectional"))
    )
    (net (code "416") (name "unconnected-(IC37-PB14-Pad27)") (class "Default")
      (node (ref "IC37") (pin "27") (pinfunction "PB14_27") (pintype "bidirectional"))
    )
    (net (code "417") (name "unconnected-(IC37-PC6-Pad29)") (class "Default")
      (node (ref "IC37") (pin "29") (pinfunction "PC6_29") (pintype "bidirectional"))
    )
    (net (code "418") (name "unconnected-(IC37-PC13-Pad2)") (class "Default")
      (node (ref "IC37") (pin "2") (pinfunction "PC13_2") (pintype "bidirectional"))
    )
    (net (code "419") (name "unconnected-(IC37-PC14-OSC32_IN-Pad3)") (class "Default")
      (node (ref "IC37") (pin "3") (pinfunction "PC14-OSC32_IN_3") (pintype "bidirectional"))
    )
    (net (code "420") (name "unconnected-(IC37-PC15-OSC32_OUT-Pad4)") (class "Default")
      (node (ref "IC37") (pin "4") (pinfunction "PC15-OSC32_OUT_4") (pintype "bidirectional"))
    )
    (net (code "421") (name "unconnected-(IC37-PF0-OSC_IN-Pad5)") (class "Default")
      (node (ref "IC37") (pin "5") (pinfunction "PF0-OSC_IN_5") (pintype "bidirectional"))
    )
    (net (code "422") (name "unconnected-(J4-SBU1-Pad9)") (class "Default")
      (node (ref "J4") (pin "9") (pinfunction "SBU1_9") (pintype "bidirectional"))
    )
    (net (code "423") (name "unconnected-(J4-SBU2-Pad3)") (class "Default")
      (node (ref "J4") (pin "3") (pinfunction "SBU2_3") (pintype "bidirectional"))
    )
    (net (code "424") (name "unconnected-(U2B-IO_L1N_VREF_1-PadP104)") (class "Default")
      (node (ref "U2") (pin "P104") (pinfunction "IO_L1N_VREF_1_P104") (pintype "bidirectional"))
    )
    (net (code "425") (name "unconnected-(U2B-IO_L1P_1-PadP105)") (class "Default")
      (node (ref "U2") (pin "P105") (pinfunction "IO_L1P_1_P105") (pintype "bidirectional"))
    )
    (net (code "426") (name "unconnected-(U2B-IO_L32N_1-PadP101)") (class "Default")
      (node (ref "U2") (pin "P101") (pinfunction "IO_L32N_1_P101") (pintype "bidirectional"))
    )
    (net (code "427") (name "unconnected-(U2B-IO_L32P_1-PadP102)") (class "Default")
      (node (ref "U2") (pin "P102") (pinfunction "IO_L32P_1_P102") (pintype "bidirectional"))
    )
    (net (code "428") (name "unconnected-(U2B-IO_L33N_1-PadP99)") (class "Default")
      (node (ref "U2") (pin "P99") (pinfunction "IO_L33N_1_P99") (pintype "bidirectional"))
    )
    (net (code "429") (name "unconnected-(U2B-IO_L33P_1-PadP100)") (class "Default")
      (node (ref "U2") (pin "P100") (pinfunction "IO_L33P_1_P100") (pintype "bidirectional"))
    )
    (net (code "430") (name "unconnected-(U2B-IO_L34N_1-PadP97)") (class "Default")
      (node (ref "U2") (pin "P97") (pinfunction "IO_L34N_1_P97") (pintype "bidirectional"))
    )
    (net (code "431") (name "unconnected-(U2B-IO_L34P_1-PadP98)") (class "Default")
      (node (ref "U2") (pin "P98") (pinfunction "IO_L34P_1_P98") (pintype "bidirectional"))
    )
    (net (code "432") (name "unconnected-(U2B-IO_L40N_GCLK10_1-PadP94)") (class "Default")
      (node (ref "U2") (pin "P94") (pinfunction "IO_L40N_GCLK10_1_P94") (pintype "bidirectional"))
    )
    (net (code "433") (name "unconnected-(U2B-IO_L40P_GCLK11_1-PadP95)") (class "Default")
      (node (ref "U2") (pin "P95") (pinfunction "IO_L40P_GCLK11_1_P95") (pintype "bidirectional"))
    )
  )
)
